# UCirKitBreadboardTop.net
KiCad netlist of a schematic drawn in EAGLE
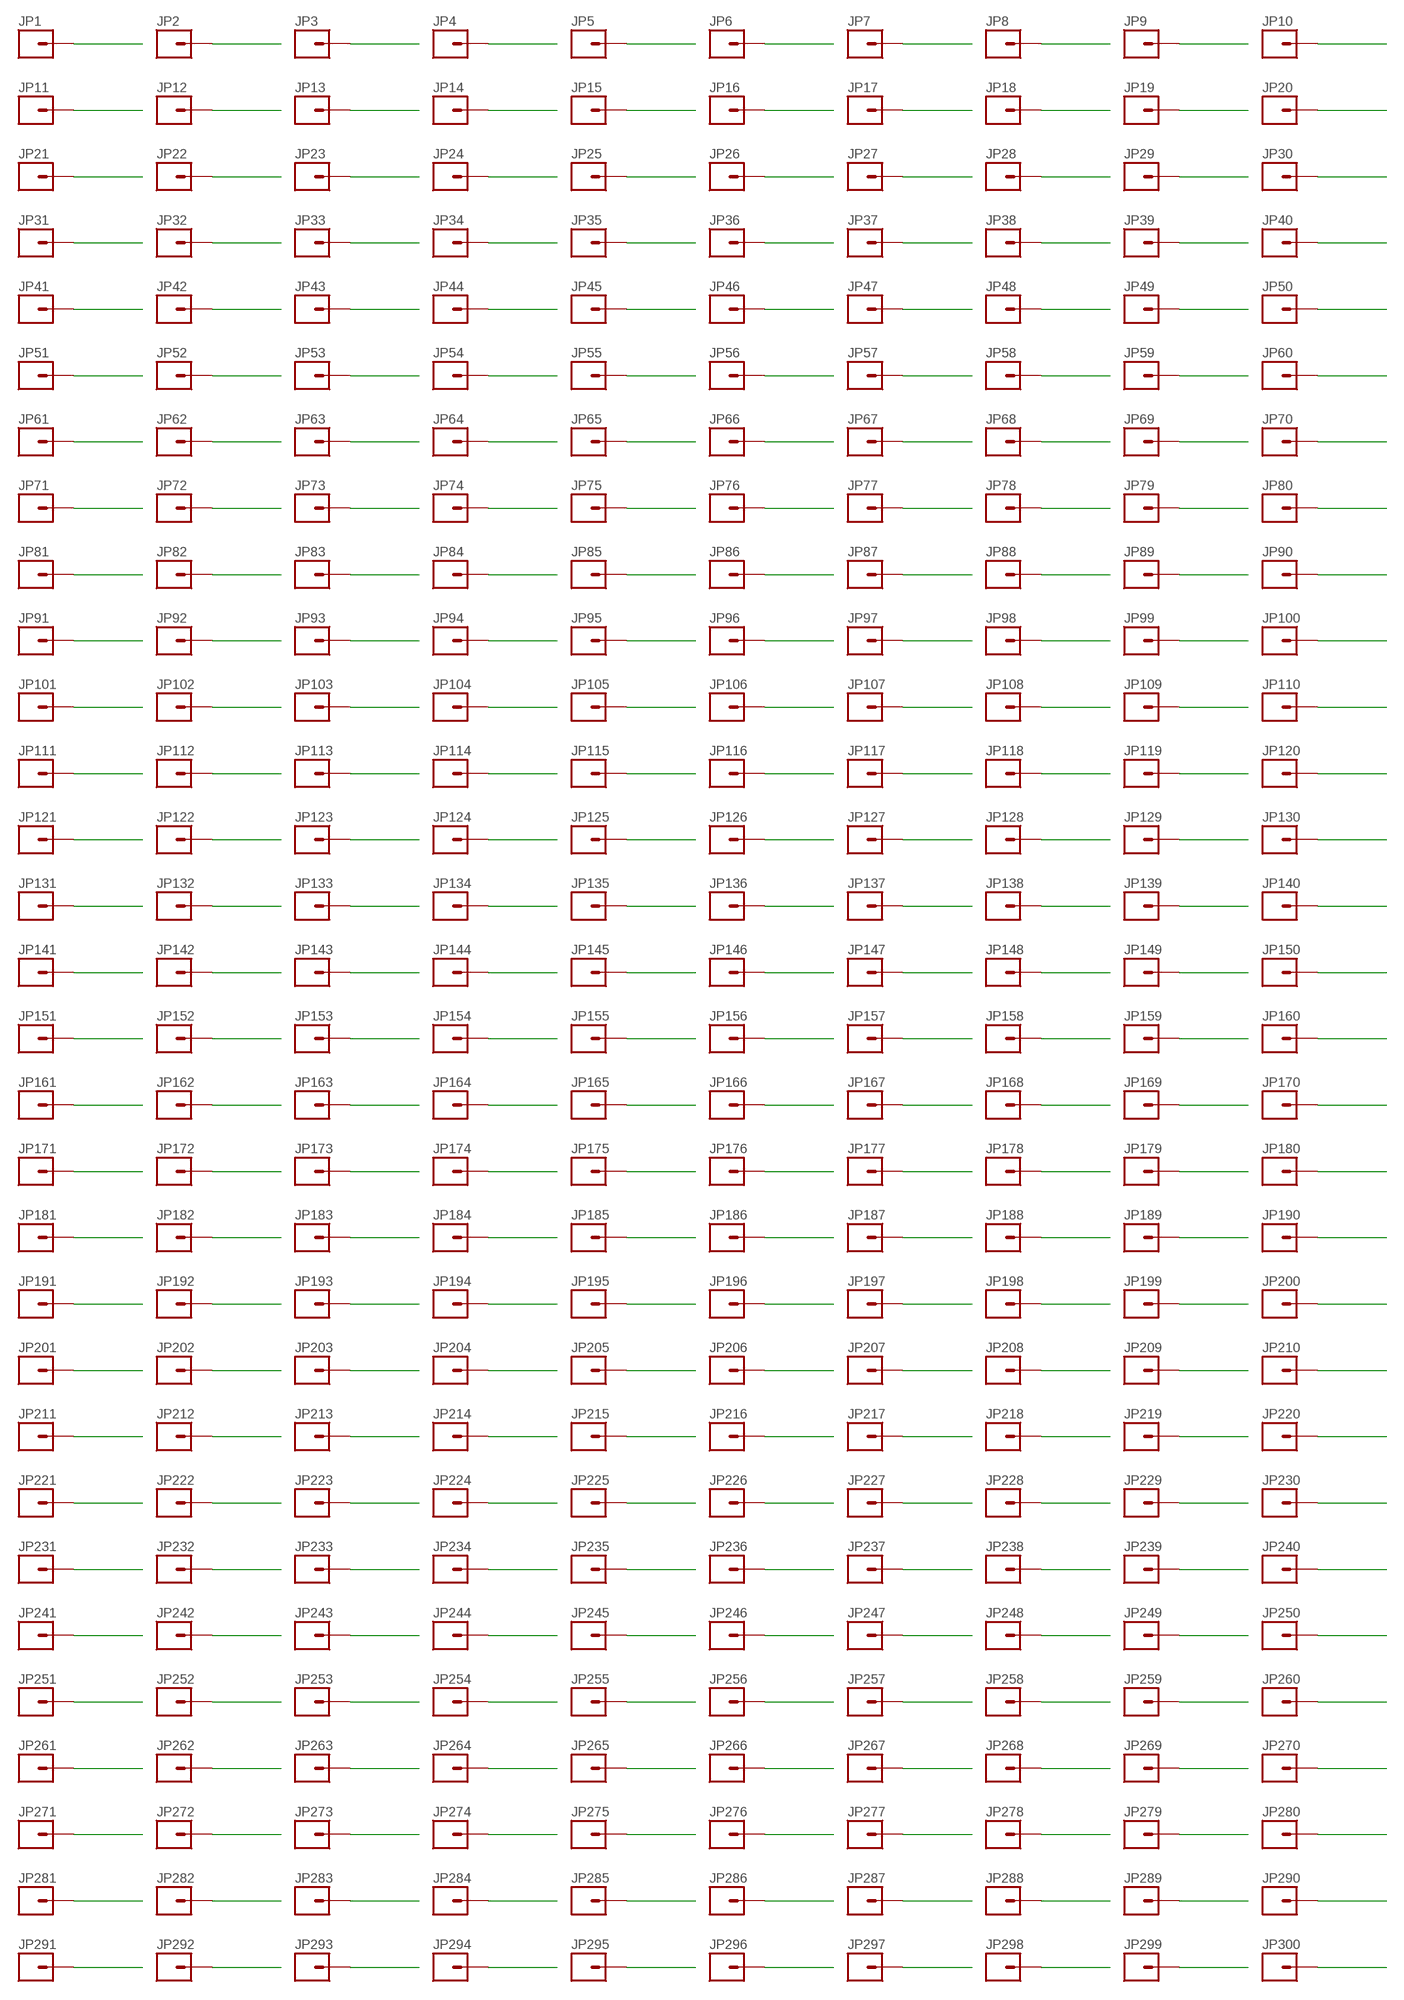
[diagram p0: schematic, sheet 1, part 1 of 2]
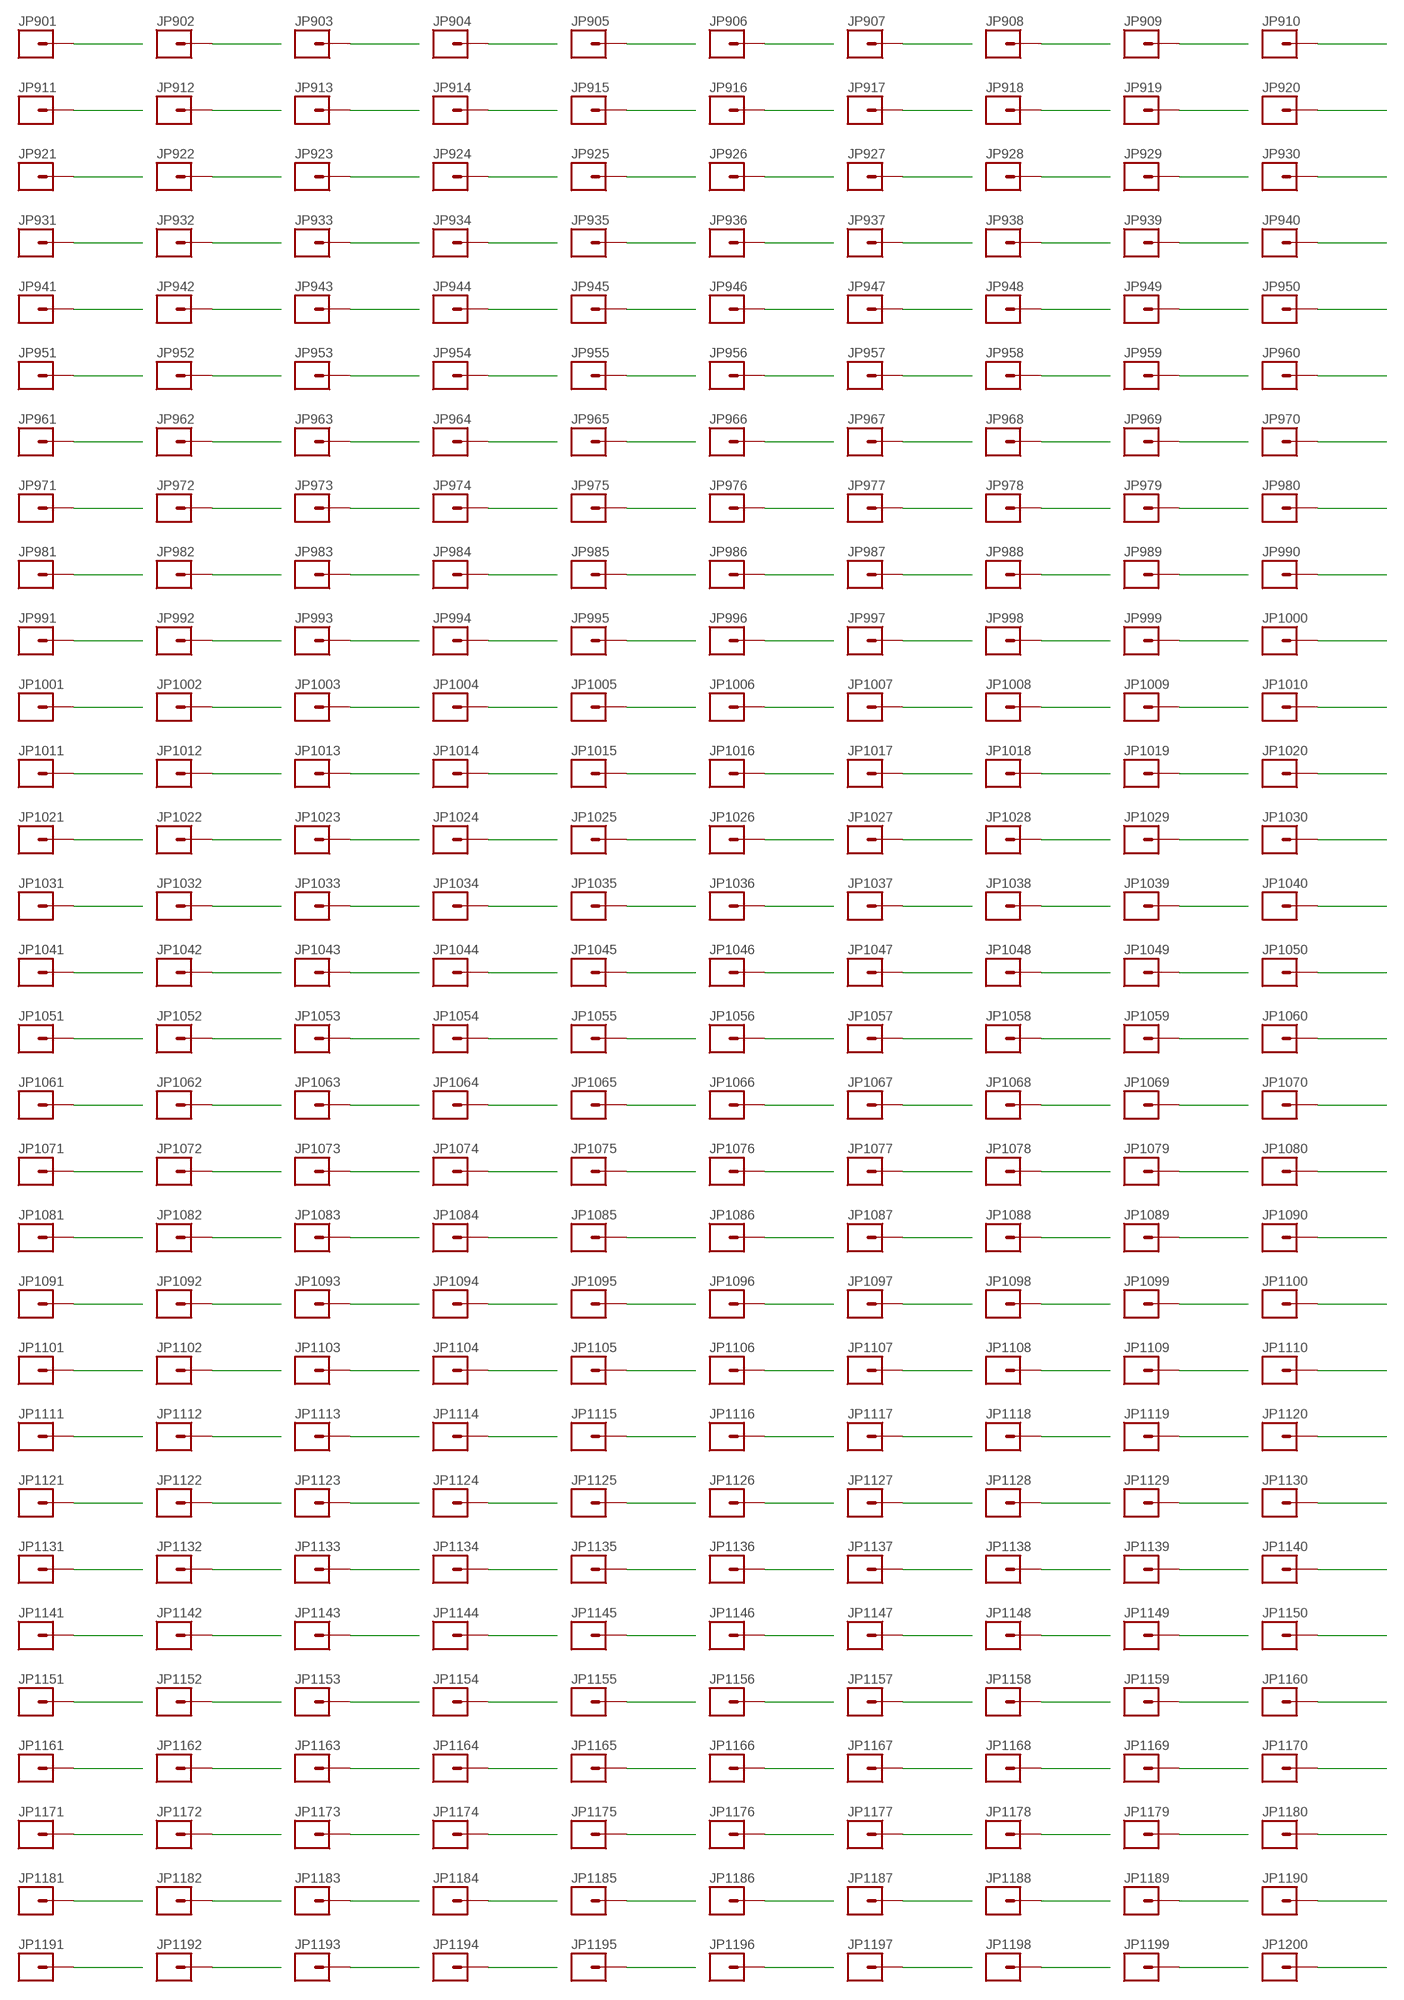
[diagram p1: schematic, sheet 1, part 2 of 2]

(export (version "E")
  (design (tool "Eeschema 10.0.6"))
  (components
    (comp (ref "JP1")
      (value "M01PTH_WITHOUT_TEXT")
      (footprint "eagle-import:1X01_WITHOUT_TEXT")
      (libsource (lib "eagle-import") (part "M01PTH_WITHOUT_TEXT"))
    )
    (comp (ref "JP2")
      (value "M01PTH_WITHOUT_TEXT")
      (footprint "eagle-import:1X01_WITHOUT_TEXT")
      (libsource (lib "eagle-import") (part "M01PTH_WITHOUT_TEXT"))
    )
    (comp (ref "JP3")
      (value "M01PTH_WITHOUT_TEXT")
      (footprint "eagle-import:1X01_WITHOUT_TEXT")
      (libsource (lib "eagle-import") (part "M01PTH_WITHOUT_TEXT"))
    )
    (comp (ref "JP4")
      (value "M01PTH_WITHOUT_TEXT")
      (footprint "eagle-import:1X01_WITHOUT_TEXT")
      (libsource (lib "eagle-import") (part "M01PTH_WITHOUT_TEXT"))
    )
    (comp (ref "JP5")
      (value "M01PTH_WITHOUT_TEXT")
      (footprint "eagle-import:1X01_WITHOUT_TEXT")
      (libsource (lib "eagle-import") (part "M01PTH_WITHOUT_TEXT"))
    )
    (comp (ref "JP6")
      (value "M01PTH_WITHOUT_TEXT")
      (footprint "eagle-import:1X01_WITHOUT_TEXT")
      (libsource (lib "eagle-import") (part "M01PTH_WITHOUT_TEXT"))
    )
    (comp (ref "JP7")
      (value "M01PTH_WITHOUT_TEXT")
      (footprint "eagle-import:1X01_WITHOUT_TEXT")
      (libsource (lib "eagle-import") (part "M01PTH_WITHOUT_TEXT"))
    )
    (comp (ref "JP8")
      (value "M01PTH_WITHOUT_TEXT")
      (footprint "eagle-import:1X01_WITHOUT_TEXT")
      (libsource (lib "eagle-import") (part "M01PTH_WITHOUT_TEXT"))
    )
    (comp (ref "JP9")
      (value "M01PTH_WITHOUT_TEXT")
      (footprint "eagle-import:1X01_WITHOUT_TEXT")
      (libsource (lib "eagle-import") (part "M01PTH_WITHOUT_TEXT"))
    )
    (comp (ref "JP10")
      (value "M01PTH_WITHOUT_TEXT")
      (footprint "eagle-import:1X01_WITHOUT_TEXT")
      (libsource (lib "eagle-import") (part "M01PTH_WITHOUT_TEXT"))
    )
    (comp (ref "JP11")
      (value "M01PTH_WITHOUT_TEXT")
      (footprint "eagle-import:1X01_WITHOUT_TEXT")
      (libsource (lib "eagle-import") (part "M01PTH_WITHOUT_TEXT"))
    )
    (comp (ref "JP12")
      (value "M01PTH_WITHOUT_TEXT")
      (footprint "eagle-import:1X01_WITHOUT_TEXT")
      (libsource (lib "eagle-import") (part "M01PTH_WITHOUT_TEXT"))
    )
    (comp (ref "JP13")
      (value "M01PTH_WITHOUT_TEXT")
      (footprint "eagle-import:1X01_WITHOUT_TEXT")
      (libsource (lib "eagle-import") (part "M01PTH_WITHOUT_TEXT"))
    )
    (comp (ref "JP14")
      (value "M01PTH_WITHOUT_TEXT")
      (footprint "eagle-import:1X01_WITHOUT_TEXT")
      (libsource (lib "eagle-import") (part "M01PTH_WITHOUT_TEXT"))
    )
    (comp (ref "JP15")
      (value "M01PTH_WITHOUT_TEXT")
      (footprint "eagle-import:1X01_WITHOUT_TEXT")
      (libsource (lib "eagle-import") (part "M01PTH_WITHOUT_TEXT"))
    )
    (comp (ref "JP16")
      (value "M01PTH_WITHOUT_TEXT")
      (footprint "eagle-import:1X01_WITHOUT_TEXT")
      (libsource (lib "eagle-import") (part "M01PTH_WITHOUT_TEXT"))
    )
    (comp (ref "JP17")
      (value "M01PTH_WITHOUT_TEXT")
      (footprint "eagle-import:1X01_WITHOUT_TEXT")
      (libsource (lib "eagle-import") (part "M01PTH_WITHOUT_TEXT"))
    )
    (comp (ref "JP18")
      (value "M01PTH_WITHOUT_TEXT")
      (footprint "eagle-import:1X01_WITHOUT_TEXT")
      (libsource (lib "eagle-import") (part "M01PTH_WITHOUT_TEXT"))
    )
    (comp (ref "JP19")
      (value "M01PTH_WITHOUT_TEXT")
      (footprint "eagle-import:1X01_WITHOUT_TEXT")
      (libsource (lib "eagle-import") (part "M01PTH_WITHOUT_TEXT"))
    )
    (comp (ref "JP20")
      (value "M01PTH_WITHOUT_TEXT")
      (footprint "eagle-import:1X01_WITHOUT_TEXT")
      (libsource (lib "eagle-import") (part "M01PTH_WITHOUT_TEXT"))
    )
    (comp (ref "JP21")
      (value "M01PTH_WITHOUT_TEXT")
      (footprint "eagle-import:1X01_WITHOUT_TEXT")
      (libsource (lib "eagle-import") (part "M01PTH_WITHOUT_TEXT"))
    )
    (comp (ref "JP22")
      (value "M01PTH_WITHOUT_TEXT")
      (footprint "eagle-import:1X01_WITHOUT_TEXT")
      (libsource (lib "eagle-import") (part "M01PTH_WITHOUT_TEXT"))
    )
    (comp (ref "JP23")
      (value "M01PTH_WITHOUT_TEXT")
      (footprint "eagle-import:1X01_WITHOUT_TEXT")
      (libsource (lib "eagle-import") (part "M01PTH_WITHOUT_TEXT"))
    )
    (comp (ref "JP24")
      (value "M01PTH_WITHOUT_TEXT")
      (footprint "eagle-import:1X01_WITHOUT_TEXT")
      (libsource (lib "eagle-import") (part "M01PTH_WITHOUT_TEXT"))
    )
    (comp (ref "JP25")
      (value "M01PTH_WITHOUT_TEXT")
      (footprint "eagle-import:1X01_WITHOUT_TEXT")
      (libsource (lib "eagle-import") (part "M01PTH_WITHOUT_TEXT"))
    )
    (comp (ref "JP26")
      (value "M01PTH_WITHOUT_TEXT")
      (footprint "eagle-import:1X01_WITHOUT_TEXT")
      (libsource (lib "eagle-import") (part "M01PTH_WITHOUT_TEXT"))
    )
    (comp (ref "JP27")
      (value "M01PTH_WITHOUT_TEXT")
      (footprint "eagle-import:1X01_WITHOUT_TEXT")
      (libsource (lib "eagle-import") (part "M01PTH_WITHOUT_TEXT"))
    )
    (comp (ref "JP28")
      (value "M01PTH_WITHOUT_TEXT")
      (footprint "eagle-import:1X01_WITHOUT_TEXT")
      (libsource (lib "eagle-import") (part "M01PTH_WITHOUT_TEXT"))
    )
    (comp (ref "JP29")
      (value "M01PTH_WITHOUT_TEXT")
      (footprint "eagle-import:1X01_WITHOUT_TEXT")
      (libsource (lib "eagle-import") (part "M01PTH_WITHOUT_TEXT"))
    )
    (comp (ref "JP30")
      (value "M01PTH_WITHOUT_TEXT")
      (footprint "eagle-import:1X01_WITHOUT_TEXT")
      (libsource (lib "eagle-import") (part "M01PTH_WITHOUT_TEXT"))
    )
    (comp (ref "JP31")
      (value "M01PTH_WITHOUT_TEXT")
      (footprint "eagle-import:1X01_WITHOUT_TEXT")
      (libsource (lib "eagle-import") (part "M01PTH_WITHOUT_TEXT"))
    )
    (comp (ref "JP32")
      (value "M01PTH_WITHOUT_TEXT")
      (footprint "eagle-import:1X01_WITHOUT_TEXT")
      (libsource (lib "eagle-import") (part "M01PTH_WITHOUT_TEXT"))
    )
    (comp (ref "JP33")
      (value "M01PTH_WITHOUT_TEXT")
      (footprint "eagle-import:1X01_WITHOUT_TEXT")
      (libsource (lib "eagle-import") (part "M01PTH_WITHOUT_TEXT"))
    )
    (comp (ref "JP34")
      (value "M01PTH_WITHOUT_TEXT")
      (footprint "eagle-import:1X01_WITHOUT_TEXT")
      (libsource (lib "eagle-import") (part "M01PTH_WITHOUT_TEXT"))
    )
    (comp (ref "JP35")
      (value "M01PTH_WITHOUT_TEXT")
      (footprint "eagle-import:1X01_WITHOUT_TEXT")
      (libsource (lib "eagle-import") (part "M01PTH_WITHOUT_TEXT"))
    )
    (comp (ref "JP36")
      (value "M01PTH_WITHOUT_TEXT")
      (footprint "eagle-import:1X01_WITHOUT_TEXT")
      (libsource (lib "eagle-import") (part "M01PTH_WITHOUT_TEXT"))
    )
    (comp (ref "JP37")
      (value "M01PTH_WITHOUT_TEXT")
      (footprint "eagle-import:1X01_WITHOUT_TEXT")
      (libsource (lib "eagle-import") (part "M01PTH_WITHOUT_TEXT"))
    )
    (comp (ref "JP38")
      (value "M01PTH_WITHOUT_TEXT")
      (footprint "eagle-import:1X01_WITHOUT_TEXT")
      (libsource (lib "eagle-import") (part "M01PTH_WITHOUT_TEXT"))
    )
    (comp (ref "JP39")
      (value "M01PTH_WITHOUT_TEXT")
      (footprint "eagle-import:1X01_WITHOUT_TEXT")
      (libsource (lib "eagle-import") (part "M01PTH_WITHOUT_TEXT"))
    )
    (comp (ref "JP40")
      (value "M01PTH_WITHOUT_TEXT")
      (footprint "eagle-import:1X01_WITHOUT_TEXT")
      (libsource (lib "eagle-import") (part "M01PTH_WITHOUT_TEXT"))
    )
    (comp (ref "JP41")
      (value "M01PTH_WITHOUT_TEXT")
      (footprint "eagle-import:1X01_WITHOUT_TEXT")
      (libsource (lib "eagle-import") (part "M01PTH_WITHOUT_TEXT"))
    )
    (comp (ref "JP42")
      (value "M01PTH_WITHOUT_TEXT")
      (footprint "eagle-import:1X01_WITHOUT_TEXT")
      (libsource (lib "eagle-import") (part "M01PTH_WITHOUT_TEXT"))
    )
    (comp (ref "JP43")
      (value "M01PTH_WITHOUT_TEXT")
      (footprint "eagle-import:1X01_WITHOUT_TEXT")
      (libsource (lib "eagle-import") (part "M01PTH_WITHOUT_TEXT"))
    )
    (comp (ref "JP44")
      (value "M01PTH_WITHOUT_TEXT")
      (footprint "eagle-import:1X01_WITHOUT_TEXT")
      (libsource (lib "eagle-import") (part "M01PTH_WITHOUT_TEXT"))
    )
    (comp (ref "JP45")
      (value "M01PTH_WITHOUT_TEXT")
      (footprint "eagle-import:1X01_WITHOUT_TEXT")
      (libsource (lib "eagle-import") (part "M01PTH_WITHOUT_TEXT"))
    )
    (comp (ref "JP46")
      (value "M01PTH_WITHOUT_TEXT")
      (footprint "eagle-import:1X01_WITHOUT_TEXT")
      (libsource (lib "eagle-import") (part "M01PTH_WITHOUT_TEXT"))
    )
    (comp (ref "JP47")
      (value "M01PTH_WITHOUT_TEXT")
      (footprint "eagle-import:1X01_WITHOUT_TEXT")
      (libsource (lib "eagle-import") (part "M01PTH_WITHOUT_TEXT"))
    )
    (comp (ref "JP48")
      (value "M01PTH_WITHOUT_TEXT")
      (footprint "eagle-import:1X01_WITHOUT_TEXT")
      (libsource (lib "eagle-import") (part "M01PTH_WITHOUT_TEXT"))
    )
    (comp (ref "JP49")
      (value "M01PTH_WITHOUT_TEXT")
      (footprint "eagle-import:1X01_WITHOUT_TEXT")
      (libsource (lib "eagle-import") (part "M01PTH_WITHOUT_TEXT"))
    )
    (comp (ref "JP50")
      (value "M01PTH_WITHOUT_TEXT")
      (footprint "eagle-import:1X01_WITHOUT_TEXT")
      (libsource (lib "eagle-import") (part "M01PTH_WITHOUT_TEXT"))
    )
    (comp (ref "JP51")
      (value "M01PTH_WITHOUT_TEXT")
      (footprint "eagle-import:1X01_WITHOUT_TEXT")
      (libsource (lib "eagle-import") (part "M01PTH_WITHOUT_TEXT"))
    )
    (comp (ref "JP52")
      (value "M01PTH_WITHOUT_TEXT")
      (footprint "eagle-import:1X01_WITHOUT_TEXT")
      (libsource (lib "eagle-import") (part "M01PTH_WITHOUT_TEXT"))
    )
    (comp (ref "JP53")
      (value "M01PTH_WITHOUT_TEXT")
      (footprint "eagle-import:1X01_WITHOUT_TEXT")
      (libsource (lib "eagle-import") (part "M01PTH_WITHOUT_TEXT"))
    )
    (comp (ref "JP54")
      (value "M01PTH_WITHOUT_TEXT")
      (footprint "eagle-import:1X01_WITHOUT_TEXT")
      (libsource (lib "eagle-import") (part "M01PTH_WITHOUT_TEXT"))
    )
    (comp (ref "JP55")
      (value "M01PTH_WITHOUT_TEXT")
      (footprint "eagle-import:1X01_WITHOUT_TEXT")
      (libsource (lib "eagle-import") (part "M01PTH_WITHOUT_TEXT"))
    )
    (comp (ref "JP56")
      (value "M01PTH_WITHOUT_TEXT")
      (footprint "eagle-import:1X01_WITHOUT_TEXT")
      (libsource (lib "eagle-import") (part "M01PTH_WITHOUT_TEXT"))
    )
    (comp (ref "JP57")
      (value "M01PTH_WITHOUT_TEXT")
      (footprint "eagle-import:1X01_WITHOUT_TEXT")
      (libsource (lib "eagle-import") (part "M01PTH_WITHOUT_TEXT"))
    )
    (comp (ref "JP58")
      (value "M01PTH_WITHOUT_TEXT")
      (footprint "eagle-import:1X01_WITHOUT_TEXT")
      (libsource (lib "eagle-import") (part "M01PTH_WITHOUT_TEXT"))
    )
    (comp (ref "JP59")
      (value "M01PTH_WITHOUT_TEXT")
      (footprint "eagle-import:1X01_WITHOUT_TEXT")
      (libsource (lib "eagle-import") (part "M01PTH_WITHOUT_TEXT"))
    )
    (comp (ref "JP60")
      (value "M01PTH_WITHOUT_TEXT")
      (footprint "eagle-import:1X01_WITHOUT_TEXT")
      (libsource (lib "eagle-import") (part "M01PTH_WITHOUT_TEXT"))
    )
    (comp (ref "JP61")
      (value "M01PTH_WITHOUT_TEXT")
      (footprint "eagle-import:1X01_WITHOUT_TEXT")
      (libsource (lib "eagle-import") (part "M01PTH_WITHOUT_TEXT"))
    )
    (comp (ref "JP62")
      (value "M01PTH_WITHOUT_TEXT")
      (footprint "eagle-import:1X01_WITHOUT_TEXT")
      (libsource (lib "eagle-import") (part "M01PTH_WITHOUT_TEXT"))
    )
    (comp (ref "JP63")
      (value "M01PTH_WITHOUT_TEXT")
      (footprint "eagle-import:1X01_WITHOUT_TEXT")
      (libsource (lib "eagle-import") (part "M01PTH_WITHOUT_TEXT"))
    )
    (comp (ref "JP64")
      (value "M01PTH_WITHOUT_TEXT")
      (footprint "eagle-import:1X01_WITHOUT_TEXT")
      (libsource (lib "eagle-import") (part "M01PTH_WITHOUT_TEXT"))
    )
    (comp (ref "JP65")
      (value "M01PTH_WITHOUT_TEXT")
      (footprint "eagle-import:1X01_WITHOUT_TEXT")
      (libsource (lib "eagle-import") (part "M01PTH_WITHOUT_TEXT"))
    )
    (comp (ref "JP66")
      (value "M01PTH_WITHOUT_TEXT")
      (footprint "eagle-import:1X01_WITHOUT_TEXT")
      (libsource (lib "eagle-import") (part "M01PTH_WITHOUT_TEXT"))
    )
    (comp (ref "JP67")
      (value "M01PTH_WITHOUT_TEXT")
      (footprint "eagle-import:1X01_WITHOUT_TEXT")
      (libsource (lib "eagle-import") (part "M01PTH_WITHOUT_TEXT"))
    )
    (comp (ref "JP68")
      (value "M01PTH_WITHOUT_TEXT")
      (footprint "eagle-import:1X01_WITHOUT_TEXT")
      (libsource (lib "eagle-import") (part "M01PTH_WITHOUT_TEXT"))
    )
    (comp (ref "JP69")
      (value "M01PTH_WITHOUT_TEXT")
      (footprint "eagle-import:1X01_WITHOUT_TEXT")
      (libsource (lib "eagle-import") (part "M01PTH_WITHOUT_TEXT"))
    )
    (comp (ref "JP70")
      (value "M01PTH_WITHOUT_TEXT")
      (footprint "eagle-import:1X01_WITHOUT_TEXT")
      (libsource (lib "eagle-import") (part "M01PTH_WITHOUT_TEXT"))
    )
    (comp (ref "JP71")
      (value "M01PTH_WITHOUT_TEXT")
      (footprint "eagle-import:1X01_WITHOUT_TEXT")
      (libsource (lib "eagle-import") (part "M01PTH_WITHOUT_TEXT"))
    )
    (comp (ref "JP72")
      (value "M01PTH_WITHOUT_TEXT")
      (footprint "eagle-import:1X01_WITHOUT_TEXT")
      (libsource (lib "eagle-import") (part "M01PTH_WITHOUT_TEXT"))
    )
    (comp (ref "JP73")
      (value "M01PTH_WITHOUT_TEXT")
      (footprint "eagle-import:1X01_WITHOUT_TEXT")
      (libsource (lib "eagle-import") (part "M01PTH_WITHOUT_TEXT"))
    )
    (comp (ref "JP74")
      (value "M01PTH_WITHOUT_TEXT")
      (footprint "eagle-import:1X01_WITHOUT_TEXT")
      (libsource (lib "eagle-import") (part "M01PTH_WITHOUT_TEXT"))
    )
    (comp (ref "JP75")
      (value "M01PTH_WITHOUT_TEXT")
      (footprint "eagle-import:1X01_WITHOUT_TEXT")
      (libsource (lib "eagle-import") (part "M01PTH_WITHOUT_TEXT"))
    )
    (comp (ref "JP76")
      (value "M01PTH_WITHOUT_TEXT")
      (footprint "eagle-import:1X01_WITHOUT_TEXT")
      (libsource (lib "eagle-import") (part "M01PTH_WITHOUT_TEXT"))
    )
    (comp (ref "JP77")
      (value "M01PTH_WITHOUT_TEXT")
      (footprint "eagle-import:1X01_WITHOUT_TEXT")
      (libsource (lib "eagle-import") (part "M01PTH_WITHOUT_TEXT"))
    )
    (comp (ref "JP78")
      (value "M01PTH_WITHOUT_TEXT")
      (footprint "eagle-import:1X01_WITHOUT_TEXT")
      (libsource (lib "eagle-import") (part "M01PTH_WITHOUT_TEXT"))
    )
    (comp (ref "JP79")
      (value "M01PTH_WITHOUT_TEXT")
      (footprint "eagle-import:1X01_WITHOUT_TEXT")
      (libsource (lib "eagle-import") (part "M01PTH_WITHOUT_TEXT"))
    )
    (comp (ref "JP80")
      (value "M01PTH_WITHOUT_TEXT")
      (footprint "eagle-import:1X01_WITHOUT_TEXT")
      (libsource (lib "eagle-import") (part "M01PTH_WITHOUT_TEXT"))
    )
    (comp (ref "JP81")
      (value "M01PTH_WITHOUT_TEXT")
      (footprint "eagle-import:1X01_WITHOUT_TEXT")
      (libsource (lib "eagle-import") (part "M01PTH_WITHOUT_TEXT"))
    )
    (comp (ref "JP82")
      (value "M01PTH_WITHOUT_TEXT")
      (footprint "eagle-import:1X01_WITHOUT_TEXT")
      (libsource (lib "eagle-import") (part "M01PTH_WITHOUT_TEXT"))
    )
    (comp (ref "JP83")
      (value "M01PTH_WITHOUT_TEXT")
      (footprint "eagle-import:1X01_WITHOUT_TEXT")
      (libsource (lib "eagle-import") (part "M01PTH_WITHOUT_TEXT"))
    )
    (comp (ref "JP84")
      (value "M01PTH_WITHOUT_TEXT")
      (footprint "eagle-import:1X01_WITHOUT_TEXT")
      (libsource (lib "eagle-import") (part "M01PTH_WITHOUT_TEXT"))
    )
    (comp (ref "JP85")
      (value "M01PTH_WITHOUT_TEXT")
      (footprint "eagle-import:1X01_WITHOUT_TEXT")
      (libsource (lib "eagle-import") (part "M01PTH_WITHOUT_TEXT"))
    )
    (comp (ref "JP86")
      (value "M01PTH_WITHOUT_TEXT")
      (footprint "eagle-import:1X01_WITHOUT_TEXT")
      (libsource (lib "eagle-import") (part "M01PTH_WITHOUT_TEXT"))
    )
    (comp (ref "JP87")
      (value "M01PTH_WITHOUT_TEXT")
      (footprint "eagle-import:1X01_WITHOUT_TEXT")
      (libsource (lib "eagle-import") (part "M01PTH_WITHOUT_TEXT"))
    )
    (comp (ref "JP88")
      (value "M01PTH_WITHOUT_TEXT")
      (footprint "eagle-import:1X01_WITHOUT_TEXT")
      (libsource (lib "eagle-import") (part "M01PTH_WITHOUT_TEXT"))
    )
    (comp (ref "JP89")
      (value "M01PTH_WITHOUT_TEXT")
      (footprint "eagle-import:1X01_WITHOUT_TEXT")
      (libsource (lib "eagle-import") (part "M01PTH_WITHOUT_TEXT"))
    )
    (comp (ref "JP90")
      (value "M01PTH_WITHOUT_TEXT")
      (footprint "eagle-import:1X01_WITHOUT_TEXT")
      (libsource (lib "eagle-import") (part "M01PTH_WITHOUT_TEXT"))
    )
    (comp (ref "JP91")
      (value "M01PTH_WITHOUT_TEXT")
      (footprint "eagle-import:1X01_WITHOUT_TEXT")
      (libsource (lib "eagle-import") (part "M01PTH_WITHOUT_TEXT"))
    )
    (comp (ref "JP92")
      (value "M01PTH_WITHOUT_TEXT")
      (footprint "eagle-import:1X01_WITHOUT_TEXT")
      (libsource (lib "eagle-import") (part "M01PTH_WITHOUT_TEXT"))
    )
    (comp (ref "JP93")
      (value "M01PTH_WITHOUT_TEXT")
      (footprint "eagle-import:1X01_WITHOUT_TEXT")
      (libsource (lib "eagle-import") (part "M01PTH_WITHOUT_TEXT"))
    )
    (comp (ref "JP94")
      (value "M01PTH_WITHOUT_TEXT")
      (footprint "eagle-import:1X01_WITHOUT_TEXT")
      (libsource (lib "eagle-import") (part "M01PTH_WITHOUT_TEXT"))
    )
    (comp (ref "JP95")
      (value "M01PTH_WITHOUT_TEXT")
      (footprint "eagle-import:1X01_WITHOUT_TEXT")
      (libsource (lib "eagle-import") (part "M01PTH_WITHOUT_TEXT"))
    )
    (comp (ref "JP96")
      (value "M01PTH_WITHOUT_TEXT")
      (footprint "eagle-import:1X01_WITHOUT_TEXT")
      (libsource (lib "eagle-import") (part "M01PTH_WITHOUT_TEXT"))
    )
    (comp (ref "JP97")
      (value "M01PTH_WITHOUT_TEXT")
      (footprint "eagle-import:1X01_WITHOUT_TEXT")
      (libsource (lib "eagle-import") (part "M01PTH_WITHOUT_TEXT"))
    )
    (comp (ref "JP98")
      (value "M01PTH_WITHOUT_TEXT")
      (footprint "eagle-import:1X01_WITHOUT_TEXT")
      (libsource (lib "eagle-import") (part "M01PTH_WITHOUT_TEXT"))
    )
    (comp (ref "JP99")
      (value "M01PTH_WITHOUT_TEXT")
      (footprint "eagle-import:1X01_WITHOUT_TEXT")
      (libsource (lib "eagle-import") (part "M01PTH_WITHOUT_TEXT"))
    )
    (comp (ref "JP100")
      (value "M01PTH_WITHOUT_TEXT")
      (footprint "eagle-import:1X01_WITHOUT_TEXT")
      (libsource (lib "eagle-import") (part "M01PTH_WITHOUT_TEXT"))
    )
    (comp (ref "JP101")
      (value "M01PTH_WITHOUT_TEXT")
      (footprint "eagle-import:1X01_WITHOUT_TEXT")
      (libsource (lib "eagle-import") (part "M01PTH_WITHOUT_TEXT"))
    )
    (comp (ref "JP102")
      (value "M01PTH_WITHOUT_TEXT")
      (footprint "eagle-import:1X01_WITHOUT_TEXT")
      (libsource (lib "eagle-import") (part "M01PTH_WITHOUT_TEXT"))
    )
    (comp (ref "JP103")
      (value "M01PTH_WITHOUT_TEXT")
      (footprint "eagle-import:1X01_WITHOUT_TEXT")
      (libsource (lib "eagle-import") (part "M01PTH_WITHOUT_TEXT"))
    )
    (comp (ref "JP104")
      (value "M01PTH_WITHOUT_TEXT")
      (footprint "eagle-import:1X01_WITHOUT_TEXT")
      (libsource (lib "eagle-import") (part "M01PTH_WITHOUT_TEXT"))
    )
    (comp (ref "JP105")
      (value "M01PTH_WITHOUT_TEXT")
      (footprint "eagle-import:1X01_WITHOUT_TEXT")
      (libsource (lib "eagle-import") (part "M01PTH_WITHOUT_TEXT"))
    )
    (comp (ref "JP106")
      (value "M01PTH_WITHOUT_TEXT")
      (footprint "eagle-import:1X01_WITHOUT_TEXT")
      (libsource (lib "eagle-import") (part "M01PTH_WITHOUT_TEXT"))
    )
    (comp (ref "JP107")
      (value "M01PTH_WITHOUT_TEXT")
      (footprint "eagle-import:1X01_WITHOUT_TEXT")
      (libsource (lib "eagle-import") (part "M01PTH_WITHOUT_TEXT"))
    )
    (comp (ref "JP108")
      (value "M01PTH_WITHOUT_TEXT")
      (footprint "eagle-import:1X01_WITHOUT_TEXT")
      (libsource (lib "eagle-import") (part "M01PTH_WITHOUT_TEXT"))
    )
    (comp (ref "JP109")
      (value "M01PTH_WITHOUT_TEXT")
      (footprint "eagle-import:1X01_WITHOUT_TEXT")
      (libsource (lib "eagle-import") (part "M01PTH_WITHOUT_TEXT"))
    )
    (comp (ref "JP110")
      (value "M01PTH_WITHOUT_TEXT")
      (footprint "eagle-import:1X01_WITHOUT_TEXT")
      (libsource (lib "eagle-import") (part "M01PTH_WITHOUT_TEXT"))
    )
    (comp (ref "JP111")
      (value "M01PTH_WITHOUT_TEXT")
      (footprint "eagle-import:1X01_WITHOUT_TEXT")
      (libsource (lib "eagle-import") (part "M01PTH_WITHOUT_TEXT"))
    )
    (comp (ref "JP112")
      (value "M01PTH_WITHOUT_TEXT")
      (footprint "eagle-import:1X01_WITHOUT_TEXT")
      (libsource (lib "eagle-import") (part "M01PTH_WITHOUT_TEXT"))
    )
    (comp (ref "JP113")
      (value "M01PTH_WITHOUT_TEXT")
      (footprint "eagle-import:1X01_WITHOUT_TEXT")
      (libsource (lib "eagle-import") (part "M01PTH_WITHOUT_TEXT"))
    )
    (comp (ref "JP114")
      (value "M01PTH_WITHOUT_TEXT")
      (footprint "eagle-import:1X01_WITHOUT_TEXT")
      (libsource (lib "eagle-import") (part "M01PTH_WITHOUT_TEXT"))
    )
    (comp (ref "JP115")
      (value "M01PTH_WITHOUT_TEXT")
      (footprint "eagle-import:1X01_WITHOUT_TEXT")
      (libsource (lib "eagle-import") (part "M01PTH_WITHOUT_TEXT"))
    )
    (comp (ref "JP116")
      (value "M01PTH_WITHOUT_TEXT")
      (footprint "eagle-import:1X01_WITHOUT_TEXT")
      (libsource (lib "eagle-import") (part "M01PTH_WITHOUT_TEXT"))
    )
    (comp (ref "JP117")
      (value "M01PTH_WITHOUT_TEXT")
      (footprint "eagle-import:1X01_WITHOUT_TEXT")
      (libsource (lib "eagle-import") (part "M01PTH_WITHOUT_TEXT"))
    )
    (comp (ref "JP118")
      (value "M01PTH_WITHOUT_TEXT")
      (footprint "eagle-import:1X01_WITHOUT_TEXT")
      (libsource (lib "eagle-import") (part "M01PTH_WITHOUT_TEXT"))
    )
    (comp (ref "JP119")
      (value "M01PTH_WITHOUT_TEXT")
      (footprint "eagle-import:1X01_WITHOUT_TEXT")
      (libsource (lib "eagle-import") (part "M01PTH_WITHOUT_TEXT"))
    )
    (comp (ref "JP120")
      (value "M01PTH_WITHOUT_TEXT")
      (footprint "eagle-import:1X01_WITHOUT_TEXT")
      (libsource (lib "eagle-import") (part "M01PTH_WITHOUT_TEXT"))
    )
    (comp (ref "JP121")
      (value "M01PTH_WITHOUT_TEXT")
      (footprint "eagle-import:1X01_WITHOUT_TEXT")
      (libsource (lib "eagle-import") (part "M01PTH_WITHOUT_TEXT"))
    )
    (comp (ref "JP122")
      (value "M01PTH_WITHOUT_TEXT")
      (footprint "eagle-import:1X01_WITHOUT_TEXT")
      (libsource (lib "eagle-import") (part "M01PTH_WITHOUT_TEXT"))
    )
    (comp (ref "JP123")
      (value "M01PTH_WITHOUT_TEXT")
      (footprint "eagle-import:1X01_WITHOUT_TEXT")
      (libsource (lib "eagle-import") (part "M01PTH_WITHOUT_TEXT"))
    )
    (comp (ref "JP124")
      (value "M01PTH_WITHOUT_TEXT")
      (footprint "eagle-import:1X01_WITHOUT_TEXT")
      (libsource (lib "eagle-import") (part "M01PTH_WITHOUT_TEXT"))
    )
    (comp (ref "JP125")
      (value "M01PTH_WITHOUT_TEXT")
      (footprint "eagle-import:1X01_WITHOUT_TEXT")
      (libsource (lib "eagle-import") (part "M01PTH_WITHOUT_TEXT"))
    )
    (comp (ref "JP126")
      (value "M01PTH_WITHOUT_TEXT")
      (footprint "eagle-import:1X01_WITHOUT_TEXT")
      (libsource (lib "eagle-import") (part "M01PTH_WITHOUT_TEXT"))
    )
    (comp (ref "JP127")
      (value "M01PTH_WITHOUT_TEXT")
      (footprint "eagle-import:1X01_WITHOUT_TEXT")
      (libsource (lib "eagle-import") (part "M01PTH_WITHOUT_TEXT"))
    )
    (comp (ref "JP128")
      (value "M01PTH_WITHOUT_TEXT")
      (footprint "eagle-import:1X01_WITHOUT_TEXT")
      (libsource (lib "eagle-import") (part "M01PTH_WITHOUT_TEXT"))
    )
    (comp (ref "JP129")
      (value "M01PTH_WITHOUT_TEXT")
      (footprint "eagle-import:1X01_WITHOUT_TEXT")
      (libsource (lib "eagle-import") (part "M01PTH_WITHOUT_TEXT"))
    )
    (comp (ref "JP130")
      (value "M01PTH_WITHOUT_TEXT")
      (footprint "eagle-import:1X01_WITHOUT_TEXT")
      (libsource (lib "eagle-import") (part "M01PTH_WITHOUT_TEXT"))
    )
    (comp (ref "JP131")
      (value "M01PTH_WITHOUT_TEXT")
      (footprint "eagle-import:1X01_WITHOUT_TEXT")
      (libsource (lib "eagle-import") (part "M01PTH_WITHOUT_TEXT"))
    )
    (comp (ref "JP132")
      (value "M01PTH_WITHOUT_TEXT")
      (footprint "eagle-import:1X01_WITHOUT_TEXT")
      (libsource (lib "eagle-import") (part "M01PTH_WITHOUT_TEXT"))
    )
    (comp (ref "JP133")
      (value "M01PTH_WITHOUT_TEXT")
      (footprint "eagle-import:1X01_WITHOUT_TEXT")
      (libsource (lib "eagle-import") (part "M01PTH_WITHOUT_TEXT"))
    )
    (comp (ref "JP134")
      (value "M01PTH_WITHOUT_TEXT")
      (footprint "eagle-import:1X01_WITHOUT_TEXT")
      (libsource (lib "eagle-import") (part "M01PTH_WITHOUT_TEXT"))
    )
    (comp (ref "JP135")
      (value "M01PTH_WITHOUT_TEXT")
      (footprint "eagle-import:1X01_WITHOUT_TEXT")
      (libsource (lib "eagle-import") (part "M01PTH_WITHOUT_TEXT"))
    )
    (comp (ref "JP136")
      (value "M01PTH_WITHOUT_TEXT")
      (footprint "eagle-import:1X01_WITHOUT_TEXT")
      (libsource (lib "eagle-import") (part "M01PTH_WITHOUT_TEXT"))
    )
    (comp (ref "JP137")
      (value "M01PTH_WITHOUT_TEXT")
      (footprint "eagle-import:1X01_WITHOUT_TEXT")
      (libsource (lib "eagle-import") (part "M01PTH_WITHOUT_TEXT"))
    )
    (comp (ref "JP138")
      (value "M01PTH_WITHOUT_TEXT")
      (footprint "eagle-import:1X01_WITHOUT_TEXT")
      (libsource (lib "eagle-import") (part "M01PTH_WITHOUT_TEXT"))
    )
    (comp (ref "JP139")
      (value "M01PTH_WITHOUT_TEXT")
      (footprint "eagle-import:1X01_WITHOUT_TEXT")
      (libsource (lib "eagle-import") (part "M01PTH_WITHOUT_TEXT"))
    )
    (comp (ref "JP140")
      (value "M01PTH_WITHOUT_TEXT")
      (footprint "eagle-import:1X01_WITHOUT_TEXT")
      (libsource (lib "eagle-import") (part "M01PTH_WITHOUT_TEXT"))
    )
    (comp (ref "JP141")
      (value "M01PTH_WITHOUT_TEXT")
      (footprint "eagle-import:1X01_WITHOUT_TEXT")
      (libsource (lib "eagle-import") (part "M01PTH_WITHOUT_TEXT"))
    )
    (comp (ref "JP142")
      (value "M01PTH_WITHOUT_TEXT")
      (footprint "eagle-import:1X01_WITHOUT_TEXT")
      (libsource (lib "eagle-import") (part "M01PTH_WITHOUT_TEXT"))
    )
    (comp (ref "JP143")
      (value "M01PTH_WITHOUT_TEXT")
      (footprint "eagle-import:1X01_WITHOUT_TEXT")
      (libsource (lib "eagle-import") (part "M01PTH_WITHOUT_TEXT"))
    )
    (comp (ref "JP144")
      (value "M01PTH_WITHOUT_TEXT")
      (footprint "eagle-import:1X01_WITHOUT_TEXT")
      (libsource (lib "eagle-import") (part "M01PTH_WITHOUT_TEXT"))
    )
    (comp (ref "JP145")
      (value "M01PTH_WITHOUT_TEXT")
      (footprint "eagle-import:1X01_WITHOUT_TEXT")
      (libsource (lib "eagle-import") (part "M01PTH_WITHOUT_TEXT"))
    )
    (comp (ref "JP146")
      (value "M01PTH_WITHOUT_TEXT")
      (footprint "eagle-import:1X01_WITHOUT_TEXT")
      (libsource (lib "eagle-import") (part "M01PTH_WITHOUT_TEXT"))
    )
    (comp (ref "JP147")
      (value "M01PTH_WITHOUT_TEXT")
      (footprint "eagle-import:1X01_WITHOUT_TEXT")
      (libsource (lib "eagle-import") (part "M01PTH_WITHOUT_TEXT"))
    )
    (comp (ref "JP148")
      (value "M01PTH_WITHOUT_TEXT")
      (footprint "eagle-import:1X01_WITHOUT_TEXT")
      (libsource (lib "eagle-import") (part "M01PTH_WITHOUT_TEXT"))
    )
    (comp (ref "JP149")
      (value "M01PTH_WITHOUT_TEXT")
      (footprint "eagle-import:1X01_WITHOUT_TEXT")
      (libsource (lib "eagle-import") (part "M01PTH_WITHOUT_TEXT"))
    )
    (comp (ref "JP150")
      (value "M01PTH_WITHOUT_TEXT")
      (footprint "eagle-import:1X01_WITHOUT_TEXT")
      (libsource (lib "eagle-import") (part "M01PTH_WITHOUT_TEXT"))
    )
    (comp (ref "JP151")
      (value "M01PTH_WITHOUT_TEXT")
      (footprint "eagle-import:1X01_WITHOUT_TEXT")
      (libsource (lib "eagle-import") (part "M01PTH_WITHOUT_TEXT"))
    )
    (comp (ref "JP152")
      (value "M01PTH_WITHOUT_TEXT")
      (footprint "eagle-import:1X01_WITHOUT_TEXT")
      (libsource (lib "eagle-import") (part "M01PTH_WITHOUT_TEXT"))
    )
    (comp (ref "JP153")
      (value "M01PTH_WITHOUT_TEXT")
      (footprint "eagle-import:1X01_WITHOUT_TEXT")
      (libsource (lib "eagle-import") (part "M01PTH_WITHOUT_TEXT"))
    )
    (comp (ref "JP154")
      (value "M01PTH_WITHOUT_TEXT")
      (footprint "eagle-import:1X01_WITHOUT_TEXT")
      (libsource (lib "eagle-import") (part "M01PTH_WITHOUT_TEXT"))
    )
    (comp (ref "JP155")
      (value "M01PTH_WITHOUT_TEXT")
      (footprint "eagle-import:1X01_WITHOUT_TEXT")
      (libsource (lib "eagle-import") (part "M01PTH_WITHOUT_TEXT"))
    )
    (comp (ref "JP156")
      (value "M01PTH_WITHOUT_TEXT")
      (footprint "eagle-import:1X01_WITHOUT_TEXT")
      (libsource (lib "eagle-import") (part "M01PTH_WITHOUT_TEXT"))
    )
    (comp (ref "JP157")
      (value "M01PTH_WITHOUT_TEXT")
      (footprint "eagle-import:1X01_WITHOUT_TEXT")
      (libsource (lib "eagle-import") (part "M01PTH_WITHOUT_TEXT"))
    )
    (comp (ref "JP158")
      (value "M01PTH_WITHOUT_TEXT")
      (footprint "eagle-import:1X01_WITHOUT_TEXT")
      (libsource (lib "eagle-import") (part "M01PTH_WITHOUT_TEXT"))
    )
    (comp (ref "JP159")
      (value "M01PTH_WITHOUT_TEXT")
      (footprint "eagle-import:1X01_WITHOUT_TEXT")
      (libsource (lib "eagle-import") (part "M01PTH_WITHOUT_TEXT"))
    )
    (comp (ref "JP160")
      (value "M01PTH_WITHOUT_TEXT")
      (footprint "eagle-import:1X01_WITHOUT_TEXT")
      (libsource (lib "eagle-import") (part "M01PTH_WITHOUT_TEXT"))
    )
    (comp (ref "JP161")
      (value "M01PTH_WITHOUT_TEXT")
      (footprint "eagle-import:1X01_WITHOUT_TEXT")
      (libsource (lib "eagle-import") (part "M01PTH_WITHOUT_TEXT"))
    )
    (comp (ref "JP162")
      (value "M01PTH_WITHOUT_TEXT")
      (footprint "eagle-import:1X01_WITHOUT_TEXT")
      (libsource (lib "eagle-import") (part "M01PTH_WITHOUT_TEXT"))
    )
    (comp (ref "JP163")
      (value "M01PTH_WITHOUT_TEXT")
      (footprint "eagle-import:1X01_WITHOUT_TEXT")
      (libsource (lib "eagle-import") (part "M01PTH_WITHOUT_TEXT"))
    )
    (comp (ref "JP164")
      (value "M01PTH_WITHOUT_TEXT")
      (footprint "eagle-import:1X01_WITHOUT_TEXT")
      (libsource (lib "eagle-import") (part "M01PTH_WITHOUT_TEXT"))
    )
    (comp (ref "JP165")
      (value "M01PTH_WITHOUT_TEXT")
      (footprint "eagle-import:1X01_WITHOUT_TEXT")
      (libsource (lib "eagle-import") (part "M01PTH_WITHOUT_TEXT"))
    )
    (comp (ref "JP166")
      (value "M01PTH_WITHOUT_TEXT")
      (footprint "eagle-import:1X01_WITHOUT_TEXT")
      (libsource (lib "eagle-import") (part "M01PTH_WITHOUT_TEXT"))
    )
    (comp (ref "JP167")
      (value "M01PTH_WITHOUT_TEXT")
      (footprint "eagle-import:1X01_WITHOUT_TEXT")
      (libsource (lib "eagle-import") (part "M01PTH_WITHOUT_TEXT"))
    )
    (comp (ref "JP168")
      (value "M01PTH_WITHOUT_TEXT")
      (footprint "eagle-import:1X01_WITHOUT_TEXT")
      (libsource (lib "eagle-import") (part "M01PTH_WITHOUT_TEXT"))
    )
    (comp (ref "JP169")
      (value "M01PTH_WITHOUT_TEXT")
      (footprint "eagle-import:1X01_WITHOUT_TEXT")
      (libsource (lib "eagle-import") (part "M01PTH_WITHOUT_TEXT"))
    )
    (comp (ref "JP170")
      (value "M01PTH_WITHOUT_TEXT")
      (footprint "eagle-import:1X01_WITHOUT_TEXT")
      (libsource (lib "eagle-import") (part "M01PTH_WITHOUT_TEXT"))
    )
    (comp (ref "JP171")
      (value "M01PTH_WITHOUT_TEXT")
      (footprint "eagle-import:1X01_WITHOUT_TEXT")
      (libsource (lib "eagle-import") (part "M01PTH_WITHOUT_TEXT"))
    )
    (comp (ref "JP172")
      (value "M01PTH_WITHOUT_TEXT")
      (footprint "eagle-import:1X01_WITHOUT_TEXT")
      (libsource (lib "eagle-import") (part "M01PTH_WITHOUT_TEXT"))
    )
    (comp (ref "JP173")
      (value "M01PTH_WITHOUT_TEXT")
      (footprint "eagle-import:1X01_WITHOUT_TEXT")
      (libsource (lib "eagle-import") (part "M01PTH_WITHOUT_TEXT"))
    )
    (comp (ref "JP174")
      (value "M01PTH_WITHOUT_TEXT")
      (footprint "eagle-import:1X01_WITHOUT_TEXT")
      (libsource (lib "eagle-import") (part "M01PTH_WITHOUT_TEXT"))
    )
    (comp (ref "JP175")
      (value "M01PTH_WITHOUT_TEXT")
      (footprint "eagle-import:1X01_WITHOUT_TEXT")
      (libsource (lib "eagle-import") (part "M01PTH_WITHOUT_TEXT"))
    )
    (comp (ref "JP176")
      (value "M01PTH_WITHOUT_TEXT")
      (footprint "eagle-import:1X01_WITHOUT_TEXT")
      (libsource (lib "eagle-import") (part "M01PTH_WITHOUT_TEXT"))
    )
    (comp (ref "JP177")
      (value "M01PTH_WITHOUT_TEXT")
      (footprint "eagle-import:1X01_WITHOUT_TEXT")
      (libsource (lib "eagle-import") (part "M01PTH_WITHOUT_TEXT"))
    )
    (comp (ref "JP178")
      (value "M01PTH_WITHOUT_TEXT")
      (footprint "eagle-import:1X01_WITHOUT_TEXT")
      (libsource (lib "eagle-import") (part "M01PTH_WITHOUT_TEXT"))
    )
    (comp (ref "JP179")
      (value "M01PTH_WITHOUT_TEXT")
      (footprint "eagle-import:1X01_WITHOUT_TEXT")
      (libsource (lib "eagle-import") (part "M01PTH_WITHOUT_TEXT"))
    )
    (comp (ref "JP180")
      (value "M01PTH_WITHOUT_TEXT")
      (footprint "eagle-import:1X01_WITHOUT_TEXT")
      (libsource (lib "eagle-import") (part "M01PTH_WITHOUT_TEXT"))
    )
    (comp (ref "JP181")
      (value "M01PTH_WITHOUT_TEXT")
      (footprint "eagle-import:1X01_WITHOUT_TEXT")
      (libsource (lib "eagle-import") (part "M01PTH_WITHOUT_TEXT"))
    )
    (comp (ref "JP182")
      (value "M01PTH_WITHOUT_TEXT")
      (footprint "eagle-import:1X01_WITHOUT_TEXT")
      (libsource (lib "eagle-import") (part "M01PTH_WITHOUT_TEXT"))
    )
    (comp (ref "JP183")
      (value "M01PTH_WITHOUT_TEXT")
      (footprint "eagle-import:1X01_WITHOUT_TEXT")
      (libsource (lib "eagle-import") (part "M01PTH_WITHOUT_TEXT"))
    )
    (comp (ref "JP184")
      (value "M01PTH_WITHOUT_TEXT")
      (footprint "eagle-import:1X01_WITHOUT_TEXT")
      (libsource (lib "eagle-import") (part "M01PTH_WITHOUT_TEXT"))
    )
    (comp (ref "JP185")
      (value "M01PTH_WITHOUT_TEXT")
      (footprint "eagle-import:1X01_WITHOUT_TEXT")
      (libsource (lib "eagle-import") (part "M01PTH_WITHOUT_TEXT"))
    )
    (comp (ref "JP186")
      (value "M01PTH_WITHOUT_TEXT")
      (footprint "eagle-import:1X01_WITHOUT_TEXT")
      (libsource (lib "eagle-import") (part "M01PTH_WITHOUT_TEXT"))
    )
    (comp (ref "JP187")
      (value "M01PTH_WITHOUT_TEXT")
      (footprint "eagle-import:1X01_WITHOUT_TEXT")
      (libsource (lib "eagle-import") (part "M01PTH_WITHOUT_TEXT"))
    )
    (comp (ref "JP188")
      (value "M01PTH_WITHOUT_TEXT")
      (footprint "eagle-import:1X01_WITHOUT_TEXT")
      (libsource (lib "eagle-import") (part "M01PTH_WITHOUT_TEXT"))
    )
    (comp (ref "JP189")
      (value "M01PTH_WITHOUT_TEXT")
      (footprint "eagle-import:1X01_WITHOUT_TEXT")
      (libsource (lib "eagle-import") (part "M01PTH_WITHOUT_TEXT"))
    )
    (comp (ref "JP190")
      (value "M01PTH_WITHOUT_TEXT")
      (footprint "eagle-import:1X01_WITHOUT_TEXT")
      (libsource (lib "eagle-import") (part "M01PTH_WITHOUT_TEXT"))
    )
    (comp (ref "JP191")
      (value "M01PTH_WITHOUT_TEXT")
      (footprint "eagle-import:1X01_WITHOUT_TEXT")
      (libsource (lib "eagle-import") (part "M01PTH_WITHOUT_TEXT"))
    )
    (comp (ref "JP192")
      (value "M01PTH_WITHOUT_TEXT")
      (footprint "eagle-import:1X01_WITHOUT_TEXT")
      (libsource (lib "eagle-import") (part "M01PTH_WITHOUT_TEXT"))
    )
    (comp (ref "JP193")
      (value "M01PTH_WITHOUT_TEXT")
      (footprint "eagle-import:1X01_WITHOUT_TEXT")
      (libsource (lib "eagle-import") (part "M01PTH_WITHOUT_TEXT"))
    )
    (comp (ref "JP194")
      (value "M01PTH_WITHOUT_TEXT")
      (footprint "eagle-import:1X01_WITHOUT_TEXT")
      (libsource (lib "eagle-import") (part "M01PTH_WITHOUT_TEXT"))
    )
    (comp (ref "JP195")
      (value "M01PTH_WITHOUT_TEXT")
      (footprint "eagle-import:1X01_WITHOUT_TEXT")
      (libsource (lib "eagle-import") (part "M01PTH_WITHOUT_TEXT"))
    )
    (comp (ref "JP196")
      (value "M01PTH_WITHOUT_TEXT")
      (footprint "eagle-import:1X01_WITHOUT_TEXT")
      (libsource (lib "eagle-import") (part "M01PTH_WITHOUT_TEXT"))
    )
    (comp (ref "JP197")
      (value "M01PTH_WITHOUT_TEXT")
      (footprint "eagle-import:1X01_WITHOUT_TEXT")
      (libsource (lib "eagle-import") (part "M01PTH_WITHOUT_TEXT"))
    )
    (comp (ref "JP198")
      (value "M01PTH_WITHOUT_TEXT")
      (footprint "eagle-import:1X01_WITHOUT_TEXT")
      (libsource (lib "eagle-import") (part "M01PTH_WITHOUT_TEXT"))
    )
    (comp (ref "JP199")
      (value "M01PTH_WITHOUT_TEXT")
      (footprint "eagle-import:1X01_WITHOUT_TEXT")
      (libsource (lib "eagle-import") (part "M01PTH_WITHOUT_TEXT"))
    )
    (comp (ref "JP200")
      (value "M01PTH_WITHOUT_TEXT")
      (footprint "eagle-import:1X01_WITHOUT_TEXT")
      (libsource (lib "eagle-import") (part "M01PTH_WITHOUT_TEXT"))
    )
    (comp (ref "JP201")
      (value "M01PTH_WITHOUT_TEXT")
      (footprint "eagle-import:1X01_WITHOUT_TEXT")
      (libsource (lib "eagle-import") (part "M01PTH_WITHOUT_TEXT"))
    )
    (comp (ref "JP202")
      (value "M01PTH_WITHOUT_TEXT")
      (footprint "eagle-import:1X01_WITHOUT_TEXT")
      (libsource (lib "eagle-import") (part "M01PTH_WITHOUT_TEXT"))
    )
    (comp (ref "JP203")
      (value "M01PTH_WITHOUT_TEXT")
      (footprint "eagle-import:1X01_WITHOUT_TEXT")
      (libsource (lib "eagle-import") (part "M01PTH_WITHOUT_TEXT"))
    )
    (comp (ref "JP204")
      (value "M01PTH_WITHOUT_TEXT")
      (footprint "eagle-import:1X01_WITHOUT_TEXT")
      (libsource (lib "eagle-import") (part "M01PTH_WITHOUT_TEXT"))
    )
    (comp (ref "JP205")
      (value "M01PTH_WITHOUT_TEXT")
      (footprint "eagle-import:1X01_WITHOUT_TEXT")
      (libsource (lib "eagle-import") (part "M01PTH_WITHOUT_TEXT"))
    )
    (comp (ref "JP206")
      (value "M01PTH_WITHOUT_TEXT")
      (footprint "eagle-import:1X01_WITHOUT_TEXT")
      (libsource (lib "eagle-import") (part "M01PTH_WITHOUT_TEXT"))
    )
    (comp (ref "JP207")
      (value "M01PTH_WITHOUT_TEXT")
      (footprint "eagle-import:1X01_WITHOUT_TEXT")
      (libsource (lib "eagle-import") (part "M01PTH_WITHOUT_TEXT"))
    )
    (comp (ref "JP208")
      (value "M01PTH_WITHOUT_TEXT")
      (footprint "eagle-import:1X01_WITHOUT_TEXT")
      (libsource (lib "eagle-import") (part "M01PTH_WITHOUT_TEXT"))
    )
    (comp (ref "JP209")
      (value "M01PTH_WITHOUT_TEXT")
      (footprint "eagle-import:1X01_WITHOUT_TEXT")
      (libsource (lib "eagle-import") (part "M01PTH_WITHOUT_TEXT"))
    )
    (comp (ref "JP210")
      (value "M01PTH_WITHOUT_TEXT")
      (footprint "eagle-import:1X01_WITHOUT_TEXT")
      (libsource (lib "eagle-import") (part "M01PTH_WITHOUT_TEXT"))
    )
    (comp (ref "JP211")
      (value "M01PTH_WITHOUT_TEXT")
      (footprint "eagle-import:1X01_WITHOUT_TEXT")
      (libsource (lib "eagle-import") (part "M01PTH_WITHOUT_TEXT"))
    )
    (comp (ref "JP212")
      (value "M01PTH_WITHOUT_TEXT")
      (footprint "eagle-import:1X01_WITHOUT_TEXT")
      (libsource (lib "eagle-import") (part "M01PTH_WITHOUT_TEXT"))
    )
    (comp (ref "JP213")
      (value "M01PTH_WITHOUT_TEXT")
      (footprint "eagle-import:1X01_WITHOUT_TEXT")
      (libsource (lib "eagle-import") (part "M01PTH_WITHOUT_TEXT"))
    )
    (comp (ref "JP214")
      (value "M01PTH_WITHOUT_TEXT")
      (footprint "eagle-import:1X01_WITHOUT_TEXT")
      (libsource (lib "eagle-import") (part "M01PTH_WITHOUT_TEXT"))
    )
    (comp (ref "JP215")
      (value "M01PTH_WITHOUT_TEXT")
      (footprint "eagle-import:1X01_WITHOUT_TEXT")
      (libsource (lib "eagle-import") (part "M01PTH_WITHOUT_TEXT"))
    )
    (comp (ref "JP216")
      (value "M01PTH_WITHOUT_TEXT")
      (footprint "eagle-import:1X01_WITHOUT_TEXT")
      (libsource (lib "eagle-import") (part "M01PTH_WITHOUT_TEXT"))
    )
    (comp (ref "JP217")
      (value "M01PTH_WITHOUT_TEXT")
      (footprint "eagle-import:1X01_WITHOUT_TEXT")
      (libsource (lib "eagle-import") (part "M01PTH_WITHOUT_TEXT"))
    )
    (comp (ref "JP218")
      (value "M01PTH_WITHOUT_TEXT")
      (footprint "eagle-import:1X01_WITHOUT_TEXT")
      (libsource (lib "eagle-import") (part "M01PTH_WITHOUT_TEXT"))
    )
    (comp (ref "JP219")
      (value "M01PTH_WITHOUT_TEXT")
      (footprint "eagle-import:1X01_WITHOUT_TEXT")
      (libsource (lib "eagle-import") (part "M01PTH_WITHOUT_TEXT"))
    )
    (comp (ref "JP220")
      (value "M01PTH_WITHOUT_TEXT")
      (footprint "eagle-import:1X01_WITHOUT_TEXT")
      (libsource (lib "eagle-import") (part "M01PTH_WITHOUT_TEXT"))
    )
    (comp (ref "JP221")
      (value "M01PTH_WITHOUT_TEXT")
      (footprint "eagle-import:1X01_WITHOUT_TEXT")
      (libsource (lib "eagle-import") (part "M01PTH_WITHOUT_TEXT"))
    )
    (comp (ref "JP222")
      (value "M01PTH_WITHOUT_TEXT")
      (footprint "eagle-import:1X01_WITHOUT_TEXT")
      (libsource (lib "eagle-import") (part "M01PTH_WITHOUT_TEXT"))
    )
    (comp (ref "JP223")
      (value "M01PTH_WITHOUT_TEXT")
      (footprint "eagle-import:1X01_WITHOUT_TEXT")
      (libsource (lib "eagle-import") (part "M01PTH_WITHOUT_TEXT"))
    )
    (comp (ref "JP224")
      (value "M01PTH_WITHOUT_TEXT")
      (footprint "eagle-import:1X01_WITHOUT_TEXT")
      (libsource (lib "eagle-import") (part "M01PTH_WITHOUT_TEXT"))
    )
    (comp (ref "JP225")
      (value "M01PTH_WITHOUT_TEXT")
      (footprint "eagle-import:1X01_WITHOUT_TEXT")
      (libsource (lib "eagle-import") (part "M01PTH_WITHOUT_TEXT"))
    )
    (comp (ref "JP226")
      (value "M01PTH_WITHOUT_TEXT")
      (footprint "eagle-import:1X01_WITHOUT_TEXT")
      (libsource (lib "eagle-import") (part "M01PTH_WITHOUT_TEXT"))
    )
    (comp (ref "JP227")
      (value "M01PTH_WITHOUT_TEXT")
      (footprint "eagle-import:1X01_WITHOUT_TEXT")
      (libsource (lib "eagle-import") (part "M01PTH_WITHOUT_TEXT"))
    )
    (comp (ref "JP228")
      (value "M01PTH_WITHOUT_TEXT")
      (footprint "eagle-import:1X01_WITHOUT_TEXT")
      (libsource (lib "eagle-import") (part "M01PTH_WITHOUT_TEXT"))
    )
    (comp (ref "JP229")
      (value "M01PTH_WITHOUT_TEXT")
      (footprint "eagle-import:1X01_WITHOUT_TEXT")
      (libsource (lib "eagle-import") (part "M01PTH_WITHOUT_TEXT"))
    )
    (comp (ref "JP230")
      (value "M01PTH_WITHOUT_TEXT")
      (footprint "eagle-import:1X01_WITHOUT_TEXT")
      (libsource (lib "eagle-import") (part "M01PTH_WITHOUT_TEXT"))
    )
    (comp (ref "JP231")
      (value "M01PTH_WITHOUT_TEXT")
      (footprint "eagle-import:1X01_WITHOUT_TEXT")
      (libsource (lib "eagle-import") (part "M01PTH_WITHOUT_TEXT"))
    )
    (comp (ref "JP232")
      (value "M01PTH_WITHOUT_TEXT")
      (footprint "eagle-import:1X01_WITHOUT_TEXT")
      (libsource (lib "eagle-import") (part "M01PTH_WITHOUT_TEXT"))
    )
    (comp (ref "JP233")
      (value "M01PTH_WITHOUT_TEXT")
      (footprint "eagle-import:1X01_WITHOUT_TEXT")
      (libsource (lib "eagle-import") (part "M01PTH_WITHOUT_TEXT"))
    )
    (comp (ref "JP234")
      (value "M01PTH_WITHOUT_TEXT")
      (footprint "eagle-import:1X01_WITHOUT_TEXT")
      (libsource (lib "eagle-import") (part "M01PTH_WITHOUT_TEXT"))
    )
    (comp (ref "JP235")
      (value "M01PTH_WITHOUT_TEXT")
      (footprint "eagle-import:1X01_WITHOUT_TEXT")
      (libsource (lib "eagle-import") (part "M01PTH_WITHOUT_TEXT"))
    )
    (comp (ref "JP236")
      (value "M01PTH_WITHOUT_TEXT")
      (footprint "eagle-import:1X01_WITHOUT_TEXT")
      (libsource (lib "eagle-import") (part "M01PTH_WITHOUT_TEXT"))
    )
    (comp (ref "JP237")
      (value "M01PTH_WITHOUT_TEXT")
      (footprint "eagle-import:1X01_WITHOUT_TEXT")
      (libsource (lib "eagle-import") (part "M01PTH_WITHOUT_TEXT"))
    )
    (comp (ref "JP238")
      (value "M01PTH_WITHOUT_TEXT")
      (footprint "eagle-import:1X01_WITHOUT_TEXT")
      (libsource (lib "eagle-import") (part "M01PTH_WITHOUT_TEXT"))
    )
    (comp (ref "JP239")
      (value "M01PTH_WITHOUT_TEXT")
      (footprint "eagle-import:1X01_WITHOUT_TEXT")
      (libsource (lib "eagle-import") (part "M01PTH_WITHOUT_TEXT"))
    )
    (comp (ref "JP240")
      (value "M01PTH_WITHOUT_TEXT")
      (footprint "eagle-import:1X01_WITHOUT_TEXT")
      (libsource (lib "eagle-import") (part "M01PTH_WITHOUT_TEXT"))
    )
    (comp (ref "JP241")
      (value "M01PTH_WITHOUT_TEXT")
      (footprint "eagle-import:1X01_WITHOUT_TEXT")
      (libsource (lib "eagle-import") (part "M01PTH_WITHOUT_TEXT"))
    )
    (comp (ref "JP242")
      (value "M01PTH_WITHOUT_TEXT")
      (footprint "eagle-import:1X01_WITHOUT_TEXT")
      (libsource (lib "eagle-import") (part "M01PTH_WITHOUT_TEXT"))
    )
    (comp (ref "JP243")
      (value "M01PTH_WITHOUT_TEXT")
      (footprint "eagle-import:1X01_WITHOUT_TEXT")
      (libsource (lib "eagle-import") (part "M01PTH_WITHOUT_TEXT"))
    )
    (comp (ref "JP244")
      (value "M01PTH_WITHOUT_TEXT")
      (footprint "eagle-import:1X01_WITHOUT_TEXT")
      (libsource (lib "eagle-import") (part "M01PTH_WITHOUT_TEXT"))
    )
    (comp (ref "JP245")
      (value "M01PTH_WITHOUT_TEXT")
      (footprint "eagle-import:1X01_WITHOUT_TEXT")
      (libsource (lib "eagle-import") (part "M01PTH_WITHOUT_TEXT"))
    )
    (comp (ref "JP246")
      (value "M01PTH_WITHOUT_TEXT")
      (footprint "eagle-import:1X01_WITHOUT_TEXT")
      (libsource (lib "eagle-import") (part "M01PTH_WITHOUT_TEXT"))
    )
    (comp (ref "JP247")
      (value "M01PTH_WITHOUT_TEXT")
      (footprint "eagle-import:1X01_WITHOUT_TEXT")
      (libsource (lib "eagle-import") (part "M01PTH_WITHOUT_TEXT"))
    )
    (comp (ref "JP248")
      (value "M01PTH_WITHOUT_TEXT")
      (footprint "eagle-import:1X01_WITHOUT_TEXT")
      (libsource (lib "eagle-import") (part "M01PTH_WITHOUT_TEXT"))
    )
    (comp (ref "JP249")
      (value "M01PTH_WITHOUT_TEXT")
      (footprint "eagle-import:1X01_WITHOUT_TEXT")
      (libsource (lib "eagle-import") (part "M01PTH_WITHOUT_TEXT"))
    )
    (comp (ref "JP250")
      (value "M01PTH_WITHOUT_TEXT")
      (footprint "eagle-import:1X01_WITHOUT_TEXT")
      (libsource (lib "eagle-import") (part "M01PTH_WITHOUT_TEXT"))
    )
    (comp (ref "JP251")
      (value "M01PTH_WITHOUT_TEXT")
      (footprint "eagle-import:1X01_WITHOUT_TEXT")
      (libsource (lib "eagle-import") (part "M01PTH_WITHOUT_TEXT"))
    )
    (comp (ref "JP252")
      (value "M01PTH_WITHOUT_TEXT")
      (footprint "eagle-import:1X01_WITHOUT_TEXT")
      (libsource (lib "eagle-import") (part "M01PTH_WITHOUT_TEXT"))
    )
    (comp (ref "JP253")
      (value "M01PTH_WITHOUT_TEXT")
      (footprint "eagle-import:1X01_WITHOUT_TEXT")
      (libsource (lib "eagle-import") (part "M01PTH_WITHOUT_TEXT"))
    )
    (comp (ref "JP254")
      (value "M01PTH_WITHOUT_TEXT")
      (footprint "eagle-import:1X01_WITHOUT_TEXT")
      (libsource (lib "eagle-import") (part "M01PTH_WITHOUT_TEXT"))
    )
    (comp (ref "JP255")
      (value "M01PTH_WITHOUT_TEXT")
      (footprint "eagle-import:1X01_WITHOUT_TEXT")
      (libsource (lib "eagle-import") (part "M01PTH_WITHOUT_TEXT"))
    )
    (comp (ref "JP256")
      (value "M01PTH_WITHOUT_TEXT")
      (footprint "eagle-import:1X01_WITHOUT_TEXT")
      (libsource (lib "eagle-import") (part "M01PTH_WITHOUT_TEXT"))
    )
    (comp (ref "JP257")
      (value "M01PTH_WITHOUT_TEXT")
      (footprint "eagle-import:1X01_WITHOUT_TEXT")
      (libsource (lib "eagle-import") (part "M01PTH_WITHOUT_TEXT"))
    )
    (comp (ref "JP258")
      (value "M01PTH_WITHOUT_TEXT")
      (footprint "eagle-import:1X01_WITHOUT_TEXT")
      (libsource (lib "eagle-import") (part "M01PTH_WITHOUT_TEXT"))
    )
    (comp (ref "JP259")
      (value "M01PTH_WITHOUT_TEXT")
      (footprint "eagle-import:1X01_WITHOUT_TEXT")
      (libsource (lib "eagle-import") (part "M01PTH_WITHOUT_TEXT"))
    )
    (comp (ref "JP260")
      (value "M01PTH_WITHOUT_TEXT")
      (footprint "eagle-import:1X01_WITHOUT_TEXT")
      (libsource (lib "eagle-import") (part "M01PTH_WITHOUT_TEXT"))
    )
    (comp (ref "JP261")
      (value "M01PTH_WITHOUT_TEXT")
      (footprint "eagle-import:1X01_WITHOUT_TEXT")
      (libsource (lib "eagle-import") (part "M01PTH_WITHOUT_TEXT"))
    )
    (comp (ref "JP262")
      (value "M01PTH_WITHOUT_TEXT")
      (footprint "eagle-import:1X01_WITHOUT_TEXT")
      (libsource (lib "eagle-import") (part "M01PTH_WITHOUT_TEXT"))
    )
    (comp (ref "JP263")
      (value "M01PTH_WITHOUT_TEXT")
      (footprint "eagle-import:1X01_WITHOUT_TEXT")
      (libsource (lib "eagle-import") (part "M01PTH_WITHOUT_TEXT"))
    )
    (comp (ref "JP264")
      (value "M01PTH_WITHOUT_TEXT")
      (footprint "eagle-import:1X01_WITHOUT_TEXT")
      (libsource (lib "eagle-import") (part "M01PTH_WITHOUT_TEXT"))
    )
    (comp (ref "JP265")
      (value "M01PTH_WITHOUT_TEXT")
      (footprint "eagle-import:1X01_WITHOUT_TEXT")
      (libsource (lib "eagle-import") (part "M01PTH_WITHOUT_TEXT"))
    )
    (comp (ref "JP266")
      (value "M01PTH_WITHOUT_TEXT")
      (footprint "eagle-import:1X01_WITHOUT_TEXT")
      (libsource (lib "eagle-import") (part "M01PTH_WITHOUT_TEXT"))
    )
    (comp (ref "JP267")
      (value "M01PTH_WITHOUT_TEXT")
      (footprint "eagle-import:1X01_WITHOUT_TEXT")
      (libsource (lib "eagle-import") (part "M01PTH_WITHOUT_TEXT"))
    )
    (comp (ref "JP268")
      (value "M01PTH_WITHOUT_TEXT")
      (footprint "eagle-import:1X01_WITHOUT_TEXT")
      (libsource (lib "eagle-import") (part "M01PTH_WITHOUT_TEXT"))
    )
    (comp (ref "JP269")
      (value "M01PTH_WITHOUT_TEXT")
      (footprint "eagle-import:1X01_WITHOUT_TEXT")
      (libsource (lib "eagle-import") (part "M01PTH_WITHOUT_TEXT"))
    )
    (comp (ref "JP270")
      (value "M01PTH_WITHOUT_TEXT")
      (footprint "eagle-import:1X01_WITHOUT_TEXT")
      (libsource (lib "eagle-import") (part "M01PTH_WITHOUT_TEXT"))
    )
    (comp (ref "JP271")
      (value "M01PTH_WITHOUT_TEXT")
      (footprint "eagle-import:1X01_WITHOUT_TEXT")
      (libsource (lib "eagle-import") (part "M01PTH_WITHOUT_TEXT"))
    )
    (comp (ref "JP272")
      (value "M01PTH_WITHOUT_TEXT")
      (footprint "eagle-import:1X01_WITHOUT_TEXT")
      (libsource (lib "eagle-import") (part "M01PTH_WITHOUT_TEXT"))
    )
    (comp (ref "JP273")
      (value "M01PTH_WITHOUT_TEXT")
      (footprint "eagle-import:1X01_WITHOUT_TEXT")
      (libsource (lib "eagle-import") (part "M01PTH_WITHOUT_TEXT"))
    )
    (comp (ref "JP274")
      (value "M01PTH_WITHOUT_TEXT")
      (footprint "eagle-import:1X01_WITHOUT_TEXT")
      (libsource (lib "eagle-import") (part "M01PTH_WITHOUT_TEXT"))
    )
    (comp (ref "JP275")
      (value "M01PTH_WITHOUT_TEXT")
      (footprint "eagle-import:1X01_WITHOUT_TEXT")
      (libsource (lib "eagle-import") (part "M01PTH_WITHOUT_TEXT"))
    )
    (comp (ref "JP276")
      (value "M01PTH_WITHOUT_TEXT")
      (footprint "eagle-import:1X01_WITHOUT_TEXT")
      (libsource (lib "eagle-import") (part "M01PTH_WITHOUT_TEXT"))
    )
    (comp (ref "JP277")
      (value "M01PTH_WITHOUT_TEXT")
      (footprint "eagle-import:1X01_WITHOUT_TEXT")
      (libsource (lib "eagle-import") (part "M01PTH_WITHOUT_TEXT"))
    )
    (comp (ref "JP278")
      (value "M01PTH_WITHOUT_TEXT")
      (footprint "eagle-import:1X01_WITHOUT_TEXT")
      (libsource (lib "eagle-import") (part "M01PTH_WITHOUT_TEXT"))
    )
    (comp (ref "JP279")
      (value "M01PTH_WITHOUT_TEXT")
      (footprint "eagle-import:1X01_WITHOUT_TEXT")
      (libsource (lib "eagle-import") (part "M01PTH_WITHOUT_TEXT"))
    )
    (comp (ref "JP280")
      (value "M01PTH_WITHOUT_TEXT")
      (footprint "eagle-import:1X01_WITHOUT_TEXT")
      (libsource (lib "eagle-import") (part "M01PTH_WITHOUT_TEXT"))
    )
    (comp (ref "JP281")
      (value "M01PTH_WITHOUT_TEXT")
      (footprint "eagle-import:1X01_WITHOUT_TEXT")
      (libsource (lib "eagle-import") (part "M01PTH_WITHOUT_TEXT"))
    )
    (comp (ref "JP282")
      (value "M01PTH_WITHOUT_TEXT")
      (footprint "eagle-import:1X01_WITHOUT_TEXT")
      (libsource (lib "eagle-import") (part "M01PTH_WITHOUT_TEXT"))
    )
    (comp (ref "JP283")
      (value "M01PTH_WITHOUT_TEXT")
      (footprint "eagle-import:1X01_WITHOUT_TEXT")
      (libsource (lib "eagle-import") (part "M01PTH_WITHOUT_TEXT"))
    )
    (comp (ref "JP284")
      (value "M01PTH_WITHOUT_TEXT")
      (footprint "eagle-import:1X01_WITHOUT_TEXT")
      (libsource (lib "eagle-import") (part "M01PTH_WITHOUT_TEXT"))
    )
    (comp (ref "JP285")
      (value "M01PTH_WITHOUT_TEXT")
      (footprint "eagle-import:1X01_WITHOUT_TEXT")
      (libsource (lib "eagle-import") (part "M01PTH_WITHOUT_TEXT"))
    )
    (comp (ref "JP286")
      (value "M01PTH_WITHOUT_TEXT")
      (footprint "eagle-import:1X01_WITHOUT_TEXT")
      (libsource (lib "eagle-import") (part "M01PTH_WITHOUT_TEXT"))
    )
    (comp (ref "JP287")
      (value "M01PTH_WITHOUT_TEXT")
      (footprint "eagle-import:1X01_WITHOUT_TEXT")
      (libsource (lib "eagle-import") (part "M01PTH_WITHOUT_TEXT"))
    )
    (comp (ref "JP288")
      (value "M01PTH_WITHOUT_TEXT")
      (footprint "eagle-import:1X01_WITHOUT_TEXT")
      (libsource (lib "eagle-import") (part "M01PTH_WITHOUT_TEXT"))
    )
    (comp (ref "JP289")
      (value "M01PTH_WITHOUT_TEXT")
      (footprint "eagle-import:1X01_WITHOUT_TEXT")
      (libsource (lib "eagle-import") (part "M01PTH_WITHOUT_TEXT"))
    )
    (comp (ref "JP290")
      (value "M01PTH_WITHOUT_TEXT")
      (footprint "eagle-import:1X01_WITHOUT_TEXT")
      (libsource (lib "eagle-import") (part "M01PTH_WITHOUT_TEXT"))
    )
    (comp (ref "JP291")
      (value "M01PTH_WITHOUT_TEXT")
      (footprint "eagle-import:1X01_WITHOUT_TEXT")
      (libsource (lib "eagle-import") (part "M01PTH_WITHOUT_TEXT"))
    )
    (comp (ref "JP292")
      (value "M01PTH_WITHOUT_TEXT")
      (footprint "eagle-import:1X01_WITHOUT_TEXT")
      (libsource (lib "eagle-import") (part "M01PTH_WITHOUT_TEXT"))
    )
    (comp (ref "JP293")
      (value "M01PTH_WITHOUT_TEXT")
      (footprint "eagle-import:1X01_WITHOUT_TEXT")
      (libsource (lib "eagle-import") (part "M01PTH_WITHOUT_TEXT"))
    )
    (comp (ref "JP294")
      (value "M01PTH_WITHOUT_TEXT")
      (footprint "eagle-import:1X01_WITHOUT_TEXT")
      (libsource (lib "eagle-import") (part "M01PTH_WITHOUT_TEXT"))
    )
    (comp (ref "JP295")
      (value "M01PTH_WITHOUT_TEXT")
      (footprint "eagle-import:1X01_WITHOUT_TEXT")
      (libsource (lib "eagle-import") (part "M01PTH_WITHOUT_TEXT"))
    )
    (comp (ref "JP296")
      (value "M01PTH_WITHOUT_TEXT")
      (footprint "eagle-import:1X01_WITHOUT_TEXT")
      (libsource (lib "eagle-import") (part "M01PTH_WITHOUT_TEXT"))
    )
    (comp (ref "JP297")
      (value "M01PTH_WITHOUT_TEXT")
      (footprint "eagle-import:1X01_WITHOUT_TEXT")
      (libsource (lib "eagle-import") (part "M01PTH_WITHOUT_TEXT"))
    )
    (comp (ref "JP298")
      (value "M01PTH_WITHOUT_TEXT")
      (footprint "eagle-import:1X01_WITHOUT_TEXT")
      (libsource (lib "eagle-import") (part "M01PTH_WITHOUT_TEXT"))
    )
    (comp (ref "JP299")
      (value "M01PTH_WITHOUT_TEXT")
      (footprint "eagle-import:1X01_WITHOUT_TEXT")
      (libsource (lib "eagle-import") (part "M01PTH_WITHOUT_TEXT"))
    )
    (comp (ref "JP300")
      (value "M01PTH_WITHOUT_TEXT")
      (footprint "eagle-import:1X01_WITHOUT_TEXT")
      (libsource (lib "eagle-import") (part "M01PTH_WITHOUT_TEXT"))
    )
    (comp (ref "JP901")
      (value "M01PTH_SMD_1.27X0.635MM_NO_SILK")
      (footprint "eagle-import:1X01_SMD_1.27X0.635MM_NO_SILK")
      (libsource (lib "eagle-import") (part "M01PTH_SMD_1.27X0.635MM_NO_SILK"))
    )
    (comp (ref "JP902")
      (value "M01PTH_SMD_1.27X0.635MM_NO_SILK")
      (footprint "eagle-import:1X01_SMD_1.27X0.635MM_NO_SILK")
      (libsource (lib "eagle-import") (part "M01PTH_SMD_1.27X0.635MM_NO_SILK"))
    )
    (comp (ref "JP903")
      (value "M01PTH_SMD_1.27X0.635MM_NO_SILK")
      (footprint "eagle-import:1X01_SMD_1.27X0.635MM_NO_SILK")
      (libsource (lib "eagle-import") (part "M01PTH_SMD_1.27X0.635MM_NO_SILK"))
    )
    (comp (ref "JP904")
      (value "M01PTH_SMD_1.27X0.635MM_NO_SILK")
      (footprint "eagle-import:1X01_SMD_1.27X0.635MM_NO_SILK")
      (libsource (lib "eagle-import") (part "M01PTH_SMD_1.27X0.635MM_NO_SILK"))
    )
    (comp (ref "JP905")
      (value "M01PTH_SMD_1.27X0.635MM_NO_SILK")
      (footprint "eagle-import:1X01_SMD_1.27X0.635MM_NO_SILK")
      (libsource (lib "eagle-import") (part "M01PTH_SMD_1.27X0.635MM_NO_SILK"))
    )
    (comp (ref "JP906")
      (value "M01PTH_SMD_1.27X0.635MM_NO_SILK")
      (footprint "eagle-import:1X01_SMD_1.27X0.635MM_NO_SILK")
      (libsource (lib "eagle-import") (part "M01PTH_SMD_1.27X0.635MM_NO_SILK"))
    )
    (comp (ref "JP907")
      (value "M01PTH_SMD_1.27X0.635MM_NO_SILK")
      (footprint "eagle-import:1X01_SMD_1.27X0.635MM_NO_SILK")
      (libsource (lib "eagle-import") (part "M01PTH_SMD_1.27X0.635MM_NO_SILK"))
    )
    (comp (ref "JP908")
      (value "M01PTH_SMD_1.27X0.635MM_NO_SILK")
      (footprint "eagle-import:1X01_SMD_1.27X0.635MM_NO_SILK")
      (libsource (lib "eagle-import") (part "M01PTH_SMD_1.27X0.635MM_NO_SILK"))
    )
    (comp (ref "JP909")
      (value "M01PTH_SMD_1.27X0.635MM_NO_SILK")
      (footprint "eagle-import:1X01_SMD_1.27X0.635MM_NO_SILK")
      (libsource (lib "eagle-import") (part "M01PTH_SMD_1.27X0.635MM_NO_SILK"))
    )
    (comp (ref "JP910")
      (value "M01PTH_SMD_1.27X0.635MM_NO_SILK")
      (footprint "eagle-import:1X01_SMD_1.27X0.635MM_NO_SILK")
      (libsource (lib "eagle-import") (part "M01PTH_SMD_1.27X0.635MM_NO_SILK"))
    )
    (comp (ref "JP911")
      (value "M01PTH_SMD_1.27X0.635MM_NO_SILK")
      (footprint "eagle-import:1X01_SMD_1.27X0.635MM_NO_SILK")
      (libsource (lib "eagle-import") (part "M01PTH_SMD_1.27X0.635MM_NO_SILK"))
    )
    (comp (ref "JP912")
      (value "M01PTH_SMD_1.27X0.635MM_NO_SILK")
      (footprint "eagle-import:1X01_SMD_1.27X0.635MM_NO_SILK")
      (libsource (lib "eagle-import") (part "M01PTH_SMD_1.27X0.635MM_NO_SILK"))
    )
    (comp (ref "JP913")
      (value "M01PTH_SMD_1.27X0.635MM_NO_SILK")
      (footprint "eagle-import:1X01_SMD_1.27X0.635MM_NO_SILK")
      (libsource (lib "eagle-import") (part "M01PTH_SMD_1.27X0.635MM_NO_SILK"))
    )
    (comp (ref "JP914")
      (value "M01PTH_SMD_1.27X0.635MM_NO_SILK")
      (footprint "eagle-import:1X01_SMD_1.27X0.635MM_NO_SILK")
      (libsource (lib "eagle-import") (part "M01PTH_SMD_1.27X0.635MM_NO_SILK"))
    )
    (comp (ref "JP915")
      (value "M01PTH_SMD_1.27X0.635MM_NO_SILK")
      (footprint "eagle-import:1X01_SMD_1.27X0.635MM_NO_SILK")
      (libsource (lib "eagle-import") (part "M01PTH_SMD_1.27X0.635MM_NO_SILK"))
    )
    (comp (ref "JP916")
      (value "M01PTH_SMD_1.27X0.635MM_NO_SILK")
      (footprint "eagle-import:1X01_SMD_1.27X0.635MM_NO_SILK")
      (libsource (lib "eagle-import") (part "M01PTH_SMD_1.27X0.635MM_NO_SILK"))
    )
    (comp (ref "JP917")
      (value "M01PTH_SMD_1.27X0.635MM_NO_SILK")
      (footprint "eagle-import:1X01_SMD_1.27X0.635MM_NO_SILK")
      (libsource (lib "eagle-import") (part "M01PTH_SMD_1.27X0.635MM_NO_SILK"))
    )
    (comp (ref "JP918")
      (value "M01PTH_SMD_1.27X0.635MM_NO_SILK")
      (footprint "eagle-import:1X01_SMD_1.27X0.635MM_NO_SILK")
      (libsource (lib "eagle-import") (part "M01PTH_SMD_1.27X0.635MM_NO_SILK"))
    )
    (comp (ref "JP919")
      (value "M01PTH_SMD_1.27X0.635MM_NO_SILK")
      (footprint "eagle-import:1X01_SMD_1.27X0.635MM_NO_SILK")
      (libsource (lib "eagle-import") (part "M01PTH_SMD_1.27X0.635MM_NO_SILK"))
    )
    (comp (ref "JP920")
      (value "M01PTH_SMD_1.27X0.635MM_NO_SILK")
      (footprint "eagle-import:1X01_SMD_1.27X0.635MM_NO_SILK")
      (libsource (lib "eagle-import") (part "M01PTH_SMD_1.27X0.635MM_NO_SILK"))
    )
    (comp (ref "JP921")
      (value "M01PTH_SMD_1.27X0.635MM_NO_SILK")
      (footprint "eagle-import:1X01_SMD_1.27X0.635MM_NO_SILK")
      (libsource (lib "eagle-import") (part "M01PTH_SMD_1.27X0.635MM_NO_SILK"))
    )
    (comp (ref "JP922")
      (value "M01PTH_SMD_1.27X0.635MM_NO_SILK")
      (footprint "eagle-import:1X01_SMD_1.27X0.635MM_NO_SILK")
      (libsource (lib "eagle-import") (part "M01PTH_SMD_1.27X0.635MM_NO_SILK"))
    )
    (comp (ref "JP923")
      (value "M01PTH_SMD_1.27X0.635MM_NO_SILK")
      (footprint "eagle-import:1X01_SMD_1.27X0.635MM_NO_SILK")
      (libsource (lib "eagle-import") (part "M01PTH_SMD_1.27X0.635MM_NO_SILK"))
    )
    (comp (ref "JP924")
      (value "M01PTH_SMD_1.27X0.635MM_NO_SILK")
      (footprint "eagle-import:1X01_SMD_1.27X0.635MM_NO_SILK")
      (libsource (lib "eagle-import") (part "M01PTH_SMD_1.27X0.635MM_NO_SILK"))
    )
    (comp (ref "JP925")
      (value "M01PTH_SMD_1.27X0.635MM_NO_SILK")
      (footprint "eagle-import:1X01_SMD_1.27X0.635MM_NO_SILK")
      (libsource (lib "eagle-import") (part "M01PTH_SMD_1.27X0.635MM_NO_SILK"))
    )
    (comp (ref "JP926")
      (value "M01PTH_SMD_1.27X0.635MM_NO_SILK")
      (footprint "eagle-import:1X01_SMD_1.27X0.635MM_NO_SILK")
      (libsource (lib "eagle-import") (part "M01PTH_SMD_1.27X0.635MM_NO_SILK"))
    )
    (comp (ref "JP927")
      (value "M01PTH_SMD_1.27X0.635MM_NO_SILK")
      (footprint "eagle-import:1X01_SMD_1.27X0.635MM_NO_SILK")
      (libsource (lib "eagle-import") (part "M01PTH_SMD_1.27X0.635MM_NO_SILK"))
    )
    (comp (ref "JP928")
      (value "M01PTH_SMD_1.27X0.635MM_NO_SILK")
      (footprint "eagle-import:1X01_SMD_1.27X0.635MM_NO_SILK")
      (libsource (lib "eagle-import") (part "M01PTH_SMD_1.27X0.635MM_NO_SILK"))
    )
    (comp (ref "JP929")
      (value "M01PTH_SMD_1.27X0.635MM_NO_SILK")
      (footprint "eagle-import:1X01_SMD_1.27X0.635MM_NO_SILK")
      (libsource (lib "eagle-import") (part "M01PTH_SMD_1.27X0.635MM_NO_SILK"))
    )
    (comp (ref "JP930")
      (value "M01PTH_SMD_1.27X0.635MM_NO_SILK")
      (footprint "eagle-import:1X01_SMD_1.27X0.635MM_NO_SILK")
      (libsource (lib "eagle-import") (part "M01PTH_SMD_1.27X0.635MM_NO_SILK"))
    )
    (comp (ref "JP931")
      (value "M01PTH_SMD_1.27X0.635MM_NO_SILK")
      (footprint "eagle-import:1X01_SMD_1.27X0.635MM_NO_SILK")
      (libsource (lib "eagle-import") (part "M01PTH_SMD_1.27X0.635MM_NO_SILK"))
    )
    (comp (ref "JP932")
      (value "M01PTH_SMD_1.27X0.635MM_NO_SILK")
      (footprint "eagle-import:1X01_SMD_1.27X0.635MM_NO_SILK")
      (libsource (lib "eagle-import") (part "M01PTH_SMD_1.27X0.635MM_NO_SILK"))
    )
    (comp (ref "JP933")
      (value "M01PTH_SMD_1.27X0.635MM_NO_SILK")
      (footprint "eagle-import:1X01_SMD_1.27X0.635MM_NO_SILK")
      (libsource (lib "eagle-import") (part "M01PTH_SMD_1.27X0.635MM_NO_SILK"))
    )
    (comp (ref "JP934")
      (value "M01PTH_SMD_1.27X0.635MM_NO_SILK")
      (footprint "eagle-import:1X01_SMD_1.27X0.635MM_NO_SILK")
      (libsource (lib "eagle-import") (part "M01PTH_SMD_1.27X0.635MM_NO_SILK"))
    )
    (comp (ref "JP935")
      (value "M01PTH_SMD_1.27X0.635MM_NO_SILK")
      (footprint "eagle-import:1X01_SMD_1.27X0.635MM_NO_SILK")
      (libsource (lib "eagle-import") (part "M01PTH_SMD_1.27X0.635MM_NO_SILK"))
    )
    (comp (ref "JP936")
      (value "M01PTH_SMD_1.27X0.635MM_NO_SILK")
      (footprint "eagle-import:1X01_SMD_1.27X0.635MM_NO_SILK")
      (libsource (lib "eagle-import") (part "M01PTH_SMD_1.27X0.635MM_NO_SILK"))
    )
    (comp (ref "JP937")
      (value "M01PTH_SMD_1.27X0.635MM_NO_SILK")
      (footprint "eagle-import:1X01_SMD_1.27X0.635MM_NO_SILK")
      (libsource (lib "eagle-import") (part "M01PTH_SMD_1.27X0.635MM_NO_SILK"))
    )
    (comp (ref "JP938")
      (value "M01PTH_SMD_1.27X0.635MM_NO_SILK")
      (footprint "eagle-import:1X01_SMD_1.27X0.635MM_NO_SILK")
      (libsource (lib "eagle-import") (part "M01PTH_SMD_1.27X0.635MM_NO_SILK"))
    )
    (comp (ref "JP939")
      (value "M01PTH_SMD_1.27X0.635MM_NO_SILK")
      (footprint "eagle-import:1X01_SMD_1.27X0.635MM_NO_SILK")
      (libsource (lib "eagle-import") (part "M01PTH_SMD_1.27X0.635MM_NO_SILK"))
    )
    (comp (ref "JP940")
      (value "M01PTH_SMD_1.27X0.635MM_NO_SILK")
      (footprint "eagle-import:1X01_SMD_1.27X0.635MM_NO_SILK")
      (libsource (lib "eagle-import") (part "M01PTH_SMD_1.27X0.635MM_NO_SILK"))
    )
    (comp (ref "JP941")
      (value "M01PTH_SMD_1.27X0.635MM_NO_SILK")
      (footprint "eagle-import:1X01_SMD_1.27X0.635MM_NO_SILK")
      (libsource (lib "eagle-import") (part "M01PTH_SMD_1.27X0.635MM_NO_SILK"))
    )
    (comp (ref "JP942")
      (value "M01PTH_SMD_1.27X0.635MM_NO_SILK")
      (footprint "eagle-import:1X01_SMD_1.27X0.635MM_NO_SILK")
      (libsource (lib "eagle-import") (part "M01PTH_SMD_1.27X0.635MM_NO_SILK"))
    )
    (comp (ref "JP943")
      (value "M01PTH_SMD_1.27X0.635MM_NO_SILK")
      (footprint "eagle-import:1X01_SMD_1.27X0.635MM_NO_SILK")
      (libsource (lib "eagle-import") (part "M01PTH_SMD_1.27X0.635MM_NO_SILK"))
    )
    (comp (ref "JP944")
      (value "M01PTH_SMD_1.27X0.635MM_NO_SILK")
      (footprint "eagle-import:1X01_SMD_1.27X0.635MM_NO_SILK")
      (libsource (lib "eagle-import") (part "M01PTH_SMD_1.27X0.635MM_NO_SILK"))
    )
    (comp (ref "JP945")
      (value "M01PTH_SMD_1.27X0.635MM_NO_SILK")
      (footprint "eagle-import:1X01_SMD_1.27X0.635MM_NO_SILK")
      (libsource (lib "eagle-import") (part "M01PTH_SMD_1.27X0.635MM_NO_SILK"))
    )
    (comp (ref "JP946")
      (value "M01PTH_SMD_1.27X0.635MM_NO_SILK")
      (footprint "eagle-import:1X01_SMD_1.27X0.635MM_NO_SILK")
      (libsource (lib "eagle-import") (part "M01PTH_SMD_1.27X0.635MM_NO_SILK"))
    )
    (comp (ref "JP947")
      (value "M01PTH_SMD_1.27X0.635MM_NO_SILK")
      (footprint "eagle-import:1X01_SMD_1.27X0.635MM_NO_SILK")
      (libsource (lib "eagle-import") (part "M01PTH_SMD_1.27X0.635MM_NO_SILK"))
    )
    (comp (ref "JP948")
      (value "M01PTH_SMD_1.27X0.635MM_NO_SILK")
      (footprint "eagle-import:1X01_SMD_1.27X0.635MM_NO_SILK")
      (libsource (lib "eagle-import") (part "M01PTH_SMD_1.27X0.635MM_NO_SILK"))
    )
    (comp (ref "JP949")
      (value "M01PTH_SMD_1.27X0.635MM_NO_SILK")
      (footprint "eagle-import:1X01_SMD_1.27X0.635MM_NO_SILK")
      (libsource (lib "eagle-import") (part "M01PTH_SMD_1.27X0.635MM_NO_SILK"))
    )
    (comp (ref "JP950")
      (value "M01PTH_SMD_1.27X0.635MM_NO_SILK")
      (footprint "eagle-import:1X01_SMD_1.27X0.635MM_NO_SILK")
      (libsource (lib "eagle-import") (part "M01PTH_SMD_1.27X0.635MM_NO_SILK"))
    )
    (comp (ref "JP951")
      (value "M01PTH_SMD_1.27X0.635MM_NO_SILK")
      (footprint "eagle-import:1X01_SMD_1.27X0.635MM_NO_SILK")
      (libsource (lib "eagle-import") (part "M01PTH_SMD_1.27X0.635MM_NO_SILK"))
    )
    (comp (ref "JP952")
      (value "M01PTH_SMD_1.27X0.635MM_NO_SILK")
      (footprint "eagle-import:1X01_SMD_1.27X0.635MM_NO_SILK")
      (libsource (lib "eagle-import") (part "M01PTH_SMD_1.27X0.635MM_NO_SILK"))
    )
    (comp (ref "JP953")
      (value "M01PTH_SMD_1.27X0.635MM_NO_SILK")
      (footprint "eagle-import:1X01_SMD_1.27X0.635MM_NO_SILK")
      (libsource (lib "eagle-import") (part "M01PTH_SMD_1.27X0.635MM_NO_SILK"))
    )
    (comp (ref "JP954")
      (value "M01PTH_SMD_1.27X0.635MM_NO_SILK")
      (footprint "eagle-import:1X01_SMD_1.27X0.635MM_NO_SILK")
      (libsource (lib "eagle-import") (part "M01PTH_SMD_1.27X0.635MM_NO_SILK"))
    )
    (comp (ref "JP955")
      (value "M01PTH_SMD_1.27X0.635MM_NO_SILK")
      (footprint "eagle-import:1X01_SMD_1.27X0.635MM_NO_SILK")
      (libsource (lib "eagle-import") (part "M01PTH_SMD_1.27X0.635MM_NO_SILK"))
    )
    (comp (ref "JP956")
      (value "M01PTH_SMD_1.27X0.635MM_NO_SILK")
      (footprint "eagle-import:1X01_SMD_1.27X0.635MM_NO_SILK")
      (libsource (lib "eagle-import") (part "M01PTH_SMD_1.27X0.635MM_NO_SILK"))
    )
    (comp (ref "JP957")
      (value "M01PTH_SMD_1.27X0.635MM_NO_SILK")
      (footprint "eagle-import:1X01_SMD_1.27X0.635MM_NO_SILK")
      (libsource (lib "eagle-import") (part "M01PTH_SMD_1.27X0.635MM_NO_SILK"))
    )
    (comp (ref "JP958")
      (value "M01PTH_SMD_1.27X0.635MM_NO_SILK")
      (footprint "eagle-import:1X01_SMD_1.27X0.635MM_NO_SILK")
      (libsource (lib "eagle-import") (part "M01PTH_SMD_1.27X0.635MM_NO_SILK"))
    )
    (comp (ref "JP959")
      (value "M01PTH_SMD_1.27X0.635MM_NO_SILK")
      (footprint "eagle-import:1X01_SMD_1.27X0.635MM_NO_SILK")
      (libsource (lib "eagle-import") (part "M01PTH_SMD_1.27X0.635MM_NO_SILK"))
    )
    (comp (ref "JP960")
      (value "M01PTH_SMD_1.27X0.635MM_NO_SILK")
      (footprint "eagle-import:1X01_SMD_1.27X0.635MM_NO_SILK")
      (libsource (lib "eagle-import") (part "M01PTH_SMD_1.27X0.635MM_NO_SILK"))
    )
    (comp (ref "JP961")
      (value "M01PTH_SMD_1.27X0.635MM_NO_SILK")
      (footprint "eagle-import:1X01_SMD_1.27X0.635MM_NO_SILK")
      (libsource (lib "eagle-import") (part "M01PTH_SMD_1.27X0.635MM_NO_SILK"))
    )
    (comp (ref "JP962")
      (value "M01PTH_SMD_1.27X0.635MM_NO_SILK")
      (footprint "eagle-import:1X01_SMD_1.27X0.635MM_NO_SILK")
      (libsource (lib "eagle-import") (part "M01PTH_SMD_1.27X0.635MM_NO_SILK"))
    )
    (comp (ref "JP963")
      (value "M01PTH_SMD_1.27X0.635MM_NO_SILK")
      (footprint "eagle-import:1X01_SMD_1.27X0.635MM_NO_SILK")
      (libsource (lib "eagle-import") (part "M01PTH_SMD_1.27X0.635MM_NO_SILK"))
    )
    (comp (ref "JP964")
      (value "M01PTH_SMD_1.27X0.635MM_NO_SILK")
      (footprint "eagle-import:1X01_SMD_1.27X0.635MM_NO_SILK")
      (libsource (lib "eagle-import") (part "M01PTH_SMD_1.27X0.635MM_NO_SILK"))
    )
    (comp (ref "JP965")
      (value "M01PTH_SMD_1.27X0.635MM_NO_SILK")
      (footprint "eagle-import:1X01_SMD_1.27X0.635MM_NO_SILK")
      (libsource (lib "eagle-import") (part "M01PTH_SMD_1.27X0.635MM_NO_SILK"))
    )
    (comp (ref "JP966")
      (value "M01PTH_SMD_1.27X0.635MM_NO_SILK")
      (footprint "eagle-import:1X01_SMD_1.27X0.635MM_NO_SILK")
      (libsource (lib "eagle-import") (part "M01PTH_SMD_1.27X0.635MM_NO_SILK"))
    )
    (comp (ref "JP967")
      (value "M01PTH_SMD_1.27X0.635MM_NO_SILK")
      (footprint "eagle-import:1X01_SMD_1.27X0.635MM_NO_SILK")
      (libsource (lib "eagle-import") (part "M01PTH_SMD_1.27X0.635MM_NO_SILK"))
    )
    (comp (ref "JP968")
      (value "M01PTH_SMD_1.27X0.635MM_NO_SILK")
      (footprint "eagle-import:1X01_SMD_1.27X0.635MM_NO_SILK")
      (libsource (lib "eagle-import") (part "M01PTH_SMD_1.27X0.635MM_NO_SILK"))
    )
    (comp (ref "JP969")
      (value "M01PTH_SMD_1.27X0.635MM_NO_SILK")
      (footprint "eagle-import:1X01_SMD_1.27X0.635MM_NO_SILK")
      (libsource (lib "eagle-import") (part "M01PTH_SMD_1.27X0.635MM_NO_SILK"))
    )
    (comp (ref "JP970")
      (value "M01PTH_SMD_1.27X0.635MM_NO_SILK")
      (footprint "eagle-import:1X01_SMD_1.27X0.635MM_NO_SILK")
      (libsource (lib "eagle-import") (part "M01PTH_SMD_1.27X0.635MM_NO_SILK"))
    )
    (comp (ref "JP971")
      (value "M01PTH_SMD_1.27X0.635MM_NO_SILK")
      (footprint "eagle-import:1X01_SMD_1.27X0.635MM_NO_SILK")
      (libsource (lib "eagle-import") (part "M01PTH_SMD_1.27X0.635MM_NO_SILK"))
    )
    (comp (ref "JP972")
      (value "M01PTH_SMD_1.27X0.635MM_NO_SILK")
      (footprint "eagle-import:1X01_SMD_1.27X0.635MM_NO_SILK")
      (libsource (lib "eagle-import") (part "M01PTH_SMD_1.27X0.635MM_NO_SILK"))
    )
    (comp (ref "JP973")
      (value "M01PTH_SMD_1.27X0.635MM_NO_SILK")
      (footprint "eagle-import:1X01_SMD_1.27X0.635MM_NO_SILK")
      (libsource (lib "eagle-import") (part "M01PTH_SMD_1.27X0.635MM_NO_SILK"))
    )
    (comp (ref "JP974")
      (value "M01PTH_SMD_1.27X0.635MM_NO_SILK")
      (footprint "eagle-import:1X01_SMD_1.27X0.635MM_NO_SILK")
      (libsource (lib "eagle-import") (part "M01PTH_SMD_1.27X0.635MM_NO_SILK"))
    )
    (comp (ref "JP975")
      (value "M01PTH_SMD_1.27X0.635MM_NO_SILK")
      (footprint "eagle-import:1X01_SMD_1.27X0.635MM_NO_SILK")
      (libsource (lib "eagle-import") (part "M01PTH_SMD_1.27X0.635MM_NO_SILK"))
    )
    (comp (ref "JP976")
      (value "M01PTH_SMD_1.27X0.635MM_NO_SILK")
      (footprint "eagle-import:1X01_SMD_1.27X0.635MM_NO_SILK")
      (libsource (lib "eagle-import") (part "M01PTH_SMD_1.27X0.635MM_NO_SILK"))
    )
    (comp (ref "JP977")
      (value "M01PTH_SMD_1.27X0.635MM_NO_SILK")
      (footprint "eagle-import:1X01_SMD_1.27X0.635MM_NO_SILK")
      (libsource (lib "eagle-import") (part "M01PTH_SMD_1.27X0.635MM_NO_SILK"))
    )
    (comp (ref "JP978")
      (value "M01PTH_SMD_1.27X0.635MM_NO_SILK")
      (footprint "eagle-import:1X01_SMD_1.27X0.635MM_NO_SILK")
      (libsource (lib "eagle-import") (part "M01PTH_SMD_1.27X0.635MM_NO_SILK"))
    )
    (comp (ref "JP979")
      (value "M01PTH_SMD_1.27X0.635MM_NO_SILK")
      (footprint "eagle-import:1X01_SMD_1.27X0.635MM_NO_SILK")
      (libsource (lib "eagle-import") (part "M01PTH_SMD_1.27X0.635MM_NO_SILK"))
    )
    (comp (ref "JP980")
      (value "M01PTH_SMD_1.27X0.635MM_NO_SILK")
      (footprint "eagle-import:1X01_SMD_1.27X0.635MM_NO_SILK")
      (libsource (lib "eagle-import") (part "M01PTH_SMD_1.27X0.635MM_NO_SILK"))
    )
    (comp (ref "JP981")
      (value "M01PTH_SMD_1.27X0.635MM_NO_SILK")
      (footprint "eagle-import:1X01_SMD_1.27X0.635MM_NO_SILK")
      (libsource (lib "eagle-import") (part "M01PTH_SMD_1.27X0.635MM_NO_SILK"))
    )
    (comp (ref "JP982")
      (value "M01PTH_SMD_1.27X0.635MM_NO_SILK")
      (footprint "eagle-import:1X01_SMD_1.27X0.635MM_NO_SILK")
      (libsource (lib "eagle-import") (part "M01PTH_SMD_1.27X0.635MM_NO_SILK"))
    )
    (comp (ref "JP983")
      (value "M01PTH_SMD_1.27X0.635MM_NO_SILK")
      (footprint "eagle-import:1X01_SMD_1.27X0.635MM_NO_SILK")
      (libsource (lib "eagle-import") (part "M01PTH_SMD_1.27X0.635MM_NO_SILK"))
    )
    (comp (ref "JP984")
      (value "M01PTH_SMD_1.27X0.635MM_NO_SILK")
      (footprint "eagle-import:1X01_SMD_1.27X0.635MM_NO_SILK")
      (libsource (lib "eagle-import") (part "M01PTH_SMD_1.27X0.635MM_NO_SILK"))
    )
    (comp (ref "JP985")
      (value "M01PTH_SMD_1.27X0.635MM_NO_SILK")
      (footprint "eagle-import:1X01_SMD_1.27X0.635MM_NO_SILK")
      (libsource (lib "eagle-import") (part "M01PTH_SMD_1.27X0.635MM_NO_SILK"))
    )
    (comp (ref "JP986")
      (value "M01PTH_SMD_1.27X0.635MM_NO_SILK")
      (footprint "eagle-import:1X01_SMD_1.27X0.635MM_NO_SILK")
      (libsource (lib "eagle-import") (part "M01PTH_SMD_1.27X0.635MM_NO_SILK"))
    )
    (comp (ref "JP987")
      (value "M01PTH_SMD_1.27X0.635MM_NO_SILK")
      (footprint "eagle-import:1X01_SMD_1.27X0.635MM_NO_SILK")
      (libsource (lib "eagle-import") (part "M01PTH_SMD_1.27X0.635MM_NO_SILK"))
    )
    (comp (ref "JP988")
      (value "M01PTH_SMD_1.27X0.635MM_NO_SILK")
      (footprint "eagle-import:1X01_SMD_1.27X0.635MM_NO_SILK")
      (libsource (lib "eagle-import") (part "M01PTH_SMD_1.27X0.635MM_NO_SILK"))
    )
    (comp (ref "JP989")
      (value "M01PTH_SMD_1.27X0.635MM_NO_SILK")
      (footprint "eagle-import:1X01_SMD_1.27X0.635MM_NO_SILK")
      (libsource (lib "eagle-import") (part "M01PTH_SMD_1.27X0.635MM_NO_SILK"))
    )
    (comp (ref "JP990")
      (value "M01PTH_SMD_1.27X0.635MM_NO_SILK")
      (footprint "eagle-import:1X01_SMD_1.27X0.635MM_NO_SILK")
      (libsource (lib "eagle-import") (part "M01PTH_SMD_1.27X0.635MM_NO_SILK"))
    )
    (comp (ref "JP991")
      (value "M01PTH_SMD_1.27X0.635MM_NO_SILK")
      (footprint "eagle-import:1X01_SMD_1.27X0.635MM_NO_SILK")
      (libsource (lib "eagle-import") (part "M01PTH_SMD_1.27X0.635MM_NO_SILK"))
    )
    (comp (ref "JP992")
      (value "M01PTH_SMD_1.27X0.635MM_NO_SILK")
      (footprint "eagle-import:1X01_SMD_1.27X0.635MM_NO_SILK")
      (libsource (lib "eagle-import") (part "M01PTH_SMD_1.27X0.635MM_NO_SILK"))
    )
    (comp (ref "JP993")
      (value "M01PTH_SMD_1.27X0.635MM_NO_SILK")
      (footprint "eagle-import:1X01_SMD_1.27X0.635MM_NO_SILK")
      (libsource (lib "eagle-import") (part "M01PTH_SMD_1.27X0.635MM_NO_SILK"))
    )
    (comp (ref "JP994")
      (value "M01PTH_SMD_1.27X0.635MM_NO_SILK")
      (footprint "eagle-import:1X01_SMD_1.27X0.635MM_NO_SILK")
      (libsource (lib "eagle-import") (part "M01PTH_SMD_1.27X0.635MM_NO_SILK"))
    )
    (comp (ref "JP995")
      (value "M01PTH_SMD_1.27X0.635MM_NO_SILK")
      (footprint "eagle-import:1X01_SMD_1.27X0.635MM_NO_SILK")
      (libsource (lib "eagle-import") (part "M01PTH_SMD_1.27X0.635MM_NO_SILK"))
    )
    (comp (ref "JP996")
      (value "M01PTH_SMD_1.27X0.635MM_NO_SILK")
      (footprint "eagle-import:1X01_SMD_1.27X0.635MM_NO_SILK")
      (libsource (lib "eagle-import") (part "M01PTH_SMD_1.27X0.635MM_NO_SILK"))
    )
    (comp (ref "JP997")
      (value "M01PTH_SMD_1.27X0.635MM_NO_SILK")
      (footprint "eagle-import:1X01_SMD_1.27X0.635MM_NO_SILK")
      (libsource (lib "eagle-import") (part "M01PTH_SMD_1.27X0.635MM_NO_SILK"))
    )
    (comp (ref "JP998")
      (value "M01PTH_SMD_1.27X0.635MM_NO_SILK")
      (footprint "eagle-import:1X01_SMD_1.27X0.635MM_NO_SILK")
      (libsource (lib "eagle-import") (part "M01PTH_SMD_1.27X0.635MM_NO_SILK"))
    )
    (comp (ref "JP999")
      (value "M01PTH_SMD_1.27X0.635MM_NO_SILK")
      (footprint "eagle-import:1X01_SMD_1.27X0.635MM_NO_SILK")
      (libsource (lib "eagle-import") (part "M01PTH_SMD_1.27X0.635MM_NO_SILK"))
    )
    (comp (ref "JP1000")
      (value "M01PTH_SMD_1.27X0.635MM_NO_SILK")
      (footprint "eagle-import:1X01_SMD_1.27X0.635MM_NO_SILK")
      (libsource (lib "eagle-import") (part "M01PTH_SMD_1.27X0.635MM_NO_SILK"))
    )
    (comp (ref "JP1001")
      (value "M01PTH_SMD_1.27X0.635MM_NO_SILK")
      (footprint "eagle-import:1X01_SMD_1.27X0.635MM_NO_SILK")
      (libsource (lib "eagle-import") (part "M01PTH_SMD_1.27X0.635MM_NO_SILK"))
    )
    (comp (ref "JP1002")
      (value "M01PTH_SMD_1.27X0.635MM_NO_SILK")
      (footprint "eagle-import:1X01_SMD_1.27X0.635MM_NO_SILK")
      (libsource (lib "eagle-import") (part "M01PTH_SMD_1.27X0.635MM_NO_SILK"))
    )
    (comp (ref "JP1003")
      (value "M01PTH_SMD_1.27X0.635MM_NO_SILK")
      (footprint "eagle-import:1X01_SMD_1.27X0.635MM_NO_SILK")
      (libsource (lib "eagle-import") (part "M01PTH_SMD_1.27X0.635MM_NO_SILK"))
    )
    (comp (ref "JP1004")
      (value "M01PTH_SMD_1.27X0.635MM_NO_SILK")
      (footprint "eagle-import:1X01_SMD_1.27X0.635MM_NO_SILK")
      (libsource (lib "eagle-import") (part "M01PTH_SMD_1.27X0.635MM_NO_SILK"))
    )
    (comp (ref "JP1005")
      (value "M01PTH_SMD_1.27X0.635MM_NO_SILK")
      (footprint "eagle-import:1X01_SMD_1.27X0.635MM_NO_SILK")
      (libsource (lib "eagle-import") (part "M01PTH_SMD_1.27X0.635MM_NO_SILK"))
    )
    (comp (ref "JP1006")
      (value "M01PTH_SMD_1.27X0.635MM_NO_SILK")
      (footprint "eagle-import:1X01_SMD_1.27X0.635MM_NO_SILK")
      (libsource (lib "eagle-import") (part "M01PTH_SMD_1.27X0.635MM_NO_SILK"))
    )
    (comp (ref "JP1007")
      (value "M01PTH_SMD_1.27X0.635MM_NO_SILK")
      (footprint "eagle-import:1X01_SMD_1.27X0.635MM_NO_SILK")
      (libsource (lib "eagle-import") (part "M01PTH_SMD_1.27X0.635MM_NO_SILK"))
    )
    (comp (ref "JP1008")
      (value "M01PTH_SMD_1.27X0.635MM_NO_SILK")
      (footprint "eagle-import:1X01_SMD_1.27X0.635MM_NO_SILK")
      (libsource (lib "eagle-import") (part "M01PTH_SMD_1.27X0.635MM_NO_SILK"))
    )
    (comp (ref "JP1009")
      (value "M01PTH_SMD_1.27X0.635MM_NO_SILK")
      (footprint "eagle-import:1X01_SMD_1.27X0.635MM_NO_SILK")
      (libsource (lib "eagle-import") (part "M01PTH_SMD_1.27X0.635MM_NO_SILK"))
    )
    (comp (ref "JP1010")
      (value "M01PTH_SMD_1.27X0.635MM_NO_SILK")
      (footprint "eagle-import:1X01_SMD_1.27X0.635MM_NO_SILK")
      (libsource (lib "eagle-import") (part "M01PTH_SMD_1.27X0.635MM_NO_SILK"))
    )
    (comp (ref "JP1011")
      (value "M01PTH_SMD_1.27X0.635MM_NO_SILK")
      (footprint "eagle-import:1X01_SMD_1.27X0.635MM_NO_SILK")
      (libsource (lib "eagle-import") (part "M01PTH_SMD_1.27X0.635MM_NO_SILK"))
    )
    (comp (ref "JP1012")
      (value "M01PTH_SMD_1.27X0.635MM_NO_SILK")
      (footprint "eagle-import:1X01_SMD_1.27X0.635MM_NO_SILK")
      (libsource (lib "eagle-import") (part "M01PTH_SMD_1.27X0.635MM_NO_SILK"))
    )
    (comp (ref "JP1013")
      (value "M01PTH_SMD_1.27X0.635MM_NO_SILK")
      (footprint "eagle-import:1X01_SMD_1.27X0.635MM_NO_SILK")
      (libsource (lib "eagle-import") (part "M01PTH_SMD_1.27X0.635MM_NO_SILK"))
    )
    (comp (ref "JP1014")
      (value "M01PTH_SMD_1.27X0.635MM_NO_SILK")
      (footprint "eagle-import:1X01_SMD_1.27X0.635MM_NO_SILK")
      (libsource (lib "eagle-import") (part "M01PTH_SMD_1.27X0.635MM_NO_SILK"))
    )
    (comp (ref "JP1015")
      (value "M01PTH_SMD_1.27X0.635MM_NO_SILK")
      (footprint "eagle-import:1X01_SMD_1.27X0.635MM_NO_SILK")
      (libsource (lib "eagle-import") (part "M01PTH_SMD_1.27X0.635MM_NO_SILK"))
    )
    (comp (ref "JP1016")
      (value "M01PTH_SMD_1.27X0.635MM_NO_SILK")
      (footprint "eagle-import:1X01_SMD_1.27X0.635MM_NO_SILK")
      (libsource (lib "eagle-import") (part "M01PTH_SMD_1.27X0.635MM_NO_SILK"))
    )
    (comp (ref "JP1017")
      (value "M01PTH_SMD_1.27X0.635MM_NO_SILK")
      (footprint "eagle-import:1X01_SMD_1.27X0.635MM_NO_SILK")
      (libsource (lib "eagle-import") (part "M01PTH_SMD_1.27X0.635MM_NO_SILK"))
    )
    (comp (ref "JP1018")
      (value "M01PTH_SMD_1.27X0.635MM_NO_SILK")
      (footprint "eagle-import:1X01_SMD_1.27X0.635MM_NO_SILK")
      (libsource (lib "eagle-import") (part "M01PTH_SMD_1.27X0.635MM_NO_SILK"))
    )
    (comp (ref "JP1019")
      (value "M01PTH_SMD_1.27X0.635MM_NO_SILK")
      (footprint "eagle-import:1X01_SMD_1.27X0.635MM_NO_SILK")
      (libsource (lib "eagle-import") (part "M01PTH_SMD_1.27X0.635MM_NO_SILK"))
    )
    (comp (ref "JP1020")
      (value "M01PTH_SMD_1.27X0.635MM_NO_SILK")
      (footprint "eagle-import:1X01_SMD_1.27X0.635MM_NO_SILK")
      (libsource (lib "eagle-import") (part "M01PTH_SMD_1.27X0.635MM_NO_SILK"))
    )
    (comp (ref "JP1021")
      (value "M01PTH_SMD_1.27X0.635MM_NO_SILK")
      (footprint "eagle-import:1X01_SMD_1.27X0.635MM_NO_SILK")
      (libsource (lib "eagle-import") (part "M01PTH_SMD_1.27X0.635MM_NO_SILK"))
    )
    (comp (ref "JP1022")
      (value "M01PTH_SMD_1.27X0.635MM_NO_SILK")
      (footprint "eagle-import:1X01_SMD_1.27X0.635MM_NO_SILK")
      (libsource (lib "eagle-import") (part "M01PTH_SMD_1.27X0.635MM_NO_SILK"))
    )
    (comp (ref "JP1023")
      (value "M01PTH_SMD_1.27X0.635MM_NO_SILK")
      (footprint "eagle-import:1X01_SMD_1.27X0.635MM_NO_SILK")
      (libsource (lib "eagle-import") (part "M01PTH_SMD_1.27X0.635MM_NO_SILK"))
    )
    (comp (ref "JP1024")
      (value "M01PTH_SMD_1.27X0.635MM_NO_SILK")
      (footprint "eagle-import:1X01_SMD_1.27X0.635MM_NO_SILK")
      (libsource (lib "eagle-import") (part "M01PTH_SMD_1.27X0.635MM_NO_SILK"))
    )
    (comp (ref "JP1025")
      (value "M01PTH_SMD_1.27X0.635MM_NO_SILK")
      (footprint "eagle-import:1X01_SMD_1.27X0.635MM_NO_SILK")
      (libsource (lib "eagle-import") (part "M01PTH_SMD_1.27X0.635MM_NO_SILK"))
    )
    (comp (ref "JP1026")
      (value "M01PTH_SMD_1.27X0.635MM_NO_SILK")
      (footprint "eagle-import:1X01_SMD_1.27X0.635MM_NO_SILK")
      (libsource (lib "eagle-import") (part "M01PTH_SMD_1.27X0.635MM_NO_SILK"))
    )
    (comp (ref "JP1027")
      (value "M01PTH_SMD_1.27X0.635MM_NO_SILK")
      (footprint "eagle-import:1X01_SMD_1.27X0.635MM_NO_SILK")
      (libsource (lib "eagle-import") (part "M01PTH_SMD_1.27X0.635MM_NO_SILK"))
    )
    (comp (ref "JP1028")
      (value "M01PTH_SMD_1.27X0.635MM_NO_SILK")
      (footprint "eagle-import:1X01_SMD_1.27X0.635MM_NO_SILK")
      (libsource (lib "eagle-import") (part "M01PTH_SMD_1.27X0.635MM_NO_SILK"))
    )
    (comp (ref "JP1029")
      (value "M01PTH_SMD_1.27X0.635MM_NO_SILK")
      (footprint "eagle-import:1X01_SMD_1.27X0.635MM_NO_SILK")
      (libsource (lib "eagle-import") (part "M01PTH_SMD_1.27X0.635MM_NO_SILK"))
    )
    (comp (ref "JP1030")
      (value "M01PTH_SMD_1.27X0.635MM_NO_SILK")
      (footprint "eagle-import:1X01_SMD_1.27X0.635MM_NO_SILK")
      (libsource (lib "eagle-import") (part "M01PTH_SMD_1.27X0.635MM_NO_SILK"))
    )
    (comp (ref "JP1031")
      (value "M01PTH_SMD_1.27X0.635MM_NO_SILK")
      (footprint "eagle-import:1X01_SMD_1.27X0.635MM_NO_SILK")
      (libsource (lib "eagle-import") (part "M01PTH_SMD_1.27X0.635MM_NO_SILK"))
    )
    (comp (ref "JP1032")
      (value "M01PTH_SMD_1.27X0.635MM_NO_SILK")
      (footprint "eagle-import:1X01_SMD_1.27X0.635MM_NO_SILK")
      (libsource (lib "eagle-import") (part "M01PTH_SMD_1.27X0.635MM_NO_SILK"))
    )
    (comp (ref "JP1033")
      (value "M01PTH_SMD_1.27X0.635MM_NO_SILK")
      (footprint "eagle-import:1X01_SMD_1.27X0.635MM_NO_SILK")
      (libsource (lib "eagle-import") (part "M01PTH_SMD_1.27X0.635MM_NO_SILK"))
    )
    (comp (ref "JP1034")
      (value "M01PTH_SMD_1.27X0.635MM_NO_SILK")
      (footprint "eagle-import:1X01_SMD_1.27X0.635MM_NO_SILK")
      (libsource (lib "eagle-import") (part "M01PTH_SMD_1.27X0.635MM_NO_SILK"))
    )
    (comp (ref "JP1035")
      (value "M01PTH_SMD_1.27X0.635MM_NO_SILK")
      (footprint "eagle-import:1X01_SMD_1.27X0.635MM_NO_SILK")
      (libsource (lib "eagle-import") (part "M01PTH_SMD_1.27X0.635MM_NO_SILK"))
    )
    (comp (ref "JP1036")
      (value "M01PTH_SMD_1.27X0.635MM_NO_SILK")
      (footprint "eagle-import:1X01_SMD_1.27X0.635MM_NO_SILK")
      (libsource (lib "eagle-import") (part "M01PTH_SMD_1.27X0.635MM_NO_SILK"))
    )
    (comp (ref "JP1037")
      (value "M01PTH_SMD_1.27X0.635MM_NO_SILK")
      (footprint "eagle-import:1X01_SMD_1.27X0.635MM_NO_SILK")
      (libsource (lib "eagle-import") (part "M01PTH_SMD_1.27X0.635MM_NO_SILK"))
    )
    (comp (ref "JP1038")
      (value "M01PTH_SMD_1.27X0.635MM_NO_SILK")
      (footprint "eagle-import:1X01_SMD_1.27X0.635MM_NO_SILK")
      (libsource (lib "eagle-import") (part "M01PTH_SMD_1.27X0.635MM_NO_SILK"))
    )
    (comp (ref "JP1039")
      (value "M01PTH_SMD_1.27X0.635MM_NO_SILK")
      (footprint "eagle-import:1X01_SMD_1.27X0.635MM_NO_SILK")
      (libsource (lib "eagle-import") (part "M01PTH_SMD_1.27X0.635MM_NO_SILK"))
    )
    (comp (ref "JP1040")
      (value "M01PTH_SMD_1.27X0.635MM_NO_SILK")
      (footprint "eagle-import:1X01_SMD_1.27X0.635MM_NO_SILK")
      (libsource (lib "eagle-import") (part "M01PTH_SMD_1.27X0.635MM_NO_SILK"))
    )
    (comp (ref "JP1041")
      (value "M01PTH_SMD_1.27X0.635MM_NO_SILK")
      (footprint "eagle-import:1X01_SMD_1.27X0.635MM_NO_SILK")
      (libsource (lib "eagle-import") (part "M01PTH_SMD_1.27X0.635MM_NO_SILK"))
    )
    (comp (ref "JP1042")
      (value "M01PTH_SMD_1.27X0.635MM_NO_SILK")
      (footprint "eagle-import:1X01_SMD_1.27X0.635MM_NO_SILK")
      (libsource (lib "eagle-import") (part "M01PTH_SMD_1.27X0.635MM_NO_SILK"))
    )
    (comp (ref "JP1043")
      (value "M01PTH_SMD_1.27X0.635MM_NO_SILK")
      (footprint "eagle-import:1X01_SMD_1.27X0.635MM_NO_SILK")
      (libsource (lib "eagle-import") (part "M01PTH_SMD_1.27X0.635MM_NO_SILK"))
    )
    (comp (ref "JP1044")
      (value "M01PTH_SMD_1.27X0.635MM_NO_SILK")
      (footprint "eagle-import:1X01_SMD_1.27X0.635MM_NO_SILK")
      (libsource (lib "eagle-import") (part "M01PTH_SMD_1.27X0.635MM_NO_SILK"))
    )
    (comp (ref "JP1045")
      (value "M01PTH_SMD_1.27X0.635MM_NO_SILK")
      (footprint "eagle-import:1X01_SMD_1.27X0.635MM_NO_SILK")
      (libsource (lib "eagle-import") (part "M01PTH_SMD_1.27X0.635MM_NO_SILK"))
    )
    (comp (ref "JP1046")
      (value "M01PTH_SMD_1.27X0.635MM_NO_SILK")
      (footprint "eagle-import:1X01_SMD_1.27X0.635MM_NO_SILK")
      (libsource (lib "eagle-import") (part "M01PTH_SMD_1.27X0.635MM_NO_SILK"))
    )
    (comp (ref "JP1047")
      (value "M01PTH_SMD_1.27X0.635MM_NO_SILK")
      (footprint "eagle-import:1X01_SMD_1.27X0.635MM_NO_SILK")
      (libsource (lib "eagle-import") (part "M01PTH_SMD_1.27X0.635MM_NO_SILK"))
    )
    (comp (ref "JP1048")
      (value "M01PTH_SMD_1.27X0.635MM_NO_SILK")
      (footprint "eagle-import:1X01_SMD_1.27X0.635MM_NO_SILK")
      (libsource (lib "eagle-import") (part "M01PTH_SMD_1.27X0.635MM_NO_SILK"))
    )
    (comp (ref "JP1049")
      (value "M01PTH_SMD_1.27X0.635MM_NO_SILK")
      (footprint "eagle-import:1X01_SMD_1.27X0.635MM_NO_SILK")
      (libsource (lib "eagle-import") (part "M01PTH_SMD_1.27X0.635MM_NO_SILK"))
    )
    (comp (ref "JP1050")
      (value "M01PTH_SMD_1.27X0.635MM_NO_SILK")
      (footprint "eagle-import:1X01_SMD_1.27X0.635MM_NO_SILK")
      (libsource (lib "eagle-import") (part "M01PTH_SMD_1.27X0.635MM_NO_SILK"))
    )
    (comp (ref "JP1051")
      (value "M01PTH_SMD_1.27X0.635MM_NO_SILK")
      (footprint "eagle-import:1X01_SMD_1.27X0.635MM_NO_SILK")
      (libsource (lib "eagle-import") (part "M01PTH_SMD_1.27X0.635MM_NO_SILK"))
    )
    (comp (ref "JP1052")
      (value "M01PTH_SMD_1.27X0.635MM_NO_SILK")
      (footprint "eagle-import:1X01_SMD_1.27X0.635MM_NO_SILK")
      (libsource (lib "eagle-import") (part "M01PTH_SMD_1.27X0.635MM_NO_SILK"))
    )
    (comp (ref "JP1053")
      (value "M01PTH_SMD_1.27X0.635MM_NO_SILK")
      (footprint "eagle-import:1X01_SMD_1.27X0.635MM_NO_SILK")
      (libsource (lib "eagle-import") (part "M01PTH_SMD_1.27X0.635MM_NO_SILK"))
    )
    (comp (ref "JP1054")
      (value "M01PTH_SMD_1.27X0.635MM_NO_SILK")
      (footprint "eagle-import:1X01_SMD_1.27X0.635MM_NO_SILK")
      (libsource (lib "eagle-import") (part "M01PTH_SMD_1.27X0.635MM_NO_SILK"))
    )
    (comp (ref "JP1055")
      (value "M01PTH_SMD_1.27X0.635MM_NO_SILK")
      (footprint "eagle-import:1X01_SMD_1.27X0.635MM_NO_SILK")
      (libsource (lib "eagle-import") (part "M01PTH_SMD_1.27X0.635MM_NO_SILK"))
    )
    (comp (ref "JP1056")
      (value "M01PTH_SMD_1.27X0.635MM_NO_SILK")
      (footprint "eagle-import:1X01_SMD_1.27X0.635MM_NO_SILK")
      (libsource (lib "eagle-import") (part "M01PTH_SMD_1.27X0.635MM_NO_SILK"))
    )
    (comp (ref "JP1057")
      (value "M01PTH_SMD_1.27X0.635MM_NO_SILK")
      (footprint "eagle-import:1X01_SMD_1.27X0.635MM_NO_SILK")
      (libsource (lib "eagle-import") (part "M01PTH_SMD_1.27X0.635MM_NO_SILK"))
    )
    (comp (ref "JP1058")
      (value "M01PTH_SMD_1.27X0.635MM_NO_SILK")
      (footprint "eagle-import:1X01_SMD_1.27X0.635MM_NO_SILK")
      (libsource (lib "eagle-import") (part "M01PTH_SMD_1.27X0.635MM_NO_SILK"))
    )
    (comp (ref "JP1059")
      (value "M01PTH_SMD_1.27X0.635MM_NO_SILK")
      (footprint "eagle-import:1X01_SMD_1.27X0.635MM_NO_SILK")
      (libsource (lib "eagle-import") (part "M01PTH_SMD_1.27X0.635MM_NO_SILK"))
    )
    (comp (ref "JP1060")
      (value "M01PTH_SMD_1.27X0.635MM_NO_SILK")
      (footprint "eagle-import:1X01_SMD_1.27X0.635MM_NO_SILK")
      (libsource (lib "eagle-import") (part "M01PTH_SMD_1.27X0.635MM_NO_SILK"))
    )
    (comp (ref "JP1061")
      (value "M01PTH_SMD_1.27X0.635MM_NO_SILK")
      (footprint "eagle-import:1X01_SMD_1.27X0.635MM_NO_SILK")
      (libsource (lib "eagle-import") (part "M01PTH_SMD_1.27X0.635MM_NO_SILK"))
    )
    (comp (ref "JP1062")
      (value "M01PTH_SMD_1.27X0.635MM_NO_SILK")
      (footprint "eagle-import:1X01_SMD_1.27X0.635MM_NO_SILK")
      (libsource (lib "eagle-import") (part "M01PTH_SMD_1.27X0.635MM_NO_SILK"))
    )
    (comp (ref "JP1063")
      (value "M01PTH_SMD_1.27X0.635MM_NO_SILK")
      (footprint "eagle-import:1X01_SMD_1.27X0.635MM_NO_SILK")
      (libsource (lib "eagle-import") (part "M01PTH_SMD_1.27X0.635MM_NO_SILK"))
    )
    (comp (ref "JP1064")
      (value "M01PTH_SMD_1.27X0.635MM_NO_SILK")
      (footprint "eagle-import:1X01_SMD_1.27X0.635MM_NO_SILK")
      (libsource (lib "eagle-import") (part "M01PTH_SMD_1.27X0.635MM_NO_SILK"))
    )
    (comp (ref "JP1065")
      (value "M01PTH_SMD_1.27X0.635MM_NO_SILK")
      (footprint "eagle-import:1X01_SMD_1.27X0.635MM_NO_SILK")
      (libsource (lib "eagle-import") (part "M01PTH_SMD_1.27X0.635MM_NO_SILK"))
    )
    (comp (ref "JP1066")
      (value "M01PTH_SMD_1.27X0.635MM_NO_SILK")
      (footprint "eagle-import:1X01_SMD_1.27X0.635MM_NO_SILK")
      (libsource (lib "eagle-import") (part "M01PTH_SMD_1.27X0.635MM_NO_SILK"))
    )
    (comp (ref "JP1067")
      (value "M01PTH_SMD_1.27X0.635MM_NO_SILK")
      (footprint "eagle-import:1X01_SMD_1.27X0.635MM_NO_SILK")
      (libsource (lib "eagle-import") (part "M01PTH_SMD_1.27X0.635MM_NO_SILK"))
    )
    (comp (ref "JP1068")
      (value "M01PTH_SMD_1.27X0.635MM_NO_SILK")
      (footprint "eagle-import:1X01_SMD_1.27X0.635MM_NO_SILK")
      (libsource (lib "eagle-import") (part "M01PTH_SMD_1.27X0.635MM_NO_SILK"))
    )
    (comp (ref "JP1069")
      (value "M01PTH_SMD_1.27X0.635MM_NO_SILK")
      (footprint "eagle-import:1X01_SMD_1.27X0.635MM_NO_SILK")
      (libsource (lib "eagle-import") (part "M01PTH_SMD_1.27X0.635MM_NO_SILK"))
    )
    (comp (ref "JP1070")
      (value "M01PTH_SMD_1.27X0.635MM_NO_SILK")
      (footprint "eagle-import:1X01_SMD_1.27X0.635MM_NO_SILK")
      (libsource (lib "eagle-import") (part "M01PTH_SMD_1.27X0.635MM_NO_SILK"))
    )
    (comp (ref "JP1071")
      (value "M01PTH_SMD_1.27X0.635MM_NO_SILK")
      (footprint "eagle-import:1X01_SMD_1.27X0.635MM_NO_SILK")
      (libsource (lib "eagle-import") (part "M01PTH_SMD_1.27X0.635MM_NO_SILK"))
    )
    (comp (ref "JP1072")
      (value "M01PTH_SMD_1.27X0.635MM_NO_SILK")
      (footprint "eagle-import:1X01_SMD_1.27X0.635MM_NO_SILK")
      (libsource (lib "eagle-import") (part "M01PTH_SMD_1.27X0.635MM_NO_SILK"))
    )
    (comp (ref "JP1073")
      (value "M01PTH_SMD_1.27X0.635MM_NO_SILK")
      (footprint "eagle-import:1X01_SMD_1.27X0.635MM_NO_SILK")
      (libsource (lib "eagle-import") (part "M01PTH_SMD_1.27X0.635MM_NO_SILK"))
    )
    (comp (ref "JP1074")
      (value "M01PTH_SMD_1.27X0.635MM_NO_SILK")
      (footprint "eagle-import:1X01_SMD_1.27X0.635MM_NO_SILK")
      (libsource (lib "eagle-import") (part "M01PTH_SMD_1.27X0.635MM_NO_SILK"))
    )
    (comp (ref "JP1075")
      (value "M01PTH_SMD_1.27X0.635MM_NO_SILK")
      (footprint "eagle-import:1X01_SMD_1.27X0.635MM_NO_SILK")
      (libsource (lib "eagle-import") (part "M01PTH_SMD_1.27X0.635MM_NO_SILK"))
    )
    (comp (ref "JP1076")
      (value "M01PTH_SMD_1.27X0.635MM_NO_SILK")
      (footprint "eagle-import:1X01_SMD_1.27X0.635MM_NO_SILK")
      (libsource (lib "eagle-import") (part "M01PTH_SMD_1.27X0.635MM_NO_SILK"))
    )
    (comp (ref "JP1077")
      (value "M01PTH_SMD_1.27X0.635MM_NO_SILK")
      (footprint "eagle-import:1X01_SMD_1.27X0.635MM_NO_SILK")
      (libsource (lib "eagle-import") (part "M01PTH_SMD_1.27X0.635MM_NO_SILK"))
    )
    (comp (ref "JP1078")
      (value "M01PTH_SMD_1.27X0.635MM_NO_SILK")
      (footprint "eagle-import:1X01_SMD_1.27X0.635MM_NO_SILK")
      (libsource (lib "eagle-import") (part "M01PTH_SMD_1.27X0.635MM_NO_SILK"))
    )
    (comp (ref "JP1079")
      (value "M01PTH_SMD_1.27X0.635MM_NO_SILK")
      (footprint "eagle-import:1X01_SMD_1.27X0.635MM_NO_SILK")
      (libsource (lib "eagle-import") (part "M01PTH_SMD_1.27X0.635MM_NO_SILK"))
    )
    (comp (ref "JP1080")
      (value "M01PTH_SMD_1.27X0.635MM_NO_SILK")
      (footprint "eagle-import:1X01_SMD_1.27X0.635MM_NO_SILK")
      (libsource (lib "eagle-import") (part "M01PTH_SMD_1.27X0.635MM_NO_SILK"))
    )
    (comp (ref "JP1081")
      (value "M01PTH_SMD_1.27X0.635MM_NO_SILK")
      (footprint "eagle-import:1X01_SMD_1.27X0.635MM_NO_SILK")
      (libsource (lib "eagle-import") (part "M01PTH_SMD_1.27X0.635MM_NO_SILK"))
    )
    (comp (ref "JP1082")
      (value "M01PTH_SMD_1.27X0.635MM_NO_SILK")
      (footprint "eagle-import:1X01_SMD_1.27X0.635MM_NO_SILK")
      (libsource (lib "eagle-import") (part "M01PTH_SMD_1.27X0.635MM_NO_SILK"))
    )
    (comp (ref "JP1083")
      (value "M01PTH_SMD_1.27X0.635MM_NO_SILK")
      (footprint "eagle-import:1X01_SMD_1.27X0.635MM_NO_SILK")
      (libsource (lib "eagle-import") (part "M01PTH_SMD_1.27X0.635MM_NO_SILK"))
    )
    (comp (ref "JP1084")
      (value "M01PTH_SMD_1.27X0.635MM_NO_SILK")
      (footprint "eagle-import:1X01_SMD_1.27X0.635MM_NO_SILK")
      (libsource (lib "eagle-import") (part "M01PTH_SMD_1.27X0.635MM_NO_SILK"))
    )
    (comp (ref "JP1085")
      (value "M01PTH_SMD_1.27X0.635MM_NO_SILK")
      (footprint "eagle-import:1X01_SMD_1.27X0.635MM_NO_SILK")
      (libsource (lib "eagle-import") (part "M01PTH_SMD_1.27X0.635MM_NO_SILK"))
    )
    (comp (ref "JP1086")
      (value "M01PTH_SMD_1.27X0.635MM_NO_SILK")
      (footprint "eagle-import:1X01_SMD_1.27X0.635MM_NO_SILK")
      (libsource (lib "eagle-import") (part "M01PTH_SMD_1.27X0.635MM_NO_SILK"))
    )
    (comp (ref "JP1087")
      (value "M01PTH_SMD_1.27X0.635MM_NO_SILK")
      (footprint "eagle-import:1X01_SMD_1.27X0.635MM_NO_SILK")
      (libsource (lib "eagle-import") (part "M01PTH_SMD_1.27X0.635MM_NO_SILK"))
    )
    (comp (ref "JP1088")
      (value "M01PTH_SMD_1.27X0.635MM_NO_SILK")
      (footprint "eagle-import:1X01_SMD_1.27X0.635MM_NO_SILK")
      (libsource (lib "eagle-import") (part "M01PTH_SMD_1.27X0.635MM_NO_SILK"))
    )
    (comp (ref "JP1089")
      (value "M01PTH_SMD_1.27X0.635MM_NO_SILK")
      (footprint "eagle-import:1X01_SMD_1.27X0.635MM_NO_SILK")
      (libsource (lib "eagle-import") (part "M01PTH_SMD_1.27X0.635MM_NO_SILK"))
    )
    (comp (ref "JP1090")
      (value "M01PTH_SMD_1.27X0.635MM_NO_SILK")
      (footprint "eagle-import:1X01_SMD_1.27X0.635MM_NO_SILK")
      (libsource (lib "eagle-import") (part "M01PTH_SMD_1.27X0.635MM_NO_SILK"))
    )
    (comp (ref "JP1091")
      (value "M01PTH_SMD_1.27X0.635MM_NO_SILK")
      (footprint "eagle-import:1X01_SMD_1.27X0.635MM_NO_SILK")
      (libsource (lib "eagle-import") (part "M01PTH_SMD_1.27X0.635MM_NO_SILK"))
    )
    (comp (ref "JP1092")
      (value "M01PTH_SMD_1.27X0.635MM_NO_SILK")
      (footprint "eagle-import:1X01_SMD_1.27X0.635MM_NO_SILK")
      (libsource (lib "eagle-import") (part "M01PTH_SMD_1.27X0.635MM_NO_SILK"))
    )
    (comp (ref "JP1093")
      (value "M01PTH_SMD_1.27X0.635MM_NO_SILK")
      (footprint "eagle-import:1X01_SMD_1.27X0.635MM_NO_SILK")
      (libsource (lib "eagle-import") (part "M01PTH_SMD_1.27X0.635MM_NO_SILK"))
    )
    (comp (ref "JP1094")
      (value "M01PTH_SMD_1.27X0.635MM_NO_SILK")
      (footprint "eagle-import:1X01_SMD_1.27X0.635MM_NO_SILK")
      (libsource (lib "eagle-import") (part "M01PTH_SMD_1.27X0.635MM_NO_SILK"))
    )
    (comp (ref "JP1095")
      (value "M01PTH_SMD_1.27X0.635MM_NO_SILK")
      (footprint "eagle-import:1X01_SMD_1.27X0.635MM_NO_SILK")
      (libsource (lib "eagle-import") (part "M01PTH_SMD_1.27X0.635MM_NO_SILK"))
    )
    (comp (ref "JP1096")
      (value "M01PTH_SMD_1.27X0.635MM_NO_SILK")
      (footprint "eagle-import:1X01_SMD_1.27X0.635MM_NO_SILK")
      (libsource (lib "eagle-import") (part "M01PTH_SMD_1.27X0.635MM_NO_SILK"))
    )
    (comp (ref "JP1097")
      (value "M01PTH_SMD_1.27X0.635MM_NO_SILK")
      (footprint "eagle-import:1X01_SMD_1.27X0.635MM_NO_SILK")
      (libsource (lib "eagle-import") (part "M01PTH_SMD_1.27X0.635MM_NO_SILK"))
    )
    (comp (ref "JP1098")
      (value "M01PTH_SMD_1.27X0.635MM_NO_SILK")
      (footprint "eagle-import:1X01_SMD_1.27X0.635MM_NO_SILK")
      (libsource (lib "eagle-import") (part "M01PTH_SMD_1.27X0.635MM_NO_SILK"))
    )
    (comp (ref "JP1099")
      (value "M01PTH_SMD_1.27X0.635MM_NO_SILK")
      (footprint "eagle-import:1X01_SMD_1.27X0.635MM_NO_SILK")
      (libsource (lib "eagle-import") (part "M01PTH_SMD_1.27X0.635MM_NO_SILK"))
    )
    (comp (ref "JP1100")
      (value "M01PTH_SMD_1.27X0.635MM_NO_SILK")
      (footprint "eagle-import:1X01_SMD_1.27X0.635MM_NO_SILK")
      (libsource (lib "eagle-import") (part "M01PTH_SMD_1.27X0.635MM_NO_SILK"))
    )
    (comp (ref "JP1101")
      (value "M01PTH_SMD_1.27X0.635MM_NO_SILK")
      (footprint "eagle-import:1X01_SMD_1.27X0.635MM_NO_SILK")
      (libsource (lib "eagle-import") (part "M01PTH_SMD_1.27X0.635MM_NO_SILK"))
    )
    (comp (ref "JP1102")
      (value "M01PTH_SMD_1.27X0.635MM_NO_SILK")
      (footprint "eagle-import:1X01_SMD_1.27X0.635MM_NO_SILK")
      (libsource (lib "eagle-import") (part "M01PTH_SMD_1.27X0.635MM_NO_SILK"))
    )
    (comp (ref "JP1103")
      (value "M01PTH_SMD_1.27X0.635MM_NO_SILK")
      (footprint "eagle-import:1X01_SMD_1.27X0.635MM_NO_SILK")
      (libsource (lib "eagle-import") (part "M01PTH_SMD_1.27X0.635MM_NO_SILK"))
    )
    (comp (ref "JP1104")
      (value "M01PTH_SMD_1.27X0.635MM_NO_SILK")
      (footprint "eagle-import:1X01_SMD_1.27X0.635MM_NO_SILK")
      (libsource (lib "eagle-import") (part "M01PTH_SMD_1.27X0.635MM_NO_SILK"))
    )
    (comp (ref "JP1105")
      (value "M01PTH_SMD_1.27X0.635MM_NO_SILK")
      (footprint "eagle-import:1X01_SMD_1.27X0.635MM_NO_SILK")
      (libsource (lib "eagle-import") (part "M01PTH_SMD_1.27X0.635MM_NO_SILK"))
    )
    (comp (ref "JP1106")
      (value "M01PTH_SMD_1.27X0.635MM_NO_SILK")
      (footprint "eagle-import:1X01_SMD_1.27X0.635MM_NO_SILK")
      (libsource (lib "eagle-import") (part "M01PTH_SMD_1.27X0.635MM_NO_SILK"))
    )
    (comp (ref "JP1107")
      (value "M01PTH_SMD_1.27X0.635MM_NO_SILK")
      (footprint "eagle-import:1X01_SMD_1.27X0.635MM_NO_SILK")
      (libsource (lib "eagle-import") (part "M01PTH_SMD_1.27X0.635MM_NO_SILK"))
    )
    (comp (ref "JP1108")
      (value "M01PTH_SMD_1.27X0.635MM_NO_SILK")
      (footprint "eagle-import:1X01_SMD_1.27X0.635MM_NO_SILK")
      (libsource (lib "eagle-import") (part "M01PTH_SMD_1.27X0.635MM_NO_SILK"))
    )
    (comp (ref "JP1109")
      (value "M01PTH_SMD_1.27X0.635MM_NO_SILK")
      (footprint "eagle-import:1X01_SMD_1.27X0.635MM_NO_SILK")
      (libsource (lib "eagle-import") (part "M01PTH_SMD_1.27X0.635MM_NO_SILK"))
    )
    (comp (ref "JP1110")
      (value "M01PTH_SMD_1.27X0.635MM_NO_SILK")
      (footprint "eagle-import:1X01_SMD_1.27X0.635MM_NO_SILK")
      (libsource (lib "eagle-import") (part "M01PTH_SMD_1.27X0.635MM_NO_SILK"))
    )
    (comp (ref "JP1111")
      (value "M01PTH_SMD_1.27X0.635MM_NO_SILK")
      (footprint "eagle-import:1X01_SMD_1.27X0.635MM_NO_SILK")
      (libsource (lib "eagle-import") (part "M01PTH_SMD_1.27X0.635MM_NO_SILK"))
    )
    (comp (ref "JP1112")
      (value "M01PTH_SMD_1.27X0.635MM_NO_SILK")
      (footprint "eagle-import:1X01_SMD_1.27X0.635MM_NO_SILK")
      (libsource (lib "eagle-import") (part "M01PTH_SMD_1.27X0.635MM_NO_SILK"))
    )
    (comp (ref "JP1113")
      (value "M01PTH_SMD_1.27X0.635MM_NO_SILK")
      (footprint "eagle-import:1X01_SMD_1.27X0.635MM_NO_SILK")
      (libsource (lib "eagle-import") (part "M01PTH_SMD_1.27X0.635MM_NO_SILK"))
    )
    (comp (ref "JP1114")
      (value "M01PTH_SMD_1.27X0.635MM_NO_SILK")
      (footprint "eagle-import:1X01_SMD_1.27X0.635MM_NO_SILK")
      (libsource (lib "eagle-import") (part "M01PTH_SMD_1.27X0.635MM_NO_SILK"))
    )
    (comp (ref "JP1115")
      (value "M01PTH_SMD_1.27X0.635MM_NO_SILK")
      (footprint "eagle-import:1X01_SMD_1.27X0.635MM_NO_SILK")
      (libsource (lib "eagle-import") (part "M01PTH_SMD_1.27X0.635MM_NO_SILK"))
    )
    (comp (ref "JP1116")
      (value "M01PTH_SMD_1.27X0.635MM_NO_SILK")
      (footprint "eagle-import:1X01_SMD_1.27X0.635MM_NO_SILK")
      (libsource (lib "eagle-import") (part "M01PTH_SMD_1.27X0.635MM_NO_SILK"))
    )
    (comp (ref "JP1117")
      (value "M01PTH_SMD_1.27X0.635MM_NO_SILK")
      (footprint "eagle-import:1X01_SMD_1.27X0.635MM_NO_SILK")
      (libsource (lib "eagle-import") (part "M01PTH_SMD_1.27X0.635MM_NO_SILK"))
    )
    (comp (ref "JP1118")
      (value "M01PTH_SMD_1.27X0.635MM_NO_SILK")
      (footprint "eagle-import:1X01_SMD_1.27X0.635MM_NO_SILK")
      (libsource (lib "eagle-import") (part "M01PTH_SMD_1.27X0.635MM_NO_SILK"))
    )
    (comp (ref "JP1119")
      (value "M01PTH_SMD_1.27X0.635MM_NO_SILK")
      (footprint "eagle-import:1X01_SMD_1.27X0.635MM_NO_SILK")
      (libsource (lib "eagle-import") (part "M01PTH_SMD_1.27X0.635MM_NO_SILK"))
    )
    (comp (ref "JP1120")
      (value "M01PTH_SMD_1.27X0.635MM_NO_SILK")
      (footprint "eagle-import:1X01_SMD_1.27X0.635MM_NO_SILK")
      (libsource (lib "eagle-import") (part "M01PTH_SMD_1.27X0.635MM_NO_SILK"))
    )
    (comp (ref "JP1121")
      (value "M01PTH_SMD_1.27X0.635MM_NO_SILK")
      (footprint "eagle-import:1X01_SMD_1.27X0.635MM_NO_SILK")
      (libsource (lib "eagle-import") (part "M01PTH_SMD_1.27X0.635MM_NO_SILK"))
    )
    (comp (ref "JP1122")
      (value "M01PTH_SMD_1.27X0.635MM_NO_SILK")
      (footprint "eagle-import:1X01_SMD_1.27X0.635MM_NO_SILK")
      (libsource (lib "eagle-import") (part "M01PTH_SMD_1.27X0.635MM_NO_SILK"))
    )
    (comp (ref "JP1123")
      (value "M01PTH_SMD_1.27X0.635MM_NO_SILK")
      (footprint "eagle-import:1X01_SMD_1.27X0.635MM_NO_SILK")
      (libsource (lib "eagle-import") (part "M01PTH_SMD_1.27X0.635MM_NO_SILK"))
    )
    (comp (ref "JP1124")
      (value "M01PTH_SMD_1.27X0.635MM_NO_SILK")
      (footprint "eagle-import:1X01_SMD_1.27X0.635MM_NO_SILK")
      (libsource (lib "eagle-import") (part "M01PTH_SMD_1.27X0.635MM_NO_SILK"))
    )
    (comp (ref "JP1125")
      (value "M01PTH_SMD_1.27X0.635MM_NO_SILK")
      (footprint "eagle-import:1X01_SMD_1.27X0.635MM_NO_SILK")
      (libsource (lib "eagle-import") (part "M01PTH_SMD_1.27X0.635MM_NO_SILK"))
    )
    (comp (ref "JP1126")
      (value "M01PTH_SMD_1.27X0.635MM_NO_SILK")
      (footprint "eagle-import:1X01_SMD_1.27X0.635MM_NO_SILK")
      (libsource (lib "eagle-import") (part "M01PTH_SMD_1.27X0.635MM_NO_SILK"))
    )
    (comp (ref "JP1127")
      (value "M01PTH_SMD_1.27X0.635MM_NO_SILK")
      (footprint "eagle-import:1X01_SMD_1.27X0.635MM_NO_SILK")
      (libsource (lib "eagle-import") (part "M01PTH_SMD_1.27X0.635MM_NO_SILK"))
    )
    (comp (ref "JP1128")
      (value "M01PTH_SMD_1.27X0.635MM_NO_SILK")
      (footprint "eagle-import:1X01_SMD_1.27X0.635MM_NO_SILK")
      (libsource (lib "eagle-import") (part "M01PTH_SMD_1.27X0.635MM_NO_SILK"))
    )
    (comp (ref "JP1129")
      (value "M01PTH_SMD_1.27X0.635MM_NO_SILK")
      (footprint "eagle-import:1X01_SMD_1.27X0.635MM_NO_SILK")
      (libsource (lib "eagle-import") (part "M01PTH_SMD_1.27X0.635MM_NO_SILK"))
    )
    (comp (ref "JP1130")
      (value "M01PTH_SMD_1.27X0.635MM_NO_SILK")
      (footprint "eagle-import:1X01_SMD_1.27X0.635MM_NO_SILK")
      (libsource (lib "eagle-import") (part "M01PTH_SMD_1.27X0.635MM_NO_SILK"))
    )
    (comp (ref "JP1131")
      (value "M01PTH_SMD_1.27X0.635MM_NO_SILK")
      (footprint "eagle-import:1X01_SMD_1.27X0.635MM_NO_SILK")
      (libsource (lib "eagle-import") (part "M01PTH_SMD_1.27X0.635MM_NO_SILK"))
    )
    (comp (ref "JP1132")
      (value "M01PTH_SMD_1.27X0.635MM_NO_SILK")
      (footprint "eagle-import:1X01_SMD_1.27X0.635MM_NO_SILK")
      (libsource (lib "eagle-import") (part "M01PTH_SMD_1.27X0.635MM_NO_SILK"))
    )
    (comp (ref "JP1133")
      (value "M01PTH_SMD_1.27X0.635MM_NO_SILK")
      (footprint "eagle-import:1X01_SMD_1.27X0.635MM_NO_SILK")
      (libsource (lib "eagle-import") (part "M01PTH_SMD_1.27X0.635MM_NO_SILK"))
    )
    (comp (ref "JP1134")
      (value "M01PTH_SMD_1.27X0.635MM_NO_SILK")
      (footprint "eagle-import:1X01_SMD_1.27X0.635MM_NO_SILK")
      (libsource (lib "eagle-import") (part "M01PTH_SMD_1.27X0.635MM_NO_SILK"))
    )
    (comp (ref "JP1135")
      (value "M01PTH_SMD_1.27X0.635MM_NO_SILK")
      (footprint "eagle-import:1X01_SMD_1.27X0.635MM_NO_SILK")
      (libsource (lib "eagle-import") (part "M01PTH_SMD_1.27X0.635MM_NO_SILK"))
    )
    (comp (ref "JP1136")
      (value "M01PTH_SMD_1.27X0.635MM_NO_SILK")
      (footprint "eagle-import:1X01_SMD_1.27X0.635MM_NO_SILK")
      (libsource (lib "eagle-import") (part "M01PTH_SMD_1.27X0.635MM_NO_SILK"))
    )
    (comp (ref "JP1137")
      (value "M01PTH_SMD_1.27X0.635MM_NO_SILK")
      (footprint "eagle-import:1X01_SMD_1.27X0.635MM_NO_SILK")
      (libsource (lib "eagle-import") (part "M01PTH_SMD_1.27X0.635MM_NO_SILK"))
    )
    (comp (ref "JP1138")
      (value "M01PTH_SMD_1.27X0.635MM_NO_SILK")
      (footprint "eagle-import:1X01_SMD_1.27X0.635MM_NO_SILK")
      (libsource (lib "eagle-import") (part "M01PTH_SMD_1.27X0.635MM_NO_SILK"))
    )
    (comp (ref "JP1139")
      (value "M01PTH_SMD_1.27X0.635MM_NO_SILK")
      (footprint "eagle-import:1X01_SMD_1.27X0.635MM_NO_SILK")
      (libsource (lib "eagle-import") (part "M01PTH_SMD_1.27X0.635MM_NO_SILK"))
    )
    (comp (ref "JP1140")
      (value "M01PTH_SMD_1.27X0.635MM_NO_SILK")
      (footprint "eagle-import:1X01_SMD_1.27X0.635MM_NO_SILK")
      (libsource (lib "eagle-import") (part "M01PTH_SMD_1.27X0.635MM_NO_SILK"))
    )
    (comp (ref "JP1141")
      (value "M01PTH_SMD_1.27X0.635MM_NO_SILK")
      (footprint "eagle-import:1X01_SMD_1.27X0.635MM_NO_SILK")
      (libsource (lib "eagle-import") (part "M01PTH_SMD_1.27X0.635MM_NO_SILK"))
    )
    (comp (ref "JP1142")
      (value "M01PTH_SMD_1.27X0.635MM_NO_SILK")
      (footprint "eagle-import:1X01_SMD_1.27X0.635MM_NO_SILK")
      (libsource (lib "eagle-import") (part "M01PTH_SMD_1.27X0.635MM_NO_SILK"))
    )
    (comp (ref "JP1143")
      (value "M01PTH_SMD_1.27X0.635MM_NO_SILK")
      (footprint "eagle-import:1X01_SMD_1.27X0.635MM_NO_SILK")
      (libsource (lib "eagle-import") (part "M01PTH_SMD_1.27X0.635MM_NO_SILK"))
    )
    (comp (ref "JP1144")
      (value "M01PTH_SMD_1.27X0.635MM_NO_SILK")
      (footprint "eagle-import:1X01_SMD_1.27X0.635MM_NO_SILK")
      (libsource (lib "eagle-import") (part "M01PTH_SMD_1.27X0.635MM_NO_SILK"))
    )
    (comp (ref "JP1145")
      (value "M01PTH_SMD_1.27X0.635MM_NO_SILK")
      (footprint "eagle-import:1X01_SMD_1.27X0.635MM_NO_SILK")
      (libsource (lib "eagle-import") (part "M01PTH_SMD_1.27X0.635MM_NO_SILK"))
    )
    (comp (ref "JP1146")
      (value "M01PTH_SMD_1.27X0.635MM_NO_SILK")
      (footprint "eagle-import:1X01_SMD_1.27X0.635MM_NO_SILK")
      (libsource (lib "eagle-import") (part "M01PTH_SMD_1.27X0.635MM_NO_SILK"))
    )
    (comp (ref "JP1147")
      (value "M01PTH_SMD_1.27X0.635MM_NO_SILK")
      (footprint "eagle-import:1X01_SMD_1.27X0.635MM_NO_SILK")
      (libsource (lib "eagle-import") (part "M01PTH_SMD_1.27X0.635MM_NO_SILK"))
    )
    (comp (ref "JP1148")
      (value "M01PTH_SMD_1.27X0.635MM_NO_SILK")
      (footprint "eagle-import:1X01_SMD_1.27X0.635MM_NO_SILK")
      (libsource (lib "eagle-import") (part "M01PTH_SMD_1.27X0.635MM_NO_SILK"))
    )
    (comp (ref "JP1149")
      (value "M01PTH_SMD_1.27X0.635MM_NO_SILK")
      (footprint "eagle-import:1X01_SMD_1.27X0.635MM_NO_SILK")
      (libsource (lib "eagle-import") (part "M01PTH_SMD_1.27X0.635MM_NO_SILK"))
    )
    (comp (ref "JP1150")
      (value "M01PTH_SMD_1.27X0.635MM_NO_SILK")
      (footprint "eagle-import:1X01_SMD_1.27X0.635MM_NO_SILK")
      (libsource (lib "eagle-import") (part "M01PTH_SMD_1.27X0.635MM_NO_SILK"))
    )
    (comp (ref "JP1151")
      (value "M01PTH_SMD_1.27X0.635MM_NO_SILK")
      (footprint "eagle-import:1X01_SMD_1.27X0.635MM_NO_SILK")
      (libsource (lib "eagle-import") (part "M01PTH_SMD_1.27X0.635MM_NO_SILK"))
    )
    (comp (ref "JP1152")
      (value "M01PTH_SMD_1.27X0.635MM_NO_SILK")
      (footprint "eagle-import:1X01_SMD_1.27X0.635MM_NO_SILK")
      (libsource (lib "eagle-import") (part "M01PTH_SMD_1.27X0.635MM_NO_SILK"))
    )
    (comp (ref "JP1153")
      (value "M01PTH_SMD_1.27X0.635MM_NO_SILK")
      (footprint "eagle-import:1X01_SMD_1.27X0.635MM_NO_SILK")
      (libsource (lib "eagle-import") (part "M01PTH_SMD_1.27X0.635MM_NO_SILK"))
    )
    (comp (ref "JP1154")
      (value "M01PTH_SMD_1.27X0.635MM_NO_SILK")
      (footprint "eagle-import:1X01_SMD_1.27X0.635MM_NO_SILK")
      (libsource (lib "eagle-import") (part "M01PTH_SMD_1.27X0.635MM_NO_SILK"))
    )
    (comp (ref "JP1155")
      (value "M01PTH_SMD_1.27X0.635MM_NO_SILK")
      (footprint "eagle-import:1X01_SMD_1.27X0.635MM_NO_SILK")
      (libsource (lib "eagle-import") (part "M01PTH_SMD_1.27X0.635MM_NO_SILK"))
    )
    (comp (ref "JP1156")
      (value "M01PTH_SMD_1.27X0.635MM_NO_SILK")
      (footprint "eagle-import:1X01_SMD_1.27X0.635MM_NO_SILK")
      (libsource (lib "eagle-import") (part "M01PTH_SMD_1.27X0.635MM_NO_SILK"))
    )
    (comp (ref "JP1157")
      (value "M01PTH_SMD_1.27X0.635MM_NO_SILK")
      (footprint "eagle-import:1X01_SMD_1.27X0.635MM_NO_SILK")
      (libsource (lib "eagle-import") (part "M01PTH_SMD_1.27X0.635MM_NO_SILK"))
    )
    (comp (ref "JP1158")
      (value "M01PTH_SMD_1.27X0.635MM_NO_SILK")
      (footprint "eagle-import:1X01_SMD_1.27X0.635MM_NO_SILK")
      (libsource (lib "eagle-import") (part "M01PTH_SMD_1.27X0.635MM_NO_SILK"))
    )
    (comp (ref "JP1159")
      (value "M01PTH_SMD_1.27X0.635MM_NO_SILK")
      (footprint "eagle-import:1X01_SMD_1.27X0.635MM_NO_SILK")
      (libsource (lib "eagle-import") (part "M01PTH_SMD_1.27X0.635MM_NO_SILK"))
    )
    (comp (ref "JP1160")
      (value "M01PTH_SMD_1.27X0.635MM_NO_SILK")
      (footprint "eagle-import:1X01_SMD_1.27X0.635MM_NO_SILK")
      (libsource (lib "eagle-import") (part "M01PTH_SMD_1.27X0.635MM_NO_SILK"))
    )
    (comp (ref "JP1161")
      (value "M01PTH_SMD_1.27X0.635MM_NO_SILK")
      (footprint "eagle-import:1X01_SMD_1.27X0.635MM_NO_SILK")
      (libsource (lib "eagle-import") (part "M01PTH_SMD_1.27X0.635MM_NO_SILK"))
    )
    (comp (ref "JP1162")
      (value "M01PTH_SMD_1.27X0.635MM_NO_SILK")
      (footprint "eagle-import:1X01_SMD_1.27X0.635MM_NO_SILK")
      (libsource (lib "eagle-import") (part "M01PTH_SMD_1.27X0.635MM_NO_SILK"))
    )
    (comp (ref "JP1163")
      (value "M01PTH_SMD_1.27X0.635MM_NO_SILK")
      (footprint "eagle-import:1X01_SMD_1.27X0.635MM_NO_SILK")
      (libsource (lib "eagle-import") (part "M01PTH_SMD_1.27X0.635MM_NO_SILK"))
    )
    (comp (ref "JP1164")
      (value "M01PTH_SMD_1.27X0.635MM_NO_SILK")
      (footprint "eagle-import:1X01_SMD_1.27X0.635MM_NO_SILK")
      (libsource (lib "eagle-import") (part "M01PTH_SMD_1.27X0.635MM_NO_SILK"))
    )
    (comp (ref "JP1165")
      (value "M01PTH_SMD_1.27X0.635MM_NO_SILK")
      (footprint "eagle-import:1X01_SMD_1.27X0.635MM_NO_SILK")
      (libsource (lib "eagle-import") (part "M01PTH_SMD_1.27X0.635MM_NO_SILK"))
    )
    (comp (ref "JP1166")
      (value "M01PTH_SMD_1.27X0.635MM_NO_SILK")
      (footprint "eagle-import:1X01_SMD_1.27X0.635MM_NO_SILK")
      (libsource (lib "eagle-import") (part "M01PTH_SMD_1.27X0.635MM_NO_SILK"))
    )
    (comp (ref "JP1167")
      (value "M01PTH_SMD_1.27X0.635MM_NO_SILK")
      (footprint "eagle-import:1X01_SMD_1.27X0.635MM_NO_SILK")
      (libsource (lib "eagle-import") (part "M01PTH_SMD_1.27X0.635MM_NO_SILK"))
    )
    (comp (ref "JP1168")
      (value "M01PTH_SMD_1.27X0.635MM_NO_SILK")
      (footprint "eagle-import:1X01_SMD_1.27X0.635MM_NO_SILK")
      (libsource (lib "eagle-import") (part "M01PTH_SMD_1.27X0.635MM_NO_SILK"))
    )
    (comp (ref "JP1169")
      (value "M01PTH_SMD_1.27X0.635MM_NO_SILK")
      (footprint "eagle-import:1X01_SMD_1.27X0.635MM_NO_SILK")
      (libsource (lib "eagle-import") (part "M01PTH_SMD_1.27X0.635MM_NO_SILK"))
    )
    (comp (ref "JP1170")
      (value "M01PTH_SMD_1.27X0.635MM_NO_SILK")
      (footprint "eagle-import:1X01_SMD_1.27X0.635MM_NO_SILK")
      (libsource (lib "eagle-import") (part "M01PTH_SMD_1.27X0.635MM_NO_SILK"))
    )
    (comp (ref "JP1171")
      (value "M01PTH_SMD_1.27X0.635MM_NO_SILK")
      (footprint "eagle-import:1X01_SMD_1.27X0.635MM_NO_SILK")
      (libsource (lib "eagle-import") (part "M01PTH_SMD_1.27X0.635MM_NO_SILK"))
    )
    (comp (ref "JP1172")
      (value "M01PTH_SMD_1.27X0.635MM_NO_SILK")
      (footprint "eagle-import:1X01_SMD_1.27X0.635MM_NO_SILK")
      (libsource (lib "eagle-import") (part "M01PTH_SMD_1.27X0.635MM_NO_SILK"))
    )
    (comp (ref "JP1173")
      (value "M01PTH_SMD_1.27X0.635MM_NO_SILK")
      (footprint "eagle-import:1X01_SMD_1.27X0.635MM_NO_SILK")
      (libsource (lib "eagle-import") (part "M01PTH_SMD_1.27X0.635MM_NO_SILK"))
    )
    (comp (ref "JP1174")
      (value "M01PTH_SMD_1.27X0.635MM_NO_SILK")
      (footprint "eagle-import:1X01_SMD_1.27X0.635MM_NO_SILK")
      (libsource (lib "eagle-import") (part "M01PTH_SMD_1.27X0.635MM_NO_SILK"))
    )
    (comp (ref "JP1175")
      (value "M01PTH_SMD_1.27X0.635MM_NO_SILK")
      (footprint "eagle-import:1X01_SMD_1.27X0.635MM_NO_SILK")
      (libsource (lib "eagle-import") (part "M01PTH_SMD_1.27X0.635MM_NO_SILK"))
    )
    (comp (ref "JP1176")
      (value "M01PTH_SMD_1.27X0.635MM_NO_SILK")
      (footprint "eagle-import:1X01_SMD_1.27X0.635MM_NO_SILK")
      (libsource (lib "eagle-import") (part "M01PTH_SMD_1.27X0.635MM_NO_SILK"))
    )
    (comp (ref "JP1177")
      (value "M01PTH_SMD_1.27X0.635MM_NO_SILK")
      (footprint "eagle-import:1X01_SMD_1.27X0.635MM_NO_SILK")
      (libsource (lib "eagle-import") (part "M01PTH_SMD_1.27X0.635MM_NO_SILK"))
    )
    (comp (ref "JP1178")
      (value "M01PTH_SMD_1.27X0.635MM_NO_SILK")
      (footprint "eagle-import:1X01_SMD_1.27X0.635MM_NO_SILK")
      (libsource (lib "eagle-import") (part "M01PTH_SMD_1.27X0.635MM_NO_SILK"))
    )
    (comp (ref "JP1179")
      (value "M01PTH_SMD_1.27X0.635MM_NO_SILK")
      (footprint "eagle-import:1X01_SMD_1.27X0.635MM_NO_SILK")
      (libsource (lib "eagle-import") (part "M01PTH_SMD_1.27X0.635MM_NO_SILK"))
    )
    (comp (ref "JP1180")
      (value "M01PTH_SMD_1.27X0.635MM_NO_SILK")
      (footprint "eagle-import:1X01_SMD_1.27X0.635MM_NO_SILK")
      (libsource (lib "eagle-import") (part "M01PTH_SMD_1.27X0.635MM_NO_SILK"))
    )
    (comp (ref "JP1181")
      (value "M01PTH_SMD_1.27X0.635MM_NO_SILK")
      (footprint "eagle-import:1X01_SMD_1.27X0.635MM_NO_SILK")
      (libsource (lib "eagle-import") (part "M01PTH_SMD_1.27X0.635MM_NO_SILK"))
    )
    (comp (ref "JP1182")
      (value "M01PTH_SMD_1.27X0.635MM_NO_SILK")
      (footprint "eagle-import:1X01_SMD_1.27X0.635MM_NO_SILK")
      (libsource (lib "eagle-import") (part "M01PTH_SMD_1.27X0.635MM_NO_SILK"))
    )
    (comp (ref "JP1183")
      (value "M01PTH_SMD_1.27X0.635MM_NO_SILK")
      (footprint "eagle-import:1X01_SMD_1.27X0.635MM_NO_SILK")
      (libsource (lib "eagle-import") (part "M01PTH_SMD_1.27X0.635MM_NO_SILK"))
    )
    (comp (ref "JP1184")
      (value "M01PTH_SMD_1.27X0.635MM_NO_SILK")
      (footprint "eagle-import:1X01_SMD_1.27X0.635MM_NO_SILK")
      (libsource (lib "eagle-import") (part "M01PTH_SMD_1.27X0.635MM_NO_SILK"))
    )
    (comp (ref "JP1185")
      (value "M01PTH_SMD_1.27X0.635MM_NO_SILK")
      (footprint "eagle-import:1X01_SMD_1.27X0.635MM_NO_SILK")
      (libsource (lib "eagle-import") (part "M01PTH_SMD_1.27X0.635MM_NO_SILK"))
    )
    (comp (ref "JP1186")
      (value "M01PTH_SMD_1.27X0.635MM_NO_SILK")
      (footprint "eagle-import:1X01_SMD_1.27X0.635MM_NO_SILK")
      (libsource (lib "eagle-import") (part "M01PTH_SMD_1.27X0.635MM_NO_SILK"))
    )
    (comp (ref "JP1187")
      (value "M01PTH_SMD_1.27X0.635MM_NO_SILK")
      (footprint "eagle-import:1X01_SMD_1.27X0.635MM_NO_SILK")
      (libsource (lib "eagle-import") (part "M01PTH_SMD_1.27X0.635MM_NO_SILK"))
    )
    (comp (ref "JP1188")
      (value "M01PTH_SMD_1.27X0.635MM_NO_SILK")
      (footprint "eagle-import:1X01_SMD_1.27X0.635MM_NO_SILK")
      (libsource (lib "eagle-import") (part "M01PTH_SMD_1.27X0.635MM_NO_SILK"))
    )
    (comp (ref "JP1189")
      (value "M01PTH_SMD_1.27X0.635MM_NO_SILK")
      (footprint "eagle-import:1X01_SMD_1.27X0.635MM_NO_SILK")
      (libsource (lib "eagle-import") (part "M01PTH_SMD_1.27X0.635MM_NO_SILK"))
    )
    (comp (ref "JP1190")
      (value "M01PTH_SMD_1.27X0.635MM_NO_SILK")
      (footprint "eagle-import:1X01_SMD_1.27X0.635MM_NO_SILK")
      (libsource (lib "eagle-import") (part "M01PTH_SMD_1.27X0.635MM_NO_SILK"))
    )
    (comp (ref "JP1191")
      (value "M01PTH_SMD_1.27X0.635MM_NO_SILK")
      (footprint "eagle-import:1X01_SMD_1.27X0.635MM_NO_SILK")
      (libsource (lib "eagle-import") (part "M01PTH_SMD_1.27X0.635MM_NO_SILK"))
    )
    (comp (ref "JP1192")
      (value "M01PTH_SMD_1.27X0.635MM_NO_SILK")
      (footprint "eagle-import:1X01_SMD_1.27X0.635MM_NO_SILK")
      (libsource (lib "eagle-import") (part "M01PTH_SMD_1.27X0.635MM_NO_SILK"))
    )
    (comp (ref "JP1193")
      (value "M01PTH_SMD_1.27X0.635MM_NO_SILK")
      (footprint "eagle-import:1X01_SMD_1.27X0.635MM_NO_SILK")
      (libsource (lib "eagle-import") (part "M01PTH_SMD_1.27X0.635MM_NO_SILK"))
    )
    (comp (ref "JP1194")
      (value "M01PTH_SMD_1.27X0.635MM_NO_SILK")
      (footprint "eagle-import:1X01_SMD_1.27X0.635MM_NO_SILK")
      (libsource (lib "eagle-import") (part "M01PTH_SMD_1.27X0.635MM_NO_SILK"))
    )
    (comp (ref "JP1195")
      (value "M01PTH_SMD_1.27X0.635MM_NO_SILK")
      (footprint "eagle-import:1X01_SMD_1.27X0.635MM_NO_SILK")
      (libsource (lib "eagle-import") (part "M01PTH_SMD_1.27X0.635MM_NO_SILK"))
    )
    (comp (ref "JP1196")
      (value "M01PTH_SMD_1.27X0.635MM_NO_SILK")
      (footprint "eagle-import:1X01_SMD_1.27X0.635MM_NO_SILK")
      (libsource (lib "eagle-import") (part "M01PTH_SMD_1.27X0.635MM_NO_SILK"))
    )
    (comp (ref "JP1197")
      (value "M01PTH_SMD_1.27X0.635MM_NO_SILK")
      (footprint "eagle-import:1X01_SMD_1.27X0.635MM_NO_SILK")
      (libsource (lib "eagle-import") (part "M01PTH_SMD_1.27X0.635MM_NO_SILK"))
    )
    (comp (ref "JP1198")
      (value "M01PTH_SMD_1.27X0.635MM_NO_SILK")
      (footprint "eagle-import:1X01_SMD_1.27X0.635MM_NO_SILK")
      (libsource (lib "eagle-import") (part "M01PTH_SMD_1.27X0.635MM_NO_SILK"))
    )
    (comp (ref "JP1199")
      (value "M01PTH_SMD_1.27X0.635MM_NO_SILK")
      (footprint "eagle-import:1X01_SMD_1.27X0.635MM_NO_SILK")
      (libsource (lib "eagle-import") (part "M01PTH_SMD_1.27X0.635MM_NO_SILK"))
    )
    (comp (ref "JP1200")
      (value "M01PTH_SMD_1.27X0.635MM_NO_SILK")
      (footprint "eagle-import:1X01_SMD_1.27X0.635MM_NO_SILK")
      (libsource (lib "eagle-import") (part "M01PTH_SMD_1.27X0.635MM_NO_SILK"))
    )
  )
  (nets
    (net (code "1") (name "/0_1439380519") (class "Default")
      (node (ref "JP1") (pin "1") (pinfunction "1_1") (pintype "passive"))
      (node (ref "JP961") (pin "P$2") (pinfunction "1_P$2") (pintype "passive"))
    )
    (net (code "2") (name "/0_1439380547") (class "Default")
      (node (ref "JP1141") (pin "P$2") (pinfunction "1_P$2") (pintype "passive"))
      (node (ref "JP2") (pin "1") (pinfunction "1_1") (pintype "passive"))
    )
    (net (code "3") (name "/0_1439380570") (class "Default")
      (node (ref "JP10") (pin "1") (pinfunction "1_1") (pintype "passive"))
      (node (ref "JP1021") (pin "P$2") (pinfunction "1_P$2") (pintype "passive"))
    )
    (net (code "4") (name "/0_1439380605") (class "Default")
      (node (ref "JP1161") (pin "P$2") (pinfunction "1_P$2") (pintype "passive"))
      (node (ref "JP6") (pin "1") (pinfunction "1_1") (pintype "passive"))
    )
    (net (code "5") (name "/0_1439380652") (class "Default")
      (node (ref "JP63") (pin "1") (pinfunction "1_1") (pintype "passive"))
      (node (ref "JP901") (pin "P$2") (pinfunction "1_P$2") (pintype "passive"))
    )
    (net (code "6") (name "/0_1439380747") (class "Default")
      (node (ref "JP1081") (pin "P$2") (pinfunction "1_P$2") (pintype "passive"))
      (node (ref "JP68") (pin "1") (pinfunction "1_1") (pintype "passive"))
    )
    (net (code "7") (name "/1_1439380519") (class "Default")
      (node (ref "JP11") (pin "1") (pinfunction "1_1") (pintype "passive"))
      (node (ref "JP962") (pin "P$2") (pinfunction "1_P$2") (pintype "passive"))
    )
    (net (code "8") (name "/1_1439380547") (class "Default")
      (node (ref "JP1142") (pin "P$2") (pinfunction "1_P$2") (pintype "passive"))
      (node (ref "JP3") (pin "1") (pinfunction "1_1") (pintype "passive"))
    )
    (net (code "9") (name "/1_1439380570") (class "Default")
      (node (ref "JP1022") (pin "P$2") (pinfunction "1_P$2") (pintype "passive"))
      (node (ref "JP20") (pin "1") (pinfunction "1_1") (pintype "passive"))
    )
    (net (code "10") (name "/1_1439380605") (class "Default")
      (node (ref "JP1162") (pin "P$2") (pinfunction "1_P$2") (pintype "passive"))
      (node (ref "JP7") (pin "1") (pinfunction "1_1") (pintype "passive"))
    )
    (net (code "11") (name "/1_1439380652") (class "Default")
      (node (ref "JP73") (pin "1") (pinfunction "1_1") (pintype "passive"))
      (node (ref "JP902") (pin "P$2") (pinfunction "1_P$2") (pintype "passive"))
    )
    (net (code "12") (name "/1_1439380747") (class "Default")
      (node (ref "JP1082") (pin "P$2") (pinfunction "1_P$2") (pintype "passive"))
      (node (ref "JP78") (pin "1") (pinfunction "1_1") (pintype "passive"))
    )
    (net (code "13") (name "/2_1439380519") (class "Default")
      (node (ref "JP21") (pin "1") (pinfunction "1_1") (pintype "passive"))
      (node (ref "JP963") (pin "P$2") (pinfunction "1_P$2") (pintype "passive"))
    )
    (net (code "14") (name "/2_1439380547") (class "Default")
      (node (ref "JP1143") (pin "P$2") (pinfunction "1_P$2") (pintype "passive"))
      (node (ref "JP4") (pin "1") (pinfunction "1_1") (pintype "passive"))
    )
    (net (code "15") (name "/2_1439380570") (class "Default")
      (node (ref "JP1023") (pin "P$2") (pinfunction "1_P$2") (pintype "passive"))
      (node (ref "JP30") (pin "1") (pinfunction "1_1") (pintype "passive"))
    )
    (net (code "16") (name "/2_1439380605") (class "Default")
      (node (ref "JP1163") (pin "P$2") (pinfunction "1_P$2") (pintype "passive"))
      (node (ref "JP8") (pin "1") (pinfunction "1_1") (pintype "passive"))
    )
    (net (code "17") (name "/2_1439380652") (class "Default")
      (node (ref "JP64") (pin "1") (pinfunction "1_1") (pintype "passive"))
      (node (ref "JP903") (pin "P$2") (pinfunction "1_P$2") (pintype "passive"))
    )
    (net (code "18") (name "/2_1439380747") (class "Default")
      (node (ref "JP1083") (pin "P$2") (pinfunction "1_P$2") (pintype "passive"))
      (node (ref "JP67") (pin "1") (pinfunction "1_1") (pintype "passive"))
    )
    (net (code "19") (name "/3_1439380519") (class "Default")
      (node (ref "JP31") (pin "1") (pinfunction "1_1") (pintype "passive"))
      (node (ref "JP964") (pin "P$2") (pinfunction "1_P$2") (pintype "passive"))
    )
    (net (code "20") (name "/3_1439380547") (class "Default")
      (node (ref "JP1144") (pin "P$2") (pinfunction "1_P$2") (pintype "passive"))
      (node (ref "JP5") (pin "1") (pinfunction "1_1") (pintype "passive"))
    )
    (net (code "21") (name "/3_1439380570") (class "Default")
      (node (ref "JP1024") (pin "P$2") (pinfunction "1_P$2") (pintype "passive"))
      (node (ref "JP40") (pin "1") (pinfunction "1_1") (pintype "passive"))
    )
    (net (code "22") (name "/3_1439380605") (class "Default")
      (node (ref "JP1164") (pin "P$2") (pinfunction "1_P$2") (pintype "passive"))
      (node (ref "JP9") (pin "1") (pinfunction "1_1") (pintype "passive"))
    )
    (net (code "23") (name "/3_1439380652") (class "Default")
      (node (ref "JP83") (pin "1") (pinfunction "1_1") (pintype "passive"))
      (node (ref "JP904") (pin "P$2") (pinfunction "1_P$2") (pintype "passive"))
    )
    (net (code "24") (name "/3_1439380747") (class "Default")
      (node (ref "JP1084") (pin "P$2") (pinfunction "1_P$2") (pintype "passive"))
      (node (ref "JP88") (pin "1") (pinfunction "1_1") (pintype "passive"))
    )
    (net (code "25") (name "/4_1439380519") (class "Default")
      (node (ref "JP41") (pin "1") (pinfunction "1_1") (pintype "passive"))
      (node (ref "JP965") (pin "P$2") (pinfunction "1_P$2") (pintype "passive"))
    )
    (net (code "26") (name "/4_1439380547") (class "Default")
      (node (ref "JP1145") (pin "P$2") (pinfunction "1_P$2") (pintype "passive"))
      (node (ref "JP13") (pin "1") (pinfunction "1_1") (pintype "passive"))
    )
    (net (code "27") (name "/4_1439380570") (class "Default")
      (node (ref "JP1025") (pin "P$2") (pinfunction "1_P$2") (pintype "passive"))
      (node (ref "JP50") (pin "1") (pinfunction "1_1") (pintype "passive"))
    )
    (net (code "28") (name "/4_1439380605") (class "Default")
      (node (ref "JP1165") (pin "P$2") (pinfunction "1_P$2") (pintype "passive"))
      (node (ref "JP18") (pin "1") (pinfunction "1_1") (pintype "passive"))
    )
    (net (code "29") (name "/4_1439380652") (class "Default")
      (node (ref "JP74") (pin "1") (pinfunction "1_1") (pintype "passive"))
      (node (ref "JP905") (pin "P$2") (pinfunction "1_P$2") (pintype "passive"))
    )
    (net (code "30") (name "/4_1439380747") (class "Default")
      (node (ref "JP1085") (pin "P$2") (pinfunction "1_P$2") (pintype "passive"))
      (node (ref "JP77") (pin "1") (pinfunction "1_1") (pintype "passive"))
    )
    (net (code "31") (name "/5_1439380519") (class "Default")
      (node (ref "JP22") (pin "1") (pinfunction "1_1") (pintype "passive"))
      (node (ref "JP966") (pin "P$2") (pinfunction "1_P$2") (pintype "passive"))
    )
    (net (code "32") (name "/5_1439380547") (class "Default")
      (node (ref "JP1146") (pin "P$2") (pinfunction "1_P$2") (pintype "passive"))
      (node (ref "JP14") (pin "1") (pinfunction "1_1") (pintype "passive"))
    )
    (net (code "33") (name "/5_1439380570") (class "Default")
      (node (ref "JP1026") (pin "P$2") (pinfunction "1_P$2") (pintype "passive"))
      (node (ref "JP29") (pin "1") (pinfunction "1_1") (pintype "passive"))
    )
    (net (code "34") (name "/5_1439380605") (class "Default")
      (node (ref "JP1166") (pin "P$2") (pinfunction "1_P$2") (pintype "passive"))
      (node (ref "JP19") (pin "1") (pinfunction "1_1") (pintype "passive"))
    )
    (net (code "35") (name "/5_1439380652") (class "Default")
      (node (ref "JP65") (pin "1") (pinfunction "1_1") (pintype "passive"))
      (node (ref "JP906") (pin "P$2") (pinfunction "1_P$2") (pintype "passive"))
    )
    (net (code "36") (name "/5_1439380747") (class "Default")
      (node (ref "JP1086") (pin "P$2") (pinfunction "1_P$2") (pintype "passive"))
      (node (ref "JP66") (pin "1") (pinfunction "1_1") (pintype "passive"))
    )
    (net (code "37") (name "/6_1439380519") (class "Default")
      (node (ref "JP51") (pin "1") (pinfunction "1_1") (pintype "passive"))
      (node (ref "JP967") (pin "P$2") (pinfunction "1_P$2") (pintype "passive"))
    )
    (net (code "38") (name "/6_1439380547") (class "Default")
      (node (ref "JP1147") (pin "P$2") (pinfunction "1_P$2") (pintype "passive"))
      (node (ref "JP15") (pin "1") (pinfunction "1_1") (pintype "passive"))
    )
    (net (code "39") (name "/6_1439380570") (class "Default")
      (node (ref "JP1027") (pin "P$2") (pinfunction "1_P$2") (pintype "passive"))
      (node (ref "JP60") (pin "1") (pinfunction "1_1") (pintype "passive"))
    )
    (net (code "40") (name "/6_1439380605") (class "Default")
      (node (ref "JP1167") (pin "P$2") (pinfunction "1_P$2") (pintype "passive"))
      (node (ref "JP17") (pin "1") (pinfunction "1_1") (pintype "passive"))
    )
    (net (code "41") (name "/6_1439380652") (class "Default")
      (node (ref "JP907") (pin "P$2") (pinfunction "1_P$2") (pintype "passive"))
      (node (ref "JP93") (pin "1") (pinfunction "1_1") (pintype "passive"))
    )
    (net (code "42") (name "/6_1439380747") (class "Default")
      (node (ref "JP1087") (pin "P$2") (pinfunction "1_P$2") (pintype "passive"))
      (node (ref "JP98") (pin "1") (pinfunction "1_1") (pintype "passive"))
    )
    (net (code "43") (name "/7_1439380519") (class "Default")
      (node (ref "JP32") (pin "1") (pinfunction "1_1") (pintype "passive"))
      (node (ref "JP968") (pin "P$2") (pinfunction "1_P$2") (pintype "passive"))
    )
    (net (code "44") (name "/7_1439380547") (class "Default")
      (node (ref "JP1148") (pin "P$2") (pinfunction "1_P$2") (pintype "passive"))
      (node (ref "JP12") (pin "1") (pinfunction "1_1") (pintype "passive"))
    )
    (net (code "45") (name "/7_1439380570") (class "Default")
      (node (ref "JP1028") (pin "P$2") (pinfunction "1_P$2") (pintype "passive"))
      (node (ref "JP39") (pin "1") (pinfunction "1_1") (pintype "passive"))
    )
    (net (code "46") (name "/7_1439380605") (class "Default")
      (node (ref "JP1168") (pin "P$2") (pinfunction "1_P$2") (pintype "passive"))
      (node (ref "JP16") (pin "1") (pinfunction "1_1") (pintype "passive"))
    )
    (net (code "47") (name "/7_1439380652") (class "Default")
      (node (ref "JP84") (pin "1") (pinfunction "1_1") (pintype "passive"))
      (node (ref "JP908") (pin "P$2") (pinfunction "1_P$2") (pintype "passive"))
    )
    (net (code "48") (name "/7_1439380747") (class "Default")
      (node (ref "JP1088") (pin "P$2") (pinfunction "1_P$2") (pintype "passive"))
      (node (ref "JP87") (pin "1") (pinfunction "1_1") (pintype "passive"))
    )
    (net (code "49") (name "/8_1439380519") (class "Default")
      (node (ref "JP61") (pin "1") (pinfunction "1_1") (pintype "passive"))
      (node (ref "JP969") (pin "P$2") (pinfunction "1_P$2") (pintype "passive"))
    )
    (net (code "50") (name "/8_1439380547") (class "Default")
      (node (ref "JP1149") (pin "P$2") (pinfunction "1_P$2") (pintype "passive"))
      (node (ref "JP25") (pin "1") (pinfunction "1_1") (pintype "passive"))
    )
    (net (code "51") (name "/8_1439380570") (class "Default")
      (node (ref "JP1029") (pin "P$2") (pinfunction "1_P$2") (pintype "passive"))
      (node (ref "JP70") (pin "1") (pinfunction "1_1") (pintype "passive"))
    )
    (net (code "52") (name "/8_1439380605") (class "Default")
      (node (ref "JP1169") (pin "P$2") (pinfunction "1_P$2") (pintype "passive"))
      (node (ref "JP28") (pin "1") (pinfunction "1_1") (pintype "passive"))
    )
    (net (code "53") (name "/8_1439380652") (class "Default")
      (node (ref "JP75") (pin "1") (pinfunction "1_1") (pintype "passive"))
      (node (ref "JP909") (pin "P$2") (pinfunction "1_P$2") (pintype "passive"))
    )
    (net (code "54") (name "/8_1439380747") (class "Default")
      (node (ref "JP1089") (pin "P$2") (pinfunction "1_P$2") (pintype "passive"))
      (node (ref "JP76") (pin "1") (pinfunction "1_1") (pintype "passive"))
    )
    (net (code "55") (name "/9_1439380519") (class "Default")
      (node (ref "JP42") (pin "1") (pinfunction "1_1") (pintype "passive"))
      (node (ref "JP970") (pin "P$2") (pinfunction "1_P$2") (pintype "passive"))
    )
    (net (code "56") (name "/9_1439380547") (class "Default")
      (node (ref "JP1150") (pin "P$2") (pinfunction "1_P$2") (pintype "passive"))
      (node (ref "JP24") (pin "1") (pinfunction "1_1") (pintype "passive"))
    )
    (net (code "57") (name "/9_1439380570") (class "Default")
      (node (ref "JP1030") (pin "P$2") (pinfunction "1_P$2") (pintype "passive"))
      (node (ref "JP49") (pin "1") (pinfunction "1_1") (pintype "passive"))
    )
    (net (code "58") (name "/9_1439380605") (class "Default")
      (node (ref "JP1170") (pin "P$2") (pinfunction "1_P$2") (pintype "passive"))
      (node (ref "JP27") (pin "1") (pinfunction "1_1") (pintype "passive"))
    )
    (net (code "59") (name "/9_1439380652") (class "Default")
      (node (ref "JP103") (pin "1") (pinfunction "1_1") (pintype "passive"))
      (node (ref "JP910") (pin "P$2") (pinfunction "1_P$2") (pintype "passive"))
    )
    (net (code "60") (name "/9_1439380747") (class "Default")
      (node (ref "JP108") (pin "1") (pinfunction "1_1") (pintype "passive"))
      (node (ref "JP1090") (pin "P$2") (pinfunction "1_P$2") (pintype "passive"))
    )
    (net (code "61") (name "/10_1439380519") (class "Default")
      (node (ref "JP71") (pin "1") (pinfunction "1_1") (pintype "passive"))
      (node (ref "JP971") (pin "P$2") (pinfunction "1_P$2") (pintype "passive"))
    )
    (net (code "62") (name "/10_1439380547") (class "Default")
      (node (ref "JP1151") (pin "P$2") (pinfunction "1_P$2") (pintype "passive"))
      (node (ref "JP23") (pin "1") (pinfunction "1_1") (pintype "passive"))
    )
    (net (code "63") (name "/10_1439380570") (class "Default")
      (node (ref "JP1031") (pin "P$2") (pinfunction "1_P$2") (pintype "passive"))
      (node (ref "JP80") (pin "1") (pinfunction "1_1") (pintype "passive"))
    )
    (net (code "64") (name "/10_1439380605") (class "Default")
      (node (ref "JP1171") (pin "P$2") (pinfunction "1_P$2") (pintype "passive"))
      (node (ref "JP26") (pin "1") (pinfunction "1_1") (pintype "passive"))
    )
    (net (code "65") (name "/10_1439380652") (class "Default")
      (node (ref "JP911") (pin "P$2") (pinfunction "1_P$2") (pintype "passive"))
      (node (ref "JP94") (pin "1") (pinfunction "1_1") (pintype "passive"))
    )
    (net (code "66") (name "/10_1439380747") (class "Default")
      (node (ref "JP1091") (pin "P$2") (pinfunction "1_P$2") (pintype "passive"))
      (node (ref "JP97") (pin "1") (pinfunction "1_1") (pintype "passive"))
    )
    (net (code "67") (name "/11_1439380519") (class "Default")
      (node (ref "JP52") (pin "1") (pinfunction "1_1") (pintype "passive"))
      (node (ref "JP972") (pin "P$2") (pinfunction "1_P$2") (pintype "passive"))
    )
    (net (code "68") (name "/11_1439380547") (class "Default")
      (node (ref "JP1152") (pin "P$2") (pinfunction "1_P$2") (pintype "passive"))
      (node (ref "JP33") (pin "1") (pinfunction "1_1") (pintype "passive"))
    )
    (net (code "69") (name "/11_1439380570") (class "Default")
      (node (ref "JP1032") (pin "P$2") (pinfunction "1_P$2") (pintype "passive"))
      (node (ref "JP59") (pin "1") (pinfunction "1_1") (pintype "passive"))
    )
    (net (code "70") (name "/11_1439380605") (class "Default")
      (node (ref "JP1172") (pin "P$2") (pinfunction "1_P$2") (pintype "passive"))
      (node (ref "JP36") (pin "1") (pinfunction "1_1") (pintype "passive"))
    )
    (net (code "71") (name "/11_1439380652") (class "Default")
      (node (ref "JP113") (pin "1") (pinfunction "1_1") (pintype "passive"))
      (node (ref "JP912") (pin "P$2") (pinfunction "1_P$2") (pintype "passive"))
    )
    (net (code "72") (name "/11_1439380747") (class "Default")
      (node (ref "JP1092") (pin "P$2") (pinfunction "1_P$2") (pintype "passive"))
      (node (ref "JP118") (pin "1") (pinfunction "1_1") (pintype "passive"))
    )
    (net (code "73") (name "/12_1439380519") (class "Default")
      (node (ref "JP81") (pin "1") (pinfunction "1_1") (pintype "passive"))
      (node (ref "JP973") (pin "P$2") (pinfunction "1_P$2") (pintype "passive"))
    )
    (net (code "74") (name "/12_1439380547") (class "Default")
      (node (ref "JP1153") (pin "P$2") (pinfunction "1_P$2") (pintype "passive"))
      (node (ref "JP34") (pin "1") (pinfunction "1_1") (pintype "passive"))
    )
    (net (code "75") (name "/12_1439380570") (class "Default")
      (node (ref "JP1033") (pin "P$2") (pinfunction "1_P$2") (pintype "passive"))
      (node (ref "JP90") (pin "1") (pinfunction "1_1") (pintype "passive"))
    )
    (net (code "76") (name "/12_1439380605") (class "Default")
      (node (ref "JP1173") (pin "P$2") (pinfunction "1_P$2") (pintype "passive"))
      (node (ref "JP37") (pin "1") (pinfunction "1_1") (pintype "passive"))
    )
    (net (code "77") (name "/12_1439380652") (class "Default")
      (node (ref "JP104") (pin "1") (pinfunction "1_1") (pintype "passive"))
      (node (ref "JP913") (pin "P$2") (pinfunction "1_P$2") (pintype "passive"))
    )
    (net (code "78") (name "/12_1439380747") (class "Default")
      (node (ref "JP107") (pin "1") (pinfunction "1_1") (pintype "passive"))
      (node (ref "JP1093") (pin "P$2") (pinfunction "1_P$2") (pintype "passive"))
    )
    (net (code "79") (name "/13_1439380519") (class "Default")
      (node (ref "JP62") (pin "1") (pinfunction "1_1") (pintype "passive"))
      (node (ref "JP974") (pin "P$2") (pinfunction "1_P$2") (pintype "passive"))
    )
    (net (code "80") (name "/13_1439380547") (class "Default")
      (node (ref "JP1154") (pin "P$2") (pinfunction "1_P$2") (pintype "passive"))
      (node (ref "JP35") (pin "1") (pinfunction "1_1") (pintype "passive"))
    )
    (net (code "81") (name "/13_1439380570") (class "Default")
      (node (ref "JP1034") (pin "P$2") (pinfunction "1_P$2") (pintype "passive"))
      (node (ref "JP69") (pin "1") (pinfunction "1_1") (pintype "passive"))
    )
    (net (code "82") (name "/13_1439380605") (class "Default")
      (node (ref "JP1174") (pin "P$2") (pinfunction "1_P$2") (pintype "passive"))
      (node (ref "JP38") (pin "1") (pinfunction "1_1") (pintype "passive"))
    )
    (net (code "83") (name "/13_1439380652") (class "Default")
      (node (ref "JP85") (pin "1") (pinfunction "1_1") (pintype "passive"))
      (node (ref "JP914") (pin "P$2") (pinfunction "1_P$2") (pintype "passive"))
    )
    (net (code "84") (name "/13_1439380747") (class "Default")
      (node (ref "JP1094") (pin "P$2") (pinfunction "1_P$2") (pintype "passive"))
      (node (ref "JP86") (pin "1") (pinfunction "1_1") (pintype "passive"))
    )
    (net (code "85") (name "/14_1439380519") (class "Default")
      (node (ref "JP91") (pin "1") (pinfunction "1_1") (pintype "passive"))
      (node (ref "JP975") (pin "P$2") (pinfunction "1_P$2") (pintype "passive"))
    )
    (net (code "86") (name "/14_1439380547") (class "Default")
      (node (ref "JP1155") (pin "P$2") (pinfunction "1_P$2") (pintype "passive"))
      (node (ref "JP43") (pin "1") (pinfunction "1_1") (pintype "passive"))
    )
    (net (code "87") (name "/14_1439380570") (class "Default")
      (node (ref "JP100") (pin "1") (pinfunction "1_1") (pintype "passive"))
      (node (ref "JP1035") (pin "P$2") (pinfunction "1_P$2") (pintype "passive"))
    )
    (net (code "88") (name "/14_1439380605") (class "Default")
      (node (ref "JP1175") (pin "P$2") (pinfunction "1_P$2") (pintype "passive"))
      (node (ref "JP48") (pin "1") (pinfunction "1_1") (pintype "passive"))
    )
    (net (code "89") (name "/14_1439380652") (class "Default")
      (node (ref "JP123") (pin "1") (pinfunction "1_1") (pintype "passive"))
      (node (ref "JP915") (pin "P$2") (pinfunction "1_P$2") (pintype "passive"))
    )
    (net (code "90") (name "/14_1439380747") (class "Default")
      (node (ref "JP1095") (pin "P$2") (pinfunction "1_P$2") (pintype "passive"))
      (node (ref "JP128") (pin "1") (pinfunction "1_1") (pintype "passive"))
    )
    (net (code "91") (name "/15_1439380519") (class "Default")
      (node (ref "JP72") (pin "1") (pinfunction "1_1") (pintype "passive"))
      (node (ref "JP976") (pin "P$2") (pinfunction "1_P$2") (pintype "passive"))
    )
    (net (code "92") (name "/15_1439380547") (class "Default")
      (node (ref "JP1156") (pin "P$2") (pinfunction "1_P$2") (pintype "passive"))
      (node (ref "JP44") (pin "1") (pinfunction "1_1") (pintype "passive"))
    )
    (net (code "93") (name "/15_1439380570") (class "Default")
      (node (ref "JP1036") (pin "P$2") (pinfunction "1_P$2") (pintype "passive"))
      (node (ref "JP79") (pin "1") (pinfunction "1_1") (pintype "passive"))
    )
    (net (code "94") (name "/15_1439380605") (class "Default")
      (node (ref "JP1176") (pin "P$2") (pinfunction "1_P$2") (pintype "passive"))
      (node (ref "JP47") (pin "1") (pinfunction "1_1") (pintype "passive"))
    )
    (net (code "95") (name "/15_1439380652") (class "Default")
      (node (ref "JP114") (pin "1") (pinfunction "1_1") (pintype "passive"))
      (node (ref "JP916") (pin "P$2") (pinfunction "1_P$2") (pintype "passive"))
    )
    (net (code "96") (name "/15_1439380747") (class "Default")
      (node (ref "JP1096") (pin "P$2") (pinfunction "1_P$2") (pintype "passive"))
      (node (ref "JP117") (pin "1") (pinfunction "1_1") (pintype "passive"))
    )
    (net (code "97") (name "/16_1439380519") (class "Default")
      (node (ref "JP101") (pin "1") (pinfunction "1_1") (pintype "passive"))
      (node (ref "JP977") (pin "P$2") (pinfunction "1_P$2") (pintype "passive"))
    )
    (net (code "98") (name "/16_1439380547") (class "Default")
      (node (ref "JP1157") (pin "P$2") (pinfunction "1_P$2") (pintype "passive"))
      (node (ref "JP45") (pin "1") (pinfunction "1_1") (pintype "passive"))
    )
    (net (code "99") (name "/16_1439380570") (class "Default")
      (node (ref "JP1037") (pin "P$2") (pinfunction "1_P$2") (pintype "passive"))
      (node (ref "JP110") (pin "1") (pinfunction "1_1") (pintype "passive"))
    )
    (net (code "100") (name "/16_1439380605") (class "Default")
      (node (ref "JP1177") (pin "P$2") (pinfunction "1_P$2") (pintype "passive"))
      (node (ref "JP46") (pin "1") (pinfunction "1_1") (pintype "passive"))
    )
    (net (code "101") (name "/16_1439380652") (class "Default")
      (node (ref "JP133") (pin "1") (pinfunction "1_1") (pintype "passive"))
      (node (ref "JP917") (pin "P$2") (pinfunction "1_P$2") (pintype "passive"))
    )
    (net (code "102") (name "/16_1439380747") (class "Default")
      (node (ref "JP1097") (pin "P$2") (pinfunction "1_P$2") (pintype "passive"))
      (node (ref "JP138") (pin "1") (pinfunction "1_1") (pintype "passive"))
    )
    (net (code "103") (name "/17_1439380519") (class "Default")
      (node (ref "JP82") (pin "1") (pinfunction "1_1") (pintype "passive"))
      (node (ref "JP978") (pin "P$2") (pinfunction "1_P$2") (pintype "passive"))
    )
    (net (code "104") (name "/17_1439380547") (class "Default")
      (node (ref "JP1158") (pin "P$2") (pinfunction "1_P$2") (pintype "passive"))
      (node (ref "JP54") (pin "1") (pinfunction "1_1") (pintype "passive"))
    )
    (net (code "105") (name "/17_1439380570") (class "Default")
      (node (ref "JP1038") (pin "P$2") (pinfunction "1_P$2") (pintype "passive"))
      (node (ref "JP89") (pin "1") (pinfunction "1_1") (pintype "passive"))
    )
    (net (code "106") (name "/17_1439380605") (class "Default")
      (node (ref "JP1178") (pin "P$2") (pinfunction "1_P$2") (pintype "passive"))
      (node (ref "JP58") (pin "1") (pinfunction "1_1") (pintype "passive"))
    )
    (net (code "107") (name "/17_1439380652") (class "Default")
      (node (ref "JP124") (pin "1") (pinfunction "1_1") (pintype "passive"))
      (node (ref "JP918") (pin "P$2") (pinfunction "1_P$2") (pintype "passive"))
    )
    (net (code "108") (name "/17_1439380747") (class "Default")
      (node (ref "JP1098") (pin "P$2") (pinfunction "1_P$2") (pintype "passive"))
      (node (ref "JP127") (pin "1") (pinfunction "1_1") (pintype "passive"))
    )
    (net (code "109") (name "/18_1439380519") (class "Default")
      (node (ref "JP111") (pin "1") (pinfunction "1_1") (pintype "passive"))
      (node (ref "JP979") (pin "P$2") (pinfunction "1_P$2") (pintype "passive"))
    )
    (net (code "110") (name "/18_1439380547") (class "Default")
      (node (ref "JP1159") (pin "P$2") (pinfunction "1_P$2") (pintype "passive"))
      (node (ref "JP55") (pin "1") (pinfunction "1_1") (pintype "passive"))
    )
    (net (code "111") (name "/18_1439380570") (class "Default")
      (node (ref "JP1039") (pin "P$2") (pinfunction "1_P$2") (pintype "passive"))
      (node (ref "JP120") (pin "1") (pinfunction "1_1") (pintype "passive"))
    )
    (net (code "112") (name "/18_1439380605") (class "Default")
      (node (ref "JP1179") (pin "P$2") (pinfunction "1_P$2") (pintype "passive"))
      (node (ref "JP57") (pin "1") (pinfunction "1_1") (pintype "passive"))
    )
    (net (code "113") (name "/18_1439380652") (class "Default")
      (node (ref "JP143") (pin "1") (pinfunction "1_1") (pintype "passive"))
      (node (ref "JP919") (pin "P$2") (pinfunction "1_P$2") (pintype "passive"))
    )
    (net (code "114") (name "/18_1439380747") (class "Default")
      (node (ref "JP1099") (pin "P$2") (pinfunction "1_P$2") (pintype "passive"))
      (node (ref "JP96") (pin "1") (pinfunction "1_1") (pintype "passive"))
    )
    (net (code "115") (name "/19_1439380519") (class "Default")
      (node (ref "JP92") (pin "1") (pinfunction "1_1") (pintype "passive"))
      (node (ref "JP980") (pin "P$2") (pinfunction "1_P$2") (pintype "passive"))
    )
    (net (code "116") (name "/19_1439380547") (class "Default")
      (node (ref "JP1160") (pin "P$2") (pinfunction "1_P$2") (pintype "passive"))
      (node (ref "JP53") (pin "1") (pinfunction "1_1") (pintype "passive"))
    )
    (net (code "117") (name "/19_1439380570") (class "Default")
      (node (ref "JP1040") (pin "P$2") (pinfunction "1_P$2") (pintype "passive"))
      (node (ref "JP99") (pin "1") (pinfunction "1_1") (pintype "passive"))
    )
    (net (code "118") (name "/19_1439380605") (class "Default")
      (node (ref "JP1180") (pin "P$2") (pinfunction "1_P$2") (pintype "passive"))
      (node (ref "JP56") (pin "1") (pinfunction "1_1") (pintype "passive"))
    )
    (net (code "119") (name "/19_1439380652") (class "Default")
      (node (ref "JP134") (pin "1") (pinfunction "1_1") (pintype "passive"))
      (node (ref "JP920") (pin "P$2") (pinfunction "1_P$2") (pintype "passive"))
    )
    (net (code "120") (name "/19_1439380747") (class "Default")
      (node (ref "JP1100") (pin "P$2") (pinfunction "1_P$2") (pintype "passive"))
      (node (ref "JP148") (pin "1") (pinfunction "1_1") (pintype "passive"))
    )
    (net (code "121") (name "/20_1439380519") (class "Default")
      (node (ref "JP121") (pin "1") (pinfunction "1_1") (pintype "passive"))
      (node (ref "JP981") (pin "P$2") (pinfunction "1_P$2") (pintype "passive"))
    )
    (net (code "122") (name "/20_1439380547") (class "Default")
      (node (ref "JP1181") (pin "P$2") (pinfunction "1_P$2") (pintype "passive"))
      (node (ref "JP294") (pin "1") (pinfunction "1_1") (pintype "passive"))
    )
    (net (code "123") (name "/20_1439380570") (class "Default")
      (node (ref "JP1041") (pin "P$2") (pinfunction "1_P$2") (pintype "passive"))
      (node (ref "JP130") (pin "1") (pinfunction "1_1") (pintype "passive"))
    )
    (net (code "124") (name "/20_1439380605") (class "Default")
      (node (ref "JP1191") (pin "P$2") (pinfunction "1_P$2") (pintype "passive"))
      (node (ref "JP296") (pin "1") (pinfunction "1_1") (pintype "passive"))
    )
    (net (code "125") (name "/20_1439380652") (class "Default")
      (node (ref "JP153") (pin "1") (pinfunction "1_1") (pintype "passive"))
      (node (ref "JP921") (pin "P$2") (pinfunction "1_P$2") (pintype "passive"))
    )
    (net (code "126") (name "/20_1439380747") (class "Default")
      (node (ref "JP1101") (pin "P$2") (pinfunction "1_P$2") (pintype "passive"))
      (node (ref "JP137") (pin "1") (pinfunction "1_1") (pintype "passive"))
    )
    (net (code "127") (name "/21_1439380519") (class "Default")
      (node (ref "JP102") (pin "1") (pinfunction "1_1") (pintype "passive"))
      (node (ref "JP982") (pin "P$2") (pinfunction "1_P$2") (pintype "passive"))
    )
    (net (code "128") (name "/21_1439380547") (class "Default")
      (node (ref "JP1182") (pin "P$2") (pinfunction "1_P$2") (pintype "passive"))
      (node (ref "JP284") (pin "1") (pinfunction "1_1") (pintype "passive"))
    )
    (net (code "129") (name "/21_1439380570") (class "Default")
      (node (ref "JP1042") (pin "P$2") (pinfunction "1_P$2") (pintype "passive"))
      (node (ref "JP109") (pin "1") (pinfunction "1_1") (pintype "passive"))
    )
    (net (code "130") (name "/21_1439380605") (class "Default")
      (node (ref "JP1192") (pin "P$2") (pinfunction "1_P$2") (pintype "passive"))
      (node (ref "JP297") (pin "1") (pinfunction "1_1") (pintype "passive"))
    )
    (net (code "131") (name "/21_1439380652") (class "Default")
      (node (ref "JP144") (pin "1") (pinfunction "1_1") (pintype "passive"))
      (node (ref "JP922") (pin "P$2") (pinfunction "1_P$2") (pintype "passive"))
    )
    (net (code "132") (name "/21_1439380747") (class "Default")
      (node (ref "JP1102") (pin "P$2") (pinfunction "1_P$2") (pintype "passive"))
      (node (ref "JP158") (pin "1") (pinfunction "1_1") (pintype "passive"))
    )
    (net (code "133") (name "/22_1439380519") (class "Default")
      (node (ref "JP131") (pin "1") (pinfunction "1_1") (pintype "passive"))
      (node (ref "JP983") (pin "P$2") (pinfunction "1_P$2") (pintype "passive"))
    )
    (net (code "134") (name "/22_1439380547") (class "Default")
      (node (ref "JP1183") (pin "P$2") (pinfunction "1_P$2") (pintype "passive"))
      (node (ref "JP295") (pin "1") (pinfunction "1_1") (pintype "passive"))
    )
    (net (code "135") (name "/22_1439380570") (class "Default")
      (node (ref "JP1043") (pin "P$2") (pinfunction "1_P$2") (pintype "passive"))
      (node (ref "JP140") (pin "1") (pinfunction "1_1") (pintype "passive"))
    )
    (net (code "136") (name "/22_1439380605") (class "Default")
      (node (ref "JP1193") (pin "P$2") (pinfunction "1_P$2") (pintype "passive"))
      (node (ref "JP287") (pin "1") (pinfunction "1_1") (pintype "passive"))
    )
    (net (code "137") (name "/22_1439380652") (class "Default")
      (node (ref "JP163") (pin "1") (pinfunction "1_1") (pintype "passive"))
      (node (ref "JP923") (pin "P$2") (pinfunction "1_P$2") (pintype "passive"))
    )
    (net (code "138") (name "/22_1439380747") (class "Default")
      (node (ref "JP1103") (pin "P$2") (pinfunction "1_P$2") (pintype "passive"))
      (node (ref "JP147") (pin "1") (pinfunction "1_1") (pintype "passive"))
    )
    (net (code "139") (name "/23_1439380519") (class "Default")
      (node (ref "JP112") (pin "1") (pinfunction "1_1") (pintype "passive"))
      (node (ref "JP984") (pin "P$2") (pinfunction "1_P$2") (pintype "passive"))
    )
    (net (code "140") (name "/23_1439380547") (class "Default")
      (node (ref "JP1184") (pin "P$2") (pinfunction "1_P$2") (pintype "passive"))
      (node (ref "JP285") (pin "1") (pinfunction "1_1") (pintype "passive"))
    )
    (net (code "141") (name "/23_1439380570") (class "Default")
      (node (ref "JP1044") (pin "P$2") (pinfunction "1_P$2") (pintype "passive"))
      (node (ref "JP119") (pin "1") (pinfunction "1_1") (pintype "passive"))
    )
    (net (code "142") (name "/23_1439380605") (class "Default")
      (node (ref "JP1194") (pin "P$2") (pinfunction "1_P$2") (pintype "passive"))
      (node (ref "JP286") (pin "1") (pinfunction "1_1") (pintype "passive"))
    )
    (net (code "143") (name "/23_1439380652") (class "Default")
      (node (ref "JP154") (pin "1") (pinfunction "1_1") (pintype "passive"))
      (node (ref "JP924") (pin "P$2") (pinfunction "1_P$2") (pintype "passive"))
    )
    (net (code "144") (name "/23_1439380747") (class "Default")
      (node (ref "JP1104") (pin "P$2") (pinfunction "1_P$2") (pintype "passive"))
      (node (ref "JP168") (pin "1") (pinfunction "1_1") (pintype "passive"))
    )
    (net (code "145") (name "/24_1439380519") (class "Default")
      (node (ref "JP141") (pin "1") (pinfunction "1_1") (pintype "passive"))
      (node (ref "JP985") (pin "P$2") (pinfunction "1_P$2") (pintype "passive"))
    )
    (net (code "146") (name "/24_1439380547") (class "Default")
      (node (ref "JP1185") (pin "P$2") (pinfunction "1_P$2") (pintype "passive"))
      (node (ref "JP273") (pin "1") (pinfunction "1_1") (pintype "passive"))
    )
    (net (code "147") (name "/24_1439380570") (class "Default")
      (node (ref "JP1045") (pin "P$2") (pinfunction "1_P$2") (pintype "passive"))
      (node (ref "JP150") (pin "1") (pinfunction "1_1") (pintype "passive"))
    )
    (net (code "148") (name "/24_1439380605") (class "Default")
      (node (ref "JP1195") (pin "P$2") (pinfunction "1_P$2") (pintype "passive"))
      (node (ref "JP278") (pin "1") (pinfunction "1_1") (pintype "passive"))
    )
    (net (code "149") (name "/24_1439380652") (class "Default")
      (node (ref "JP173") (pin "1") (pinfunction "1_1") (pintype "passive"))
      (node (ref "JP925") (pin "P$2") (pinfunction "1_P$2") (pintype "passive"))
    )
    (net (code "150") (name "/24_1439380747") (class "Default")
      (node (ref "JP1105") (pin "P$2") (pinfunction "1_P$2") (pintype "passive"))
      (node (ref "JP157") (pin "1") (pinfunction "1_1") (pintype "passive"))
    )
    (net (code "151") (name "/25_1439380519") (class "Default")
      (node (ref "JP122") (pin "1") (pinfunction "1_1") (pintype "passive"))
      (node (ref "JP986") (pin "P$2") (pinfunction "1_P$2") (pintype "passive"))
    )
    (net (code "152") (name "/25_1439380547") (class "Default")
      (node (ref "JP1186") (pin "P$2") (pinfunction "1_P$2") (pintype "passive"))
      (node (ref "JP274") (pin "1") (pinfunction "1_1") (pintype "passive"))
    )
    (net (code "153") (name "/25_1439380570") (class "Default")
      (node (ref "JP1046") (pin "P$2") (pinfunction "1_P$2") (pintype "passive"))
      (node (ref "JP129") (pin "1") (pinfunction "1_1") (pintype "passive"))
    )
    (net (code "154") (name "/25_1439380605") (class "Default")
      (node (ref "JP1196") (pin "P$2") (pinfunction "1_P$2") (pintype "passive"))
      (node (ref "JP277") (pin "1") (pinfunction "1_1") (pintype "passive"))
    )
    (net (code "155") (name "/25_1439380652") (class "Default")
      (node (ref "JP164") (pin "1") (pinfunction "1_1") (pintype "passive"))
      (node (ref "JP926") (pin "P$2") (pinfunction "1_P$2") (pintype "passive"))
    )
    (net (code "156") (name "/25_1439380747") (class "Default")
      (node (ref "JP1106") (pin "P$2") (pinfunction "1_P$2") (pintype "passive"))
      (node (ref "JP178") (pin "1") (pinfunction "1_1") (pintype "passive"))
    )
    (net (code "157") (name "/26_1439380519") (class "Default")
      (node (ref "JP151") (pin "1") (pinfunction "1_1") (pintype "passive"))
      (node (ref "JP987") (pin "P$2") (pinfunction "1_P$2") (pintype "passive"))
    )
    (net (code "158") (name "/26_1439380547") (class "Default")
      (node (ref "JP1187") (pin "P$2") (pinfunction "1_P$2") (pintype "passive"))
      (node (ref "JP275") (pin "1") (pinfunction "1_1") (pintype "passive"))
    )
    (net (code "159") (name "/26_1439380570") (class "Default")
      (node (ref "JP1047") (pin "P$2") (pinfunction "1_P$2") (pintype "passive"))
      (node (ref "JP160") (pin "1") (pinfunction "1_1") (pintype "passive"))
    )
    (net (code "160") (name "/26_1439380605") (class "Default")
      (node (ref "JP1197") (pin "P$2") (pinfunction "1_P$2") (pintype "passive"))
      (node (ref "JP276") (pin "1") (pinfunction "1_1") (pintype "passive"))
    )
    (net (code "161") (name "/26_1439380652") (class "Default")
      (node (ref "JP183") (pin "1") (pinfunction "1_1") (pintype "passive"))
      (node (ref "JP927") (pin "P$2") (pinfunction "1_P$2") (pintype "passive"))
    )
    (net (code "162") (name "/26_1439380747") (class "Default")
      (node (ref "JP1107") (pin "P$2") (pinfunction "1_P$2") (pintype "passive"))
      (node (ref "JP167") (pin "1") (pinfunction "1_1") (pintype "passive"))
    )
    (net (code "163") (name "/27_1439380519") (class "Default")
      (node (ref "JP132") (pin "1") (pinfunction "1_1") (pintype "passive"))
      (node (ref "JP988") (pin "P$2") (pinfunction "1_P$2") (pintype "passive"))
    )
    (net (code "164") (name "/27_1439380547") (class "Default")
      (node (ref "JP1188") (pin "P$2") (pinfunction "1_P$2") (pintype "passive"))
      (node (ref "JP264") (pin "1") (pinfunction "1_1") (pintype "passive"))
    )
    (net (code "165") (name "/27_1439380570") (class "Default")
      (node (ref "JP1048") (pin "P$2") (pinfunction "1_P$2") (pintype "passive"))
      (node (ref "JP139") (pin "1") (pinfunction "1_1") (pintype "passive"))
    )
    (net (code "166") (name "/27_1439380605") (class "Default")
      (node (ref "JP1198") (pin "P$2") (pinfunction "1_P$2") (pintype "passive"))
      (node (ref "JP268") (pin "1") (pinfunction "1_1") (pintype "passive"))
    )
    (net (code "167") (name "/27_1439380652") (class "Default")
      (node (ref "JP174") (pin "1") (pinfunction "1_1") (pintype "passive"))
      (node (ref "JP928") (pin "P$2") (pinfunction "1_P$2") (pintype "passive"))
    )
    (net (code "168") (name "/27_1439380747") (class "Default")
      (node (ref "JP1108") (pin "P$2") (pinfunction "1_P$2") (pintype "passive"))
      (node (ref "JP188") (pin "1") (pinfunction "1_1") (pintype "passive"))
    )
    (net (code "169") (name "/28_1439380519") (class "Default")
      (node (ref "JP161") (pin "1") (pinfunction "1_1") (pintype "passive"))
      (node (ref "JP989") (pin "P$2") (pinfunction "1_P$2") (pintype "passive"))
    )
    (net (code "170") (name "/28_1439380547") (class "Default")
      (node (ref "JP1189") (pin "P$2") (pinfunction "1_P$2") (pintype "passive"))
      (node (ref "JP265") (pin "1") (pinfunction "1_1") (pintype "passive"))
    )
    (net (code "171") (name "/28_1439380570") (class "Default")
      (node (ref "JP1049") (pin "P$2") (pinfunction "1_P$2") (pintype "passive"))
      (node (ref "JP170") (pin "1") (pinfunction "1_1") (pintype "passive"))
    )
    (net (code "172") (name "/28_1439380605") (class "Default")
      (node (ref "JP1199") (pin "P$2") (pinfunction "1_P$2") (pintype "passive"))
      (node (ref "JP267") (pin "1") (pinfunction "1_1") (pintype "passive"))
    )
    (net (code "173") (name "/28_1439380652") (class "Default")
      (node (ref "JP193") (pin "1") (pinfunction "1_1") (pintype "passive"))
      (node (ref "JP929") (pin "P$2") (pinfunction "1_P$2") (pintype "passive"))
    )
    (net (code "174") (name "/28_1439380747") (class "Default")
      (node (ref "JP1109") (pin "P$2") (pinfunction "1_P$2") (pintype "passive"))
      (node (ref "JP177") (pin "1") (pinfunction "1_1") (pintype "passive"))
    )
    (net (code "175") (name "/29_1439380519") (class "Default")
      (node (ref "JP142") (pin "1") (pinfunction "1_1") (pintype "passive"))
      (node (ref "JP990") (pin "P$2") (pinfunction "1_P$2") (pintype "passive"))
    )
    (net (code "176") (name "/29_1439380547") (class "Default")
      (node (ref "JP1190") (pin "P$2") (pinfunction "1_P$2") (pintype "passive"))
      (node (ref "JP263") (pin "1") (pinfunction "1_1") (pintype "passive"))
    )
    (net (code "177") (name "/29_1439380570") (class "Default")
      (node (ref "JP1050") (pin "P$2") (pinfunction "1_P$2") (pintype "passive"))
      (node (ref "JP149") (pin "1") (pinfunction "1_1") (pintype "passive"))
    )
    (net (code "178") (name "/29_1439380605") (class "Default")
      (node (ref "JP1200") (pin "P$2") (pinfunction "1_P$2") (pintype "passive"))
      (node (ref "JP258") (pin "1") (pinfunction "1_1") (pintype "passive"))
    )
    (net (code "179") (name "/29_1439380652") (class "Default")
      (node (ref "JP184") (pin "1") (pinfunction "1_1") (pintype "passive"))
      (node (ref "JP930") (pin "P$2") (pinfunction "1_P$2") (pintype "passive"))
    )
    (net (code "180") (name "/29_1439380747") (class "Default")
      (node (ref "JP1110") (pin "P$2") (pinfunction "1_P$2") (pintype "passive"))
      (node (ref "JP198") (pin "1") (pinfunction "1_1") (pintype "passive"))
    )
    (net (code "181") (name "/30_1439380519") (class "Default")
      (node (ref "JP171") (pin "1") (pinfunction "1_1") (pintype "passive"))
      (node (ref "JP991") (pin "P$2") (pinfunction "1_P$2") (pintype "passive"))
    )
    (net (code "182") (name "/30_1439380570") (class "Default")
      (node (ref "JP1051") (pin "P$2") (pinfunction "1_P$2") (pintype "passive"))
      (node (ref "JP180") (pin "1") (pinfunction "1_1") (pintype "passive"))
    )
    (net (code "183") (name "/30_1439380652") (class "Default")
      (node (ref "JP203") (pin "1") (pinfunction "1_1") (pintype "passive"))
      (node (ref "JP931") (pin "P$2") (pinfunction "1_P$2") (pintype "passive"))
    )
    (net (code "184") (name "/30_1439380747") (class "Default")
      (node (ref "JP1111") (pin "P$2") (pinfunction "1_P$2") (pintype "passive"))
      (node (ref "JP187") (pin "1") (pinfunction "1_1") (pintype "passive"))
    )
    (net (code "185") (name "/31_1439380519") (class "Default")
      (node (ref "JP152") (pin "1") (pinfunction "1_1") (pintype "passive"))
      (node (ref "JP992") (pin "P$2") (pinfunction "1_P$2") (pintype "passive"))
    )
    (net (code "186") (name "/31_1439380570") (class "Default")
      (node (ref "JP1052") (pin "P$2") (pinfunction "1_P$2") (pintype "passive"))
      (node (ref "JP159") (pin "1") (pinfunction "1_1") (pintype "passive"))
    )
    (net (code "187") (name "/31_1439380652") (class "Default")
      (node (ref "JP194") (pin "1") (pinfunction "1_1") (pintype "passive"))
      (node (ref "JP932") (pin "P$2") (pinfunction "1_P$2") (pintype "passive"))
    )
    (net (code "188") (name "/31_1439380747") (class "Default")
      (node (ref "JP1112") (pin "P$2") (pinfunction "1_P$2") (pintype "passive"))
      (node (ref "JP208") (pin "1") (pinfunction "1_1") (pintype "passive"))
    )
    (net (code "189") (name "/32_1439380519") (class "Default")
      (node (ref "JP181") (pin "1") (pinfunction "1_1") (pintype "passive"))
      (node (ref "JP993") (pin "P$2") (pinfunction "1_P$2") (pintype "passive"))
    )
    (net (code "190") (name "/32_1439380570") (class "Default")
      (node (ref "JP1053") (pin "P$2") (pinfunction "1_P$2") (pintype "passive"))
      (node (ref "JP190") (pin "1") (pinfunction "1_1") (pintype "passive"))
    )
    (net (code "191") (name "/32_1439380652") (class "Default")
      (node (ref "JP213") (pin "1") (pinfunction "1_1") (pintype "passive"))
      (node (ref "JP933") (pin "P$2") (pinfunction "1_P$2") (pintype "passive"))
    )
    (net (code "192") (name "/32_1439380747") (class "Default")
      (node (ref "JP1113") (pin "P$2") (pinfunction "1_P$2") (pintype "passive"))
      (node (ref "JP197") (pin "1") (pinfunction "1_1") (pintype "passive"))
    )
    (net (code "193") (name "/33_1439380519") (class "Default")
      (node (ref "JP162") (pin "1") (pinfunction "1_1") (pintype "passive"))
      (node (ref "JP994") (pin "P$2") (pinfunction "1_P$2") (pintype "passive"))
    )
    (net (code "194") (name "/33_1439380570") (class "Default")
      (node (ref "JP1054") (pin "P$2") (pinfunction "1_P$2") (pintype "passive"))
      (node (ref "JP169") (pin "1") (pinfunction "1_1") (pintype "passive"))
    )
    (net (code "195") (name "/33_1439380652") (class "Default")
      (node (ref "JP204") (pin "1") (pinfunction "1_1") (pintype "passive"))
      (node (ref "JP934") (pin "P$2") (pinfunction "1_P$2") (pintype "passive"))
    )
    (net (code "196") (name "/33_1439380747") (class "Default")
      (node (ref "JP1114") (pin "P$2") (pinfunction "1_P$2") (pintype "passive"))
      (node (ref "JP218") (pin "1") (pinfunction "1_1") (pintype "passive"))
    )
    (net (code "197") (name "/34_1439380519") (class "Default")
      (node (ref "JP191") (pin "1") (pinfunction "1_1") (pintype "passive"))
      (node (ref "JP995") (pin "P$2") (pinfunction "1_P$2") (pintype "passive"))
    )
    (net (code "198") (name "/34_1439380570") (class "Default")
      (node (ref "JP1055") (pin "P$2") (pinfunction "1_P$2") (pintype "passive"))
      (node (ref "JP200") (pin "1") (pinfunction "1_1") (pintype "passive"))
    )
    (net (code "199") (name "/34_1439380652") (class "Default")
      (node (ref "JP223") (pin "1") (pinfunction "1_1") (pintype "passive"))
      (node (ref "JP935") (pin "P$2") (pinfunction "1_P$2") (pintype "passive"))
    )
    (net (code "200") (name "/34_1439380747") (class "Default")
      (node (ref "JP1115") (pin "P$2") (pinfunction "1_P$2") (pintype "passive"))
      (node (ref "JP207") (pin "1") (pinfunction "1_1") (pintype "passive"))
    )
    (net (code "201") (name "/35_1439380519") (class "Default")
      (node (ref "JP172") (pin "1") (pinfunction "1_1") (pintype "passive"))
      (node (ref "JP996") (pin "P$2") (pinfunction "1_P$2") (pintype "passive"))
    )
    (net (code "202") (name "/35_1439380570") (class "Default")
      (node (ref "JP1056") (pin "P$2") (pinfunction "1_P$2") (pintype "passive"))
      (node (ref "JP179") (pin "1") (pinfunction "1_1") (pintype "passive"))
    )
    (net (code "203") (name "/35_1439380652") (class "Default")
      (node (ref "JP214") (pin "1") (pinfunction "1_1") (pintype "passive"))
      (node (ref "JP936") (pin "P$2") (pinfunction "1_P$2") (pintype "passive"))
    )
    (net (code "204") (name "/35_1439380747") (class "Default")
      (node (ref "JP1116") (pin "P$2") (pinfunction "1_P$2") (pintype "passive"))
      (node (ref "JP228") (pin "1") (pinfunction "1_1") (pintype "passive"))
    )
    (net (code "205") (name "/36_1439380519") (class "Default")
      (node (ref "JP201") (pin "1") (pinfunction "1_1") (pintype "passive"))
      (node (ref "JP997") (pin "P$2") (pinfunction "1_P$2") (pintype "passive"))
    )
    (net (code "206") (name "/36_1439380570") (class "Default")
      (node (ref "JP1057") (pin "P$2") (pinfunction "1_P$2") (pintype "passive"))
      (node (ref "JP210") (pin "1") (pinfunction "1_1") (pintype "passive"))
    )
    (net (code "207") (name "/36_1439380652") (class "Default")
      (node (ref "JP233") (pin "1") (pinfunction "1_1") (pintype "passive"))
      (node (ref "JP937") (pin "P$2") (pinfunction "1_P$2") (pintype "passive"))
    )
    (net (code "208") (name "/36_1439380747") (class "Default")
      (node (ref "JP1117") (pin "P$2") (pinfunction "1_P$2") (pintype "passive"))
      (node (ref "JP217") (pin "1") (pinfunction "1_1") (pintype "passive"))
    )
    (net (code "209") (name "/37_1439380519") (class "Default")
      (node (ref "JP182") (pin "1") (pinfunction "1_1") (pintype "passive"))
      (node (ref "JP998") (pin "P$2") (pinfunction "1_P$2") (pintype "passive"))
    )
    (net (code "210") (name "/37_1439380570") (class "Default")
      (node (ref "JP1058") (pin "P$2") (pinfunction "1_P$2") (pintype "passive"))
      (node (ref "JP189") (pin "1") (pinfunction "1_1") (pintype "passive"))
    )
    (net (code "211") (name "/37_1439380652") (class "Default")
      (node (ref "JP224") (pin "1") (pinfunction "1_1") (pintype "passive"))
      (node (ref "JP938") (pin "P$2") (pinfunction "1_P$2") (pintype "passive"))
    )
    (net (code "212") (name "/37_1439380747") (class "Default")
      (node (ref "JP1118") (pin "P$2") (pinfunction "1_P$2") (pintype "passive"))
      (node (ref "JP238") (pin "1") (pinfunction "1_1") (pintype "passive"))
    )
    (net (code "213") (name "/38_1439380519") (class "Default")
      (node (ref "JP211") (pin "1") (pinfunction "1_1") (pintype "passive"))
      (node (ref "JP999") (pin "P$2") (pinfunction "1_P$2") (pintype "passive"))
    )
    (net (code "214") (name "/38_1439380570") (class "Default")
      (node (ref "JP1059") (pin "P$2") (pinfunction "1_P$2") (pintype "passive"))
      (node (ref "JP220") (pin "1") (pinfunction "1_1") (pintype "passive"))
    )
    (net (code "215") (name "/38_1439380652") (class "Default")
      (node (ref "JP243") (pin "1") (pinfunction "1_1") (pintype "passive"))
      (node (ref "JP939") (pin "P$2") (pinfunction "1_P$2") (pintype "passive"))
    )
    (net (code "216") (name "/38_1439380747") (class "Default")
      (node (ref "JP1119") (pin "P$2") (pinfunction "1_P$2") (pintype "passive"))
      (node (ref "JP227") (pin "1") (pinfunction "1_1") (pintype "passive"))
    )
    (net (code "217") (name "/39_1439380519") (class "Default")
      (node (ref "JP1000") (pin "P$2") (pinfunction "1_P$2") (pintype "passive"))
      (node (ref "JP192") (pin "1") (pinfunction "1_1") (pintype "passive"))
    )
    (net (code "218") (name "/39_1439380570") (class "Default")
      (node (ref "JP1060") (pin "P$2") (pinfunction "1_P$2") (pintype "passive"))
      (node (ref "JP199") (pin "1") (pinfunction "1_1") (pintype "passive"))
    )
    (net (code "219") (name "/39_1439380652") (class "Default")
      (node (ref "JP234") (pin "1") (pinfunction "1_1") (pintype "passive"))
      (node (ref "JP940") (pin "P$2") (pinfunction "1_P$2") (pintype "passive"))
    )
    (net (code "220") (name "/39_1439380747") (class "Default")
      (node (ref "JP1120") (pin "P$2") (pinfunction "1_P$2") (pintype "passive"))
      (node (ref "JP248") (pin "1") (pinfunction "1_1") (pintype "passive"))
    )
    (net (code "221") (name "/40_1439380519") (class "Default")
      (node (ref "JP1001") (pin "P$2") (pinfunction "1_P$2") (pintype "passive"))
      (node (ref "JP221") (pin "1") (pinfunction "1_1") (pintype "passive"))
    )
    (net (code "222") (name "/40_1439380570") (class "Default")
      (node (ref "JP1061") (pin "P$2") (pinfunction "1_P$2") (pintype "passive"))
      (node (ref "JP230") (pin "1") (pinfunction "1_1") (pintype "passive"))
    )
    (net (code "223") (name "/40_1439380652") (class "Default")
      (node (ref "JP253") (pin "1") (pinfunction "1_1") (pintype "passive"))
      (node (ref "JP941") (pin "P$2") (pinfunction "1_P$2") (pintype "passive"))
    )
    (net (code "224") (name "/40_1439380747") (class "Default")
      (node (ref "JP1121") (pin "P$2") (pinfunction "1_P$2") (pintype "passive"))
      (node (ref "JP237") (pin "1") (pinfunction "1_1") (pintype "passive"))
    )
    (net (code "225") (name "/41_1439380519") (class "Default")
      (node (ref "JP1002") (pin "P$2") (pinfunction "1_P$2") (pintype "passive"))
      (node (ref "JP202") (pin "1") (pinfunction "1_1") (pintype "passive"))
    )
    (net (code "226") (name "/41_1439380570") (class "Default")
      (node (ref "JP1062") (pin "P$2") (pinfunction "1_P$2") (pintype "passive"))
      (node (ref "JP209") (pin "1") (pinfunction "1_1") (pintype "passive"))
    )
    (net (code "227") (name "/41_1439380652") (class "Default")
      (node (ref "JP244") (pin "1") (pinfunction "1_1") (pintype "passive"))
      (node (ref "JP942") (pin "P$2") (pinfunction "1_P$2") (pintype "passive"))
    )
    (net (code "228") (name "/41_1439380747") (class "Default")
      (node (ref "JP1122") (pin "P$2") (pinfunction "1_P$2") (pintype "passive"))
      (node (ref "JP247") (pin "1") (pinfunction "1_1") (pintype "passive"))
    )
    (net (code "229") (name "/42_1439380519") (class "Default")
      (node (ref "JP1003") (pin "P$2") (pinfunction "1_P$2") (pintype "passive"))
      (node (ref "JP231") (pin "1") (pinfunction "1_1") (pintype "passive"))
    )
    (net (code "230") (name "/42_1439380570") (class "Default")
      (node (ref "JP1063") (pin "P$2") (pinfunction "1_P$2") (pintype "passive"))
      (node (ref "JP240") (pin "1") (pinfunction "1_1") (pintype "passive"))
    )
    (net (code "231") (name "/42_1439380652") (class "Default")
      (node (ref "JP215") (pin "1") (pinfunction "1_1") (pintype "passive"))
      (node (ref "JP943") (pin "P$2") (pinfunction "1_P$2") (pintype "passive"))
    )
    (net (code "232") (name "/42_1439380747") (class "Default")
      (node (ref "JP1123") (pin "P$2") (pinfunction "1_P$2") (pintype "passive"))
      (node (ref "JP216") (pin "1") (pinfunction "1_1") (pintype "passive"))
    )
    (net (code "233") (name "/43_1439380519") (class "Default")
      (node (ref "JP1004") (pin "P$2") (pinfunction "1_P$2") (pintype "passive"))
      (node (ref "JP212") (pin "1") (pinfunction "1_1") (pintype "passive"))
    )
    (net (code "234") (name "/43_1439380570") (class "Default")
      (node (ref "JP1064") (pin "P$2") (pinfunction "1_P$2") (pintype "passive"))
      (node (ref "JP219") (pin "1") (pinfunction "1_1") (pintype "passive"))
    )
    (net (code "235") (name "/43_1439380652") (class "Default")
      (node (ref "JP254") (pin "1") (pinfunction "1_1") (pintype "passive"))
      (node (ref "JP944") (pin "P$2") (pinfunction "1_P$2") (pintype "passive"))
    )
    (net (code "236") (name "/43_1439380747") (class "Default")
      (node (ref "JP1124") (pin "P$2") (pinfunction "1_P$2") (pintype "passive"))
      (node (ref "JP257") (pin "1") (pinfunction "1_1") (pintype "passive"))
    )
    (net (code "237") (name "/44_1439380519") (class "Default")
      (node (ref "JP1005") (pin "P$2") (pinfunction "1_P$2") (pintype "passive"))
      (node (ref "JP241") (pin "1") (pinfunction "1_1") (pintype "passive"))
    )
    (net (code "238") (name "/44_1439380570") (class "Default")
      (node (ref "JP1065") (pin "P$2") (pinfunction "1_P$2") (pintype "passive"))
      (node (ref "JP250") (pin "1") (pinfunction "1_1") (pintype "passive"))
    )
    (net (code "239") (name "/44_1439380652") (class "Default")
      (node (ref "JP225") (pin "1") (pinfunction "1_1") (pintype "passive"))
      (node (ref "JP945") (pin "P$2") (pinfunction "1_P$2") (pintype "passive"))
    )
    (net (code "240") (name "/44_1439380747") (class "Default")
      (node (ref "JP1125") (pin "P$2") (pinfunction "1_P$2") (pintype "passive"))
      (node (ref "JP226") (pin "1") (pinfunction "1_1") (pintype "passive"))
    )
    (net (code "241") (name "/45_1439380519") (class "Default")
      (node (ref "JP1006") (pin "P$2") (pinfunction "1_P$2") (pintype "passive"))
      (node (ref "JP222") (pin "1") (pinfunction "1_1") (pintype "passive"))
    )
    (net (code "242") (name "/45_1439380570") (class "Default")
      (node (ref "JP1066") (pin "P$2") (pinfunction "1_P$2") (pintype "passive"))
      (node (ref "JP229") (pin "1") (pinfunction "1_1") (pintype "passive"))
    )
    (net (code "243") (name "/45_1439380652") (class "Default")
      (node (ref "JP235") (pin "1") (pinfunction "1_1") (pintype "passive"))
      (node (ref "JP946") (pin "P$2") (pinfunction "1_P$2") (pintype "passive"))
    )
    (net (code "244") (name "/45_1439380747") (class "Default")
      (node (ref "JP1126") (pin "P$2") (pinfunction "1_P$2") (pintype "passive"))
      (node (ref "JP236") (pin "1") (pinfunction "1_1") (pintype "passive"))
    )
    (net (code "245") (name "/46_1439380519") (class "Default")
      (node (ref "JP1007") (pin "P$2") (pinfunction "1_P$2") (pintype "passive"))
      (node (ref "JP251") (pin "1") (pinfunction "1_1") (pintype "passive"))
    )
    (net (code "246") (name "/46_1439380570") (class "Default")
      (node (ref "JP1067") (pin "P$2") (pinfunction "1_P$2") (pintype "passive"))
      (node (ref "JP260") (pin "1") (pinfunction "1_1") (pintype "passive"))
    )
    (net (code "247") (name "/46_1439380652") (class "Default")
      (node (ref "JP245") (pin "1") (pinfunction "1_1") (pintype "passive"))
      (node (ref "JP947") (pin "P$2") (pinfunction "1_P$2") (pintype "passive"))
    )
    (net (code "248") (name "/46_1439380747") (class "Default")
      (node (ref "JP1127") (pin "P$2") (pinfunction "1_P$2") (pintype "passive"))
      (node (ref "JP246") (pin "1") (pinfunction "1_1") (pintype "passive"))
    )
    (net (code "249") (name "/47_1439380519") (class "Default")
      (node (ref "JP1008") (pin "P$2") (pinfunction "1_P$2") (pintype "passive"))
      (node (ref "JP232") (pin "1") (pinfunction "1_1") (pintype "passive"))
    )
    (net (code "250") (name "/47_1439380570") (class "Default")
      (node (ref "JP1068") (pin "P$2") (pinfunction "1_P$2") (pintype "passive"))
      (node (ref "JP239") (pin "1") (pinfunction "1_1") (pintype "passive"))
    )
    (net (code "251") (name "/47_1439380652") (class "Default")
      (node (ref "JP255") (pin "1") (pinfunction "1_1") (pintype "passive"))
      (node (ref "JP948") (pin "P$2") (pinfunction "1_P$2") (pintype "passive"))
    )
    (net (code "252") (name "/47_1439380747") (class "Default")
      (node (ref "JP1128") (pin "P$2") (pinfunction "1_P$2") (pintype "passive"))
      (node (ref "JP256") (pin "1") (pinfunction "1_1") (pintype "passive"))
    )
    (net (code "253") (name "/48_1439380519") (class "Default")
      (node (ref "JP1009") (pin "P$2") (pinfunction "1_P$2") (pintype "passive"))
      (node (ref "JP261") (pin "1") (pinfunction "1_1") (pintype "passive"))
    )
    (net (code "254") (name "/48_1439380570") (class "Default")
      (node (ref "JP1069") (pin "P$2") (pinfunction "1_P$2") (pintype "passive"))
      (node (ref "JP270") (pin "1") (pinfunction "1_1") (pintype "passive"))
    )
    (net (code "255") (name "/48_1439380652") (class "Default")
      (node (ref "JP205") (pin "1") (pinfunction "1_1") (pintype "passive"))
      (node (ref "JP949") (pin "P$2") (pinfunction "1_P$2") (pintype "passive"))
    )
    (net (code "256") (name "/48_1439380747") (class "Default")
      (node (ref "JP1129") (pin "P$2") (pinfunction "1_P$2") (pintype "passive"))
      (node (ref "JP266") (pin "1") (pinfunction "1_1") (pintype "passive"))
    )
    (net (code "257") (name "/49_1439380519") (class "Default")
      (node (ref "JP1010") (pin "P$2") (pinfunction "1_P$2") (pintype "passive"))
      (node (ref "JP242") (pin "1") (pinfunction "1_1") (pintype "passive"))
    )
    (net (code "258") (name "/49_1439380570") (class "Default")
      (node (ref "JP1070") (pin "P$2") (pinfunction "1_P$2") (pintype "passive"))
      (node (ref "JP249") (pin "1") (pinfunction "1_1") (pintype "passive"))
    )
    (net (code "259") (name "/49_1439380652") (class "Default")
      (node (ref "JP195") (pin "1") (pinfunction "1_1") (pintype "passive"))
      (node (ref "JP950") (pin "P$2") (pinfunction "1_P$2") (pintype "passive"))
    )
    (net (code "260") (name "/49_1439380747") (class "Default")
      (node (ref "JP1130") (pin "P$2") (pinfunction "1_P$2") (pintype "passive"))
      (node (ref "JP206") (pin "1") (pinfunction "1_1") (pintype "passive"))
    )
    (net (code "261") (name "/50_1439380519") (class "Default")
      (node (ref "JP1011") (pin "P$2") (pinfunction "1_P$2") (pintype "passive"))
      (node (ref "JP271") (pin "1") (pinfunction "1_1") (pintype "passive"))
    )
    (net (code "262") (name "/50_1439380570") (class "Default")
      (node (ref "JP1071") (pin "P$2") (pinfunction "1_P$2") (pintype "passive"))
      (node (ref "JP280") (pin "1") (pinfunction "1_1") (pintype "passive"))
    )
    (net (code "263") (name "/50_1439380652") (class "Default")
      (node (ref "JP185") (pin "1") (pinfunction "1_1") (pintype "passive"))
      (node (ref "JP951") (pin "P$2") (pinfunction "1_P$2") (pintype "passive"))
    )
    (net (code "264") (name "/50_1439380747") (class "Default")
      (node (ref "JP1131") (pin "P$2") (pinfunction "1_P$2") (pintype "passive"))
      (node (ref "JP196") (pin "1") (pinfunction "1_1") (pintype "passive"))
    )
    (net (code "265") (name "/51_1439380519") (class "Default")
      (node (ref "JP1012") (pin "P$2") (pinfunction "1_P$2") (pintype "passive"))
      (node (ref "JP252") (pin "1") (pinfunction "1_1") (pintype "passive"))
    )
    (net (code "266") (name "/51_1439380570") (class "Default")
      (node (ref "JP1072") (pin "P$2") (pinfunction "1_P$2") (pintype "passive"))
      (node (ref "JP259") (pin "1") (pinfunction "1_1") (pintype "passive"))
    )
    (net (code "267") (name "/51_1439380652") (class "Default")
      (node (ref "JP175") (pin "1") (pinfunction "1_1") (pintype "passive"))
      (node (ref "JP952") (pin "P$2") (pinfunction "1_P$2") (pintype "passive"))
    )
    (net (code "268") (name "/51_1439380747") (class "Default")
      (node (ref "JP1132") (pin "P$2") (pinfunction "1_P$2") (pintype "passive"))
      (node (ref "JP186") (pin "1") (pinfunction "1_1") (pintype "passive"))
    )
    (net (code "269") (name "/52_1439380519") (class "Default")
      (node (ref "JP1013") (pin "P$2") (pinfunction "1_P$2") (pintype "passive"))
      (node (ref "JP281") (pin "1") (pinfunction "1_1") (pintype "passive"))
    )
    (net (code "270") (name "/52_1439380570") (class "Default")
      (node (ref "JP1073") (pin "P$2") (pinfunction "1_P$2") (pintype "passive"))
      (node (ref "JP290") (pin "1") (pinfunction "1_1") (pintype "passive"))
    )
    (net (code "271") (name "/52_1439380652") (class "Default")
      (node (ref "JP165") (pin "1") (pinfunction "1_1") (pintype "passive"))
      (node (ref "JP953") (pin "P$2") (pinfunction "1_P$2") (pintype "passive"))
    )
    (net (code "272") (name "/52_1439380747") (class "Default")
      (node (ref "JP1133") (pin "P$2") (pinfunction "1_P$2") (pintype "passive"))
      (node (ref "JP176") (pin "1") (pinfunction "1_1") (pintype "passive"))
    )
    (net (code "273") (name "/53_1439380519") (class "Default")
      (node (ref "JP1014") (pin "P$2") (pinfunction "1_P$2") (pintype "passive"))
      (node (ref "JP262") (pin "1") (pinfunction "1_1") (pintype "passive"))
    )
    (net (code "274") (name "/53_1439380570") (class "Default")
      (node (ref "JP1074") (pin "P$2") (pinfunction "1_P$2") (pintype "passive"))
      (node (ref "JP269") (pin "1") (pinfunction "1_1") (pintype "passive"))
    )
    (net (code "275") (name "/53_1439380652") (class "Default")
      (node (ref "JP155") (pin "1") (pinfunction "1_1") (pintype "passive"))
      (node (ref "JP954") (pin "P$2") (pinfunction "1_P$2") (pintype "passive"))
    )
    (net (code "276") (name "/53_1439380747") (class "Default")
      (node (ref "JP1134") (pin "P$2") (pinfunction "1_P$2") (pintype "passive"))
      (node (ref "JP166") (pin "1") (pinfunction "1_1") (pintype "passive"))
    )
    (net (code "277") (name "/54_1439380519") (class "Default")
      (node (ref "JP1015") (pin "P$2") (pinfunction "1_P$2") (pintype "passive"))
      (node (ref "JP291") (pin "1") (pinfunction "1_1") (pintype "passive"))
    )
    (net (code "278") (name "/54_1439380570") (class "Default")
      (node (ref "JP1075") (pin "P$2") (pinfunction "1_P$2") (pintype "passive"))
      (node (ref "JP300") (pin "1") (pinfunction "1_1") (pintype "passive"))
    )
    (net (code "279") (name "/54_1439380652") (class "Default")
      (node (ref "JP145") (pin "1") (pinfunction "1_1") (pintype "passive"))
      (node (ref "JP955") (pin "P$2") (pinfunction "1_P$2") (pintype "passive"))
    )
    (net (code "280") (name "/54_1439380747") (class "Default")
      (node (ref "JP1135") (pin "P$2") (pinfunction "1_P$2") (pintype "passive"))
      (node (ref "JP156") (pin "1") (pinfunction "1_1") (pintype "passive"))
    )
    (net (code "281") (name "/55_1439380519") (class "Default")
      (node (ref "JP1016") (pin "P$2") (pinfunction "1_P$2") (pintype "passive"))
      (node (ref "JP272") (pin "1") (pinfunction "1_1") (pintype "passive"))
    )
    (net (code "282") (name "/55_1439380570") (class "Default")
      (node (ref "JP1076") (pin "P$2") (pinfunction "1_P$2") (pintype "passive"))
      (node (ref "JP279") (pin "1") (pinfunction "1_1") (pintype "passive"))
    )
    (net (code "283") (name "/55_1439380652") (class "Default")
      (node (ref "JP135") (pin "1") (pinfunction "1_1") (pintype "passive"))
      (node (ref "JP956") (pin "P$2") (pinfunction "1_P$2") (pintype "passive"))
    )
    (net (code "284") (name "/55_1439380747") (class "Default")
      (node (ref "JP1136") (pin "P$2") (pinfunction "1_P$2") (pintype "passive"))
      (node (ref "JP146") (pin "1") (pinfunction "1_1") (pintype "passive"))
    )
    (net (code "285") (name "/56_1439380519") (class "Default")
      (node (ref "JP1017") (pin "P$2") (pinfunction "1_P$2") (pintype "passive"))
      (node (ref "JP282") (pin "1") (pinfunction "1_1") (pintype "passive"))
    )
    (net (code "286") (name "/56_1439380570") (class "Default")
      (node (ref "JP1077") (pin "P$2") (pinfunction "1_P$2") (pintype "passive"))
      (node (ref "JP289") (pin "1") (pinfunction "1_1") (pintype "passive"))
    )
    (net (code "287") (name "/56_1439380652") (class "Default")
      (node (ref "JP125") (pin "1") (pinfunction "1_1") (pintype "passive"))
      (node (ref "JP957") (pin "P$2") (pinfunction "1_P$2") (pintype "passive"))
    )
    (net (code "288") (name "/56_1439380747") (class "Default")
      (node (ref "JP1137") (pin "P$2") (pinfunction "1_P$2") (pintype "passive"))
      (node (ref "JP136") (pin "1") (pinfunction "1_1") (pintype "passive"))
    )
    (net (code "289") (name "/57_1439380519") (class "Default")
      (node (ref "JP1018") (pin "P$2") (pinfunction "1_P$2") (pintype "passive"))
      (node (ref "JP292") (pin "1") (pinfunction "1_1") (pintype "passive"))
    )
    (net (code "290") (name "/57_1439380570") (class "Default")
      (node (ref "JP1078") (pin "P$2") (pinfunction "1_P$2") (pintype "passive"))
      (node (ref "JP299") (pin "1") (pinfunction "1_1") (pintype "passive"))
    )
    (net (code "291") (name "/57_1439380652") (class "Default")
      (node (ref "JP115") (pin "1") (pinfunction "1_1") (pintype "passive"))
      (node (ref "JP958") (pin "P$2") (pinfunction "1_P$2") (pintype "passive"))
    )
    (net (code "292") (name "/57_1439380747") (class "Default")
      (node (ref "JP1138") (pin "P$2") (pinfunction "1_P$2") (pintype "passive"))
      (node (ref "JP126") (pin "1") (pinfunction "1_1") (pintype "passive"))
    )
    (net (code "293") (name "/58_1439380519") (class "Default")
      (node (ref "JP1019") (pin "P$2") (pinfunction "1_P$2") (pintype "passive"))
      (node (ref "JP293") (pin "1") (pinfunction "1_1") (pintype "passive"))
    )
    (net (code "294") (name "/58_1439380570") (class "Default")
      (node (ref "JP1079") (pin "P$2") (pinfunction "1_P$2") (pintype "passive"))
      (node (ref "JP298") (pin "1") (pinfunction "1_1") (pintype "passive"))
    )
    (net (code "295") (name "/58_1439380652") (class "Default")
      (node (ref "JP105") (pin "1") (pinfunction "1_1") (pintype "passive"))
      (node (ref "JP959") (pin "P$2") (pinfunction "1_P$2") (pintype "passive"))
    )
    (net (code "296") (name "/58_1439380747") (class "Default")
      (node (ref "JP1139") (pin "P$2") (pinfunction "1_P$2") (pintype "passive"))
      (node (ref "JP116") (pin "1") (pinfunction "1_1") (pintype "passive"))
    )
    (net (code "297") (name "/59_1439380519") (class "Default")
      (node (ref "JP1020") (pin "P$2") (pinfunction "1_P$2") (pintype "passive"))
      (node (ref "JP283") (pin "1") (pinfunction "1_1") (pintype "passive"))
    )
    (net (code "298") (name "/59_1439380570") (class "Default")
      (node (ref "JP1080") (pin "P$2") (pinfunction "1_P$2") (pintype "passive"))
      (node (ref "JP288") (pin "1") (pinfunction "1_1") (pintype "passive"))
    )
    (net (code "299") (name "/59_1439380652") (class "Default")
      (node (ref "JP95") (pin "1") (pinfunction "1_1") (pintype "passive"))
      (node (ref "JP960") (pin "P$2") (pinfunction "1_P$2") (pintype "passive"))
    )
    (net (code "300") (name "/59_1439380747") (class "Default")
      (node (ref "JP106") (pin "1") (pinfunction "1_1") (pintype "passive"))
      (node (ref "JP1140") (pin "P$2") (pinfunction "1_P$2") (pintype "passive"))
    )
  )
)
